# Protoboard_MX3-11-8-ESP12.net
KiCad netlist of a schematic drawn in EAGLE
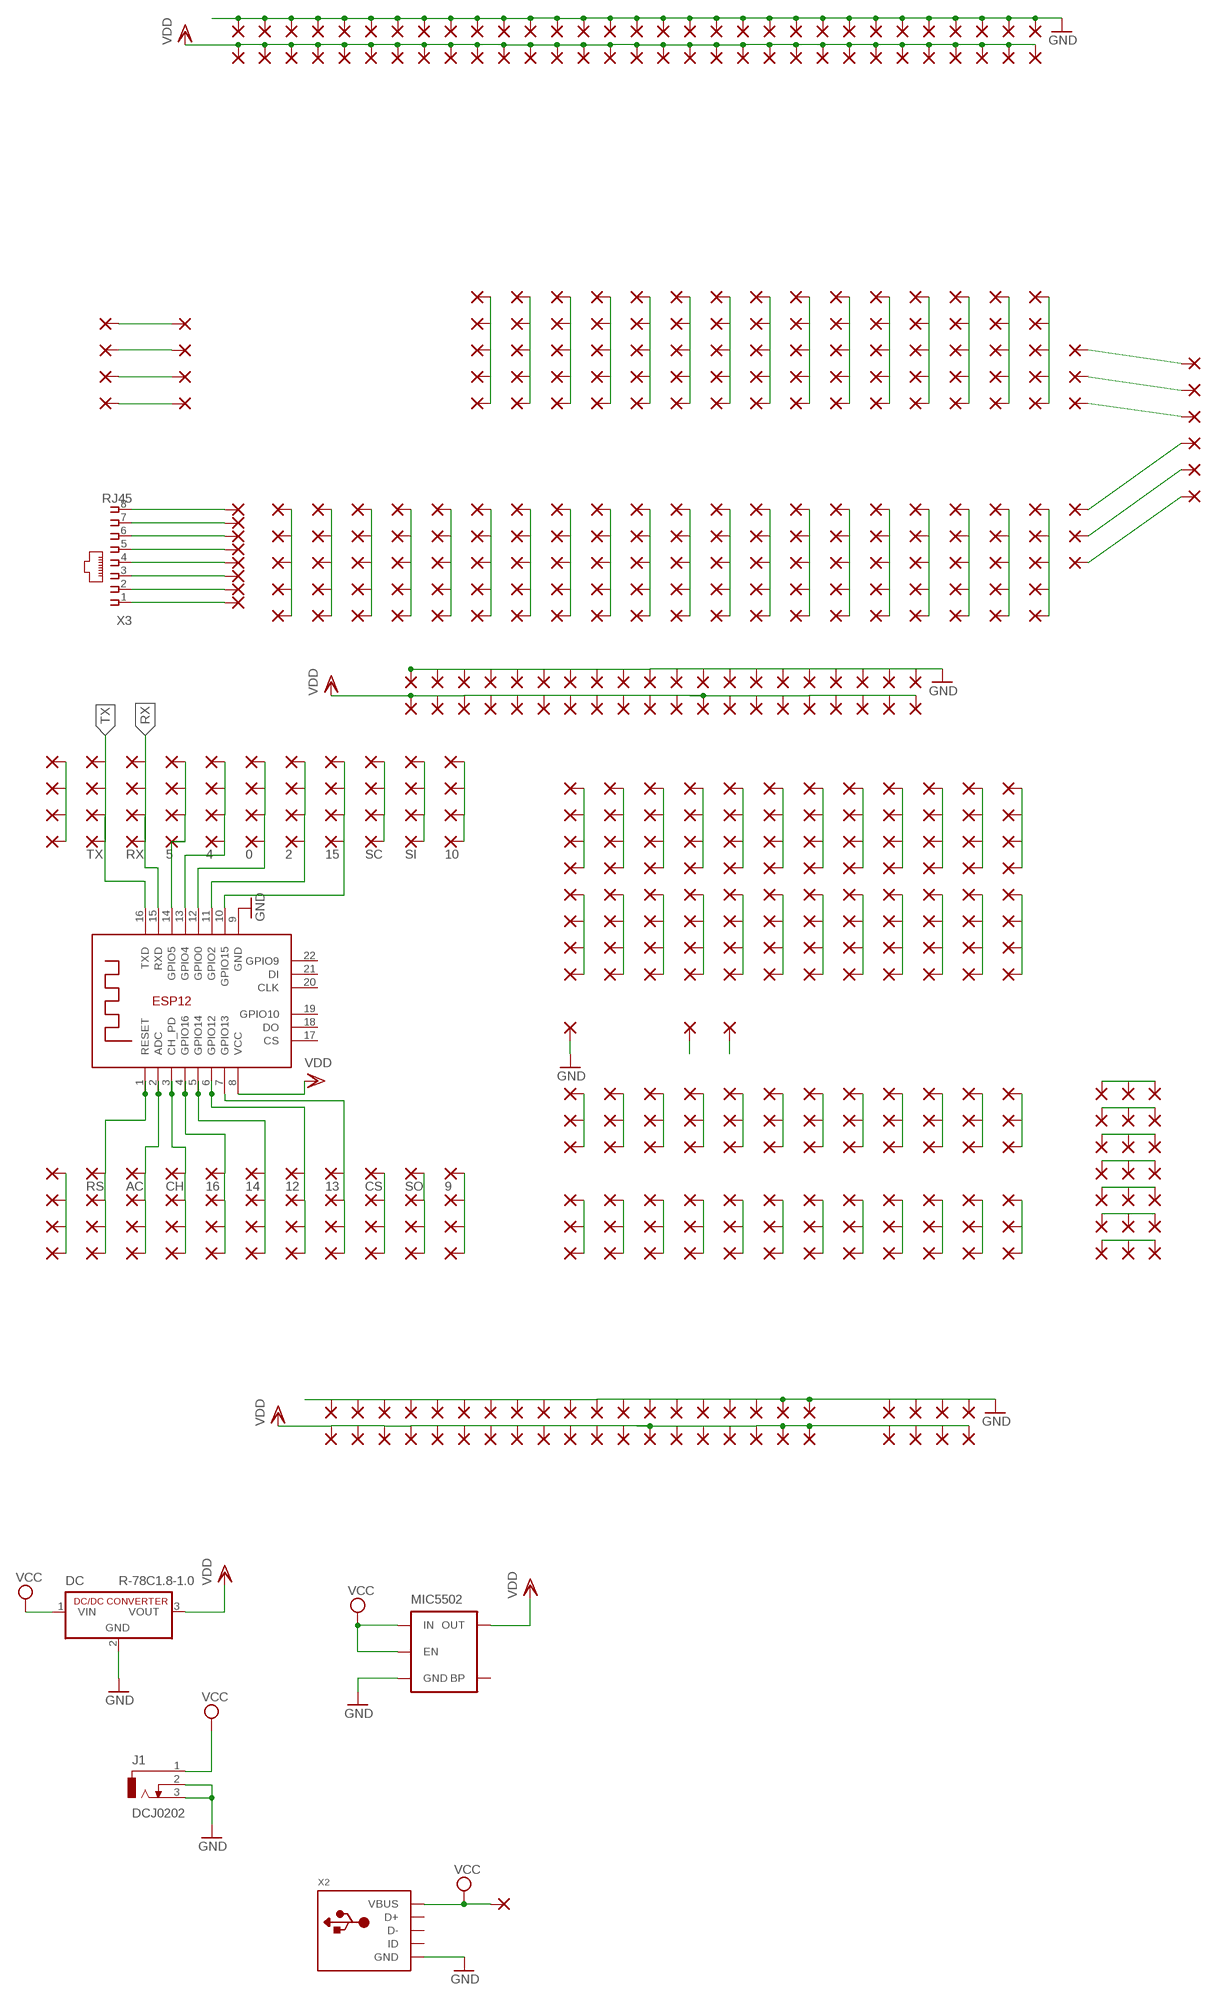
[diagram p0: schematic, sheet 1]

(export (version "E")
  (design (tool "Eeschema 10.0.6"))
  (components
    (comp (ref "1")
      (value "1,6/0,8")
      (footprint "eagle-import:1,6_0,8")
      (libsource (lib "eagle-import") (part "1,6/0,8"))
    )
    (comp (ref "2")
      (value "1,6/0,8")
      (footprint "eagle-import:1,6_0,8")
      (libsource (lib "eagle-import") (part "1,6/0,8"))
    )
    (comp (ref "4")
      (value "1,6/0,8")
      (footprint "eagle-import:1,6_0,8")
      (libsource (lib "eagle-import") (part "1,6/0,8"))
    )
    (comp (ref "5")
      (value "1,6/0,8")
      (footprint "eagle-import:1,6_0,8")
      (libsource (lib "eagle-import") (part "1,6/0,8"))
    )
    (comp (ref "5V")
      (value "1,6/0,8")
      (footprint "eagle-import:1,6_0,8")
      (libsource (lib "eagle-import") (part "1,6/0,8"))
    )
    (comp (ref "6")
      (value "1,6/0,8")
      (footprint "eagle-import:1,6_0,8")
      (libsource (lib "eagle-import") (part "1,6/0,8"))
    )
    (comp (ref "7")
      (value "1,6/0,8")
      (footprint "eagle-import:1,6_0,8")
      (libsource (lib "eagle-import") (part "1,6/0,8"))
    )
    (comp (ref "8")
      (value "1,6/0,8")
      (footprint "eagle-import:1,6_0,8")
      (libsource (lib "eagle-import") (part "1,6/0,8"))
    )
    (comp (ref "DC")
      (value "R-78C1.8-1.0")
      (footprint "eagle-import:SIP3")
      (libsource (lib "eagle-import") (part "R-78C-1.01.8"))
    )
    (comp (ref "J1")
      (value "DCJ0202")
      (footprint "eagle-import:DCJ0202")
      (libsource (lib "eagle-import") (part "DCJ0202"))
    )
    (comp (ref "MIC5502")
      (value "MIC52053.3V")
      (footprint "eagle-import:SOT23-5")
      (libsource (lib "eagle-import") (part "MIC52053.3V"))
    )
    (comp (ref "PAD1")
      (value "1,6/0,8")
      (footprint "eagle-import:1,6_0,8")
      (libsource (lib "eagle-import") (part "1,6/0,8"))
    )
    (comp (ref "PAD2")
      (value "1,6/0,8")
      (footprint "eagle-import:1,6_0,8")
      (libsource (lib "eagle-import") (part "1,6/0,8"))
    )
    (comp (ref "PAD3")
      (value "1,6/0,8")
      (footprint "eagle-import:1,6_0,8")
      (libsource (lib "eagle-import") (part "1,6/0,8"))
    )
    (comp (ref "PAD4")
      (value "1,6/0,8")
      (footprint "eagle-import:1,6_0,8")
      (libsource (lib "eagle-import") (part "1,6/0,8"))
    )
    (comp (ref "PAD5")
      (value "1,6/0,8")
      (footprint "eagle-import:1,6_0,8")
      (libsource (lib "eagle-import") (part "1,6/0,8"))
    )
    (comp (ref "PAD6")
      (value "1,6/0,8")
      (footprint "eagle-import:1,6_0,8")
      (libsource (lib "eagle-import") (part "1,6/0,8"))
    )
    (comp (ref "PAD7")
      (value "1,6/0,8")
      (footprint "eagle-import:1,6_0,8")
      (libsource (lib "eagle-import") (part "1,6/0,8"))
    )
    (comp (ref "PAD8")
      (value "1,6/0,8")
      (footprint "eagle-import:1,6_0,8")
      (libsource (lib "eagle-import") (part "1,6/0,8"))
    )
    (comp (ref "PAD9")
      (value "1,6/0,8")
      (footprint "eagle-import:1,6_0,8")
      (libsource (lib "eagle-import") (part "1,6/0,8"))
    )
    (comp (ref "PAD10")
      (value "1,6/0,8")
      (footprint "eagle-import:1,6_0,8")
      (libsource (lib "eagle-import") (part "1,6/0,8"))
    )
    (comp (ref "PAD11")
      (value "1,6/0,8")
      (footprint "eagle-import:1,6_0,8")
      (libsource (lib "eagle-import") (part "1,6/0,8"))
    )
    (comp (ref "PAD12")
      (value "1,6/0,8")
      (footprint "eagle-import:1,6_0,8")
      (libsource (lib "eagle-import") (part "1,6/0,8"))
    )
    (comp (ref "PAD13")
      (value "1,6/0,8")
      (footprint "eagle-import:1,6_0,8")
      (libsource (lib "eagle-import") (part "1,6/0,8"))
    )
    (comp (ref "PAD14")
      (value "1,6/0,8")
      (footprint "eagle-import:1,6_0,8")
      (libsource (lib "eagle-import") (part "1,6/0,8"))
    )
    (comp (ref "PAD15")
      (value "1,6/0,8")
      (footprint "eagle-import:1,6_0,8")
      (libsource (lib "eagle-import") (part "1,6/0,8"))
    )
    (comp (ref "PAD16")
      (value "1,6/0,8")
      (footprint "eagle-import:1,6_0,8")
      (libsource (lib "eagle-import") (part "1,6/0,8"))
    )
    (comp (ref "PAD17")
      (value "1,6/0,8")
      (footprint "eagle-import:1,6_0,8")
      (libsource (lib "eagle-import") (part "1,6/0,8"))
    )
    (comp (ref "PAD18")
      (value "1,6/0,8")
      (footprint "eagle-import:1,6_0,8")
      (libsource (lib "eagle-import") (part "1,6/0,8"))
    )
    (comp (ref "PAD19")
      (value "1,6/0,8")
      (footprint "eagle-import:1,6_0,8")
      (libsource (lib "eagle-import") (part "1,6/0,8"))
    )
    (comp (ref "PAD20")
      (value "1,6/0,8")
      (footprint "eagle-import:1,6_0,8")
      (libsource (lib "eagle-import") (part "1,6/0,8"))
    )
    (comp (ref "PAD21")
      (value "1,6/0,8")
      (footprint "eagle-import:1,6_0,8")
      (libsource (lib "eagle-import") (part "1,6/0,8"))
    )
    (comp (ref "PAD22")
      (value "1,6/0,8")
      (footprint "eagle-import:1,6_0,8")
      (libsource (lib "eagle-import") (part "1,6/0,8"))
    )
    (comp (ref "PAD23")
      (value "1,6/0,8")
      (footprint "eagle-import:1,6_0,8")
      (libsource (lib "eagle-import") (part "1,6/0,8"))
    )
    (comp (ref "PAD24")
      (value "1,6/0,8")
      (footprint "eagle-import:1,6_0,8")
      (libsource (lib "eagle-import") (part "1,6/0,8"))
    )
    (comp (ref "PAD25")
      (value "1,6/0,8")
      (footprint "eagle-import:1,6_0,8")
      (libsource (lib "eagle-import") (part "1,6/0,8"))
    )
    (comp (ref "PAD26")
      (value "1,6/0,8")
      (footprint "eagle-import:1,6_0,8")
      (libsource (lib "eagle-import") (part "1,6/0,8"))
    )
    (comp (ref "PAD27")
      (value "1,6/0,8")
      (footprint "eagle-import:1,6_0,8")
      (libsource (lib "eagle-import") (part "1,6/0,8"))
    )
    (comp (ref "PAD28")
      (value "1,6/0,8")
      (footprint "eagle-import:1,6_0,8")
      (libsource (lib "eagle-import") (part "1,6/0,8"))
    )
    (comp (ref "PAD29")
      (value "1,6/0,8")
      (footprint "eagle-import:1,6_0,8")
      (libsource (lib "eagle-import") (part "1,6/0,8"))
    )
    (comp (ref "PAD30")
      (value "1,6/0,8")
      (footprint "eagle-import:1,6_0,8")
      (libsource (lib "eagle-import") (part "1,6/0,8"))
    )
    (comp (ref "PAD31")
      (value "1,6/0,8")
      (footprint "eagle-import:1,6_0,8")
      (libsource (lib "eagle-import") (part "1,6/0,8"))
    )
    (comp (ref "PAD32")
      (value "1,6/0,8")
      (footprint "eagle-import:1,6_0,8")
      (libsource (lib "eagle-import") (part "1,6/0,8"))
    )
    (comp (ref "PAD33")
      (value "1,6/0,8")
      (footprint "eagle-import:1,6_0,8")
      (libsource (lib "eagle-import") (part "1,6/0,8"))
    )
    (comp (ref "PAD34")
      (value "1,6/0,8")
      (footprint "eagle-import:1,6_0,8")
      (libsource (lib "eagle-import") (part "1,6/0,8"))
    )
    (comp (ref "PAD35")
      (value "1,6/0,8")
      (footprint "eagle-import:1,6_0,8")
      (libsource (lib "eagle-import") (part "1,6/0,8"))
    )
    (comp (ref "PAD36")
      (value "1,6/0,8")
      (footprint "eagle-import:1,6_0,8")
      (libsource (lib "eagle-import") (part "1,6/0,8"))
    )
    (comp (ref "PAD37")
      (value "1,6/0,8")
      (footprint "eagle-import:1,6_0,8")
      (libsource (lib "eagle-import") (part "1,6/0,8"))
    )
    (comp (ref "PAD38")
      (value "1,6/0,8")
      (footprint "eagle-import:1,6_0,8")
      (libsource (lib "eagle-import") (part "1,6/0,8"))
    )
    (comp (ref "PAD39")
      (value "1,6/0,8")
      (footprint "eagle-import:1,6_0,8")
      (libsource (lib "eagle-import") (part "1,6/0,8"))
    )
    (comp (ref "PAD40")
      (value "1,6/0,8")
      (footprint "eagle-import:1,6_0,8")
      (libsource (lib "eagle-import") (part "1,6/0,8"))
    )
    (comp (ref "PAD41")
      (value "1,6/0,8")
      (footprint "eagle-import:1,6_0,8")
      (libsource (lib "eagle-import") (part "1,6/0,8"))
    )
    (comp (ref "PAD42")
      (value "1,6/0,8")
      (footprint "eagle-import:1,6_0,8")
      (libsource (lib "eagle-import") (part "1,6/0,8"))
    )
    (comp (ref "PAD45")
      (value "1,6/0,8")
      (footprint "eagle-import:1,6_0,8")
      (libsource (lib "eagle-import") (part "1,6/0,8"))
    )
    (comp (ref "PAD46")
      (value "1,6/0,8")
      (footprint "eagle-import:1,6_0,8")
      (libsource (lib "eagle-import") (part "1,6/0,8"))
    )
    (comp (ref "PAD47")
      (value "1,6/0,8")
      (footprint "eagle-import:1,6_0,8")
      (libsource (lib "eagle-import") (part "1,6/0,8"))
    )
    (comp (ref "PAD48")
      (value "1,6/0,8")
      (footprint "eagle-import:1,6_0,8")
      (libsource (lib "eagle-import") (part "1,6/0,8"))
    )
    (comp (ref "PAD52")
      (value "1,6/0,8")
      (footprint "eagle-import:1,6_0,8")
      (libsource (lib "eagle-import") (part "1,6/0,8"))
    )
    (comp (ref "PAD53")
      (value "1,6/0,8")
      (footprint "eagle-import:1,6_0,8")
      (libsource (lib "eagle-import") (part "1,6/0,8"))
    )
    (comp (ref "PAD54")
      (value "1,6/0,8")
      (footprint "eagle-import:1,6_0,8")
      (libsource (lib "eagle-import") (part "1,6/0,8"))
    )
    (comp (ref "PAD55")
      (value "1,6/0,8")
      (footprint "eagle-import:1,6_0,8")
      (libsource (lib "eagle-import") (part "1,6/0,8"))
    )
    (comp (ref "PAD59")
      (value "1,6/0,8")
      (footprint "eagle-import:1,6_0,8")
      (libsource (lib "eagle-import") (part "1,6/0,8"))
    )
    (comp (ref "PAD60")
      (value "1,6/0,8")
      (footprint "eagle-import:1,6_0,8")
      (libsource (lib "eagle-import") (part "1,6/0,8"))
    )
    (comp (ref "PAD61")
      (value "1,6/0,8")
      (footprint "eagle-import:1,6_0,8")
      (libsource (lib "eagle-import") (part "1,6/0,8"))
    )
    (comp (ref "PAD62")
      (value "1,6/0,8")
      (footprint "eagle-import:1,6_0,8")
      (libsource (lib "eagle-import") (part "1,6/0,8"))
    )
    (comp (ref "PAD63")
      (value "1,6/0,8")
      (footprint "eagle-import:1,6_0,8")
      (libsource (lib "eagle-import") (part "1,6/0,8"))
    )
    (comp (ref "PAD64")
      (value "1,6/0,8")
      (footprint "eagle-import:1,6_0,8")
      (libsource (lib "eagle-import") (part "1,6/0,8"))
    )
    (comp (ref "PAD65")
      (value "1,6/0,8")
      (footprint "eagle-import:1,6_0,8")
      (libsource (lib "eagle-import") (part "1,6/0,8"))
    )
    (comp (ref "PAD66")
      (value "1,6/0,8")
      (footprint "eagle-import:1,6_0,8")
      (libsource (lib "eagle-import") (part "1,6/0,8"))
    )
    (comp (ref "PAD67")
      (value "1,6/0,8")
      (footprint "eagle-import:1,6_0,8")
      (libsource (lib "eagle-import") (part "1,6/0,8"))
    )
    (comp (ref "PAD68")
      (value "1,6/0,8")
      (footprint "eagle-import:1,6_0,8")
      (libsource (lib "eagle-import") (part "1,6/0,8"))
    )
    (comp (ref "PAD69")
      (value "1,6/0,8")
      (footprint "eagle-import:1,6_0,8")
      (libsource (lib "eagle-import") (part "1,6/0,8"))
    )
    (comp (ref "PAD70")
      (value "1,6/0,8")
      (footprint "eagle-import:1,6_0,8")
      (libsource (lib "eagle-import") (part "1,6/0,8"))
    )
    (comp (ref "PAD71")
      (value "1,6/0,8")
      (footprint "eagle-import:1,6_0,8")
      (libsource (lib "eagle-import") (part "1,6/0,8"))
    )
    (comp (ref "PAD72")
      (value "1,6/0,8")
      (footprint "eagle-import:1,6_0,8")
      (libsource (lib "eagle-import") (part "1,6/0,8"))
    )
    (comp (ref "PAD73")
      (value "1,6/0,8")
      (footprint "eagle-import:1,6_0,8")
      (libsource (lib "eagle-import") (part "1,6/0,8"))
    )
    (comp (ref "PAD74")
      (value "1,6/0,8")
      (footprint "eagle-import:1,6_0,8")
      (libsource (lib "eagle-import") (part "1,6/0,8"))
    )
    (comp (ref "PAD75")
      (value "1,6/0,8")
      (footprint "eagle-import:1,6_0,8")
      (libsource (lib "eagle-import") (part "1,6/0,8"))
    )
    (comp (ref "PAD76")
      (value "1,6/0,8")
      (footprint "eagle-import:1,6_0,8")
      (libsource (lib "eagle-import") (part "1,6/0,8"))
    )
    (comp (ref "PAD77")
      (value "1,6/0,8")
      (footprint "eagle-import:1,6_0,8")
      (libsource (lib "eagle-import") (part "1,6/0,8"))
    )
    (comp (ref "PAD78")
      (value "1,6/0,8")
      (footprint "eagle-import:1,6_0,8")
      (libsource (lib "eagle-import") (part "1,6/0,8"))
    )
    (comp (ref "PAD79")
      (value "1,6/0,8")
      (footprint "eagle-import:1,6_0,8")
      (libsource (lib "eagle-import") (part "1,6/0,8"))
    )
    (comp (ref "PAD80")
      (value "1,6/0,8")
      (footprint "eagle-import:1,6_0,8")
      (libsource (lib "eagle-import") (part "1,6/0,8"))
    )
    (comp (ref "PAD81")
      (value "1,6/0,8")
      (footprint "eagle-import:1,6_0,8")
      (libsource (lib "eagle-import") (part "1,6/0,8"))
    )
    (comp (ref "PAD82")
      (value "1,6/0,8")
      (footprint "eagle-import:1,6_0,8")
      (libsource (lib "eagle-import") (part "1,6/0,8"))
    )
    (comp (ref "PAD83")
      (value "1,6/0,8")
      (footprint "eagle-import:1,6_0,8")
      (libsource (lib "eagle-import") (part "1,6/0,8"))
    )
    (comp (ref "PAD84")
      (value "1,6/0,8")
      (footprint "eagle-import:1,6_0,8")
      (libsource (lib "eagle-import") (part "1,6/0,8"))
    )
    (comp (ref "PAD85")
      (value "1,6/0,8")
      (footprint "eagle-import:1,6_0,8")
      (libsource (lib "eagle-import") (part "1,6/0,8"))
    )
    (comp (ref "PAD86")
      (value "1,6/0,8")
      (footprint "eagle-import:1,6_0,8")
      (libsource (lib "eagle-import") (part "1,6/0,8"))
    )
    (comp (ref "PAD88")
      (value "1,6/0,8")
      (footprint "eagle-import:1,6_0,8")
      (libsource (lib "eagle-import") (part "1,6/0,8"))
    )
    (comp (ref "PAD89")
      (value "1,6/0,8")
      (footprint "eagle-import:1,6_0,8")
      (libsource (lib "eagle-import") (part "1,6/0,8"))
    )
    (comp (ref "PAD90")
      (value "1,6/0,8")
      (footprint "eagle-import:1,6_0,8")
      (libsource (lib "eagle-import") (part "1,6/0,8"))
    )
    (comp (ref "PAD91")
      (value "1,6/0,8")
      (footprint "eagle-import:1,6_0,8")
      (libsource (lib "eagle-import") (part "1,6/0,8"))
    )
    (comp (ref "PAD92")
      (value "1,6/0,8")
      (footprint "eagle-import:1,6_0,8")
      (libsource (lib "eagle-import") (part "1,6/0,8"))
    )
    (comp (ref "PAD93")
      (value "1,6/0,8")
      (footprint "eagle-import:1,6_0,8")
      (libsource (lib "eagle-import") (part "1,6/0,8"))
    )
    (comp (ref "PAD94")
      (value "1,6/0,8")
      (footprint "eagle-import:1,6_0,8")
      (libsource (lib "eagle-import") (part "1,6/0,8"))
    )
    (comp (ref "PAD97")
      (value "1,6/0,8")
      (footprint "eagle-import:1,6_0,8")
      (libsource (lib "eagle-import") (part "1,6/0,8"))
    )
    (comp (ref "PAD98")
      (value "1,6/0,8")
      (footprint "eagle-import:1,6_0,8")
      (libsource (lib "eagle-import") (part "1,6/0,8"))
    )
    (comp (ref "PAD99")
      (value "1,6/0,8")
      (footprint "eagle-import:1,6_0,8")
      (libsource (lib "eagle-import") (part "1,6/0,8"))
    )
    (comp (ref "PAD100")
      (value "1,6/0,8")
      (footprint "eagle-import:1,6_0,8")
      (libsource (lib "eagle-import") (part "1,6/0,8"))
    )
    (comp (ref "PAD101")
      (value "1,6/0,8")
      (footprint "eagle-import:1,6_0,8")
      (libsource (lib "eagle-import") (part "1,6/0,8"))
    )
    (comp (ref "PAD102")
      (value "1,6/0,8")
      (footprint "eagle-import:1,6_0,8")
      (libsource (lib "eagle-import") (part "1,6/0,8"))
    )
    (comp (ref "PAD103")
      (value "1,6/0,8")
      (footprint "eagle-import:1,6_0,8")
      (libsource (lib "eagle-import") (part "1,6/0,8"))
    )
    (comp (ref "PAD106")
      (value "1,6/0,8")
      (footprint "eagle-import:1,6_0,8")
      (libsource (lib "eagle-import") (part "1,6/0,8"))
    )
    (comp (ref "PAD107")
      (value "1,6/0,8")
      (footprint "eagle-import:1,6_0,8")
      (libsource (lib "eagle-import") (part "1,6/0,8"))
    )
    (comp (ref "PAD108")
      (value "1,6/0,8")
      (footprint "eagle-import:1,6_0,8")
      (libsource (lib "eagle-import") (part "1,6/0,8"))
    )
    (comp (ref "PAD109")
      (value "1,6/0,8")
      (footprint "eagle-import:1,6_0,8")
      (libsource (lib "eagle-import") (part "1,6/0,8"))
    )
    (comp (ref "PAD110")
      (value "1,6/0,8")
      (footprint "eagle-import:1,6_0,8")
      (libsource (lib "eagle-import") (part "1,6/0,8"))
    )
    (comp (ref "PAD111")
      (value "1,6/0,8")
      (footprint "eagle-import:1,6_0,8")
      (libsource (lib "eagle-import") (part "1,6/0,8"))
    )
    (comp (ref "PAD112")
      (value "1,6/0,8")
      (footprint "eagle-import:1,6_0,8")
      (libsource (lib "eagle-import") (part "1,6/0,8"))
    )
    (comp (ref "PAD115")
      (value "1,6/0,8")
      (footprint "eagle-import:1,6_0,8")
      (libsource (lib "eagle-import") (part "1,6/0,8"))
    )
    (comp (ref "PAD116")
      (value "1,6/0,8")
      (footprint "eagle-import:1,6_0,8")
      (libsource (lib "eagle-import") (part "1,6/0,8"))
    )
    (comp (ref "PAD117")
      (value "1,6/0,8")
      (footprint "eagle-import:1,6_0,8")
      (libsource (lib "eagle-import") (part "1,6/0,8"))
    )
    (comp (ref "PAD118")
      (value "1,6/0,8")
      (footprint "eagle-import:1,6_0,8")
      (libsource (lib "eagle-import") (part "1,6/0,8"))
    )
    (comp (ref "PAD119")
      (value "1,6/0,8")
      (footprint "eagle-import:1,6_0,8")
      (libsource (lib "eagle-import") (part "1,6/0,8"))
    )
    (comp (ref "PAD120")
      (value "1,6/0,8")
      (footprint "eagle-import:1,6_0,8")
      (libsource (lib "eagle-import") (part "1,6/0,8"))
    )
    (comp (ref "PAD121")
      (value "1,6/0,8")
      (footprint "eagle-import:1,6_0,8")
      (libsource (lib "eagle-import") (part "1,6/0,8"))
    )
    (comp (ref "PAD122")
      (value "1,6/0,8")
      (footprint "eagle-import:1,6_0,8")
      (libsource (lib "eagle-import") (part "1,6/0,8"))
    )
    (comp (ref "PAD123")
      (value "1,6/0,8")
      (footprint "eagle-import:1,6_0,8")
      (libsource (lib "eagle-import") (part "1,6/0,8"))
    )
    (comp (ref "PAD124")
      (value "1,6/0,8")
      (footprint "eagle-import:1,6_0,8")
      (libsource (lib "eagle-import") (part "1,6/0,8"))
    )
    (comp (ref "PAD125")
      (value "1,6/0,8")
      (footprint "eagle-import:1,6_0,8")
      (libsource (lib "eagle-import") (part "1,6/0,8"))
    )
    (comp (ref "PAD126")
      (value "1,6/0,8")
      (footprint "eagle-import:1,6_0,8")
      (libsource (lib "eagle-import") (part "1,6/0,8"))
    )
    (comp (ref "PAD128")
      (value "1,6/0,8")
      (footprint "eagle-import:1,6_0,8")
      (libsource (lib "eagle-import") (part "1,6/0,8"))
    )
    (comp (ref "PAD129")
      (value "1,6/0,8")
      (footprint "eagle-import:1,6_0,8")
      (libsource (lib "eagle-import") (part "1,6/0,8"))
    )
    (comp (ref "PAD130")
      (value "1,6/0,8")
      (footprint "eagle-import:1,6_0,8")
      (libsource (lib "eagle-import") (part "1,6/0,8"))
    )
    (comp (ref "PAD131")
      (value "1,6/0,8")
      (footprint "eagle-import:1,6_0,8")
      (libsource (lib "eagle-import") (part "1,6/0,8"))
    )
    (comp (ref "PAD132")
      (value "1,6/0,8")
      (footprint "eagle-import:1,6_0,8")
      (libsource (lib "eagle-import") (part "1,6/0,8"))
    )
    (comp (ref "PAD133")
      (value "1,6/0,8")
      (footprint "eagle-import:1,6_0,8")
      (libsource (lib "eagle-import") (part "1,6/0,8"))
    )
    (comp (ref "PAD134")
      (value "1,6/0,8")
      (footprint "eagle-import:1,6_0,8")
      (libsource (lib "eagle-import") (part "1,6/0,8"))
    )
    (comp (ref "PAD135")
      (value "1,6/0,8")
      (footprint "eagle-import:1,6_0,8")
      (libsource (lib "eagle-import") (part "1,6/0,8"))
    )
    (comp (ref "PAD137")
      (value "1,6/0,8")
      (footprint "eagle-import:1,6_0,8")
      (libsource (lib "eagle-import") (part "1,6/0,8"))
    )
    (comp (ref "PAD138")
      (value "1,6/0,8")
      (footprint "eagle-import:1,6_0,8")
      (libsource (lib "eagle-import") (part "1,6/0,8"))
    )
    (comp (ref "PAD139")
      (value "1,6/0,8")
      (footprint "eagle-import:1,6_0,8")
      (libsource (lib "eagle-import") (part "1,6/0,8"))
    )
    (comp (ref "PAD140")
      (value "1,6/0,8")
      (footprint "eagle-import:1,6_0,8")
      (libsource (lib "eagle-import") (part "1,6/0,8"))
    )
    (comp (ref "PAD141")
      (value "1,6/0,8")
      (footprint "eagle-import:1,6_0,8")
      (libsource (lib "eagle-import") (part "1,6/0,8"))
    )
    (comp (ref "PAD142")
      (value "1,6/0,8")
      (footprint "eagle-import:1,6_0,8")
      (libsource (lib "eagle-import") (part "1,6/0,8"))
    )
    (comp (ref "PAD143")
      (value "1,6/0,8")
      (footprint "eagle-import:1,6_0,8")
      (libsource (lib "eagle-import") (part "1,6/0,8"))
    )
    (comp (ref "PAD144")
      (value "1,6/0,8")
      (footprint "eagle-import:1,6_0,8")
      (libsource (lib "eagle-import") (part "1,6/0,8"))
    )
    (comp (ref "PAD146")
      (value "1,6/0,8")
      (footprint "eagle-import:1,6_0,8")
      (libsource (lib "eagle-import") (part "1,6/0,8"))
    )
    (comp (ref "PAD147")
      (value "1,6/0,8")
      (footprint "eagle-import:1,6_0,8")
      (libsource (lib "eagle-import") (part "1,6/0,8"))
    )
    (comp (ref "PAD148")
      (value "1,6/0,8")
      (footprint "eagle-import:1,6_0,8")
      (libsource (lib "eagle-import") (part "1,6/0,8"))
    )
    (comp (ref "PAD149")
      (value "1,6/0,8")
      (footprint "eagle-import:1,6_0,8")
      (libsource (lib "eagle-import") (part "1,6/0,8"))
    )
    (comp (ref "PAD150")
      (value "1,6/0,8")
      (footprint "eagle-import:1,6_0,8")
      (libsource (lib "eagle-import") (part "1,6/0,8"))
    )
    (comp (ref "PAD151")
      (value "1,6/0,8")
      (footprint "eagle-import:1,6_0,8")
      (libsource (lib "eagle-import") (part "1,6/0,8"))
    )
    (comp (ref "PAD152")
      (value "1,6/0,8")
      (footprint "eagle-import:1,6_0,8")
      (libsource (lib "eagle-import") (part "1,6/0,8"))
    )
    (comp (ref "PAD153")
      (value "1,6/0,8")
      (footprint "eagle-import:1,6_0,8")
      (libsource (lib "eagle-import") (part "1,6/0,8"))
    )
    (comp (ref "PAD155")
      (value "1,6/0,8")
      (footprint "eagle-import:1,6_0,8")
      (libsource (lib "eagle-import") (part "1,6/0,8"))
    )
    (comp (ref "PAD156")
      (value "1,6/0,8")
      (footprint "eagle-import:1,6_0,8")
      (libsource (lib "eagle-import") (part "1,6/0,8"))
    )
    (comp (ref "PAD157")
      (value "1,6/0,8")
      (footprint "eagle-import:1,6_0,8")
      (libsource (lib "eagle-import") (part "1,6/0,8"))
    )
    (comp (ref "PAD158")
      (value "1,6/0,8")
      (footprint "eagle-import:1,6_0,8")
      (libsource (lib "eagle-import") (part "1,6/0,8"))
    )
    (comp (ref "PAD159")
      (value "1,6/0,8")
      (footprint "eagle-import:1,6_0,8")
      (libsource (lib "eagle-import") (part "1,6/0,8"))
    )
    (comp (ref "PAD160")
      (value "1,6/0,8")
      (footprint "eagle-import:1,6_0,8")
      (libsource (lib "eagle-import") (part "1,6/0,8"))
    )
    (comp (ref "PAD161")
      (value "1,6/0,8")
      (footprint "eagle-import:1,6_0,8")
      (libsource (lib "eagle-import") (part "1,6/0,8"))
    )
    (comp (ref "PAD162")
      (value "1,6/0,8")
      (footprint "eagle-import:1,6_0,8")
      (libsource (lib "eagle-import") (part "1,6/0,8"))
    )
    (comp (ref "PAD164")
      (value "1,6/0,8")
      (footprint "eagle-import:1,6_0,8")
      (libsource (lib "eagle-import") (part "1,6/0,8"))
    )
    (comp (ref "PAD165")
      (value "1,6/0,8")
      (footprint "eagle-import:1,6_0,8")
      (libsource (lib "eagle-import") (part "1,6/0,8"))
    )
    (comp (ref "PAD166")
      (value "1,6/0,8")
      (footprint "eagle-import:1,6_0,8")
      (libsource (lib "eagle-import") (part "1,6/0,8"))
    )
    (comp (ref "PAD167")
      (value "1,6/0,8")
      (footprint "eagle-import:1,6_0,8")
      (libsource (lib "eagle-import") (part "1,6/0,8"))
    )
    (comp (ref "PAD168")
      (value "1,6/0,8")
      (footprint "eagle-import:1,6_0,8")
      (libsource (lib "eagle-import") (part "1,6/0,8"))
    )
    (comp (ref "PAD169")
      (value "1,6/0,8")
      (footprint "eagle-import:1,6_0,8")
      (libsource (lib "eagle-import") (part "1,6/0,8"))
    )
    (comp (ref "PAD170")
      (value "1,6/0,8")
      (footprint "eagle-import:1,6_0,8")
      (libsource (lib "eagle-import") (part "1,6/0,8"))
    )
    (comp (ref "PAD171")
      (value "1,6/0,8")
      (footprint "eagle-import:1,6_0,8")
      (libsource (lib "eagle-import") (part "1,6/0,8"))
    )
    (comp (ref "PAD173")
      (value "1,6/0,8")
      (footprint "eagle-import:1,6_0,8")
      (libsource (lib "eagle-import") (part "1,6/0,8"))
    )
    (comp (ref "PAD174")
      (value "1,6/0,8")
      (footprint "eagle-import:1,6_0,8")
      (libsource (lib "eagle-import") (part "1,6/0,8"))
    )
    (comp (ref "PAD175")
      (value "1,6/0,8")
      (footprint "eagle-import:1,6_0,8")
      (libsource (lib "eagle-import") (part "1,6/0,8"))
    )
    (comp (ref "PAD176")
      (value "1,6/0,8")
      (footprint "eagle-import:1,6_0,8")
      (libsource (lib "eagle-import") (part "1,6/0,8"))
    )
    (comp (ref "PAD177")
      (value "1,6/0,8")
      (footprint "eagle-import:1,6_0,8")
      (libsource (lib "eagle-import") (part "1,6/0,8"))
    )
    (comp (ref "PAD178")
      (value "1,6/0,8")
      (footprint "eagle-import:1,6_0,8")
      (libsource (lib "eagle-import") (part "1,6/0,8"))
    )
    (comp (ref "PAD179")
      (value "1,6/0,8")
      (footprint "eagle-import:1,6_0,8")
      (libsource (lib "eagle-import") (part "1,6/0,8"))
    )
    (comp (ref "PAD180")
      (value "1,6/0,8")
      (footprint "eagle-import:1,6_0,8")
      (libsource (lib "eagle-import") (part "1,6/0,8"))
    )
    (comp (ref "PAD182")
      (value "1,6/0,8")
      (footprint "eagle-import:1,6_0,8")
      (libsource (lib "eagle-import") (part "1,6/0,8"))
    )
    (comp (ref "PAD183")
      (value "1,6/0,8")
      (footprint "eagle-import:1,6_0,8")
      (libsource (lib "eagle-import") (part "1,6/0,8"))
    )
    (comp (ref "PAD184")
      (value "1,6/0,8")
      (footprint "eagle-import:1,6_0,8")
      (libsource (lib "eagle-import") (part "1,6/0,8"))
    )
    (comp (ref "PAD185")
      (value "1,6/0,8")
      (footprint "eagle-import:1,6_0,8")
      (libsource (lib "eagle-import") (part "1,6/0,8"))
    )
    (comp (ref "PAD186")
      (value "1,6/0,8")
      (footprint "eagle-import:1,6_0,8")
      (libsource (lib "eagle-import") (part "1,6/0,8"))
    )
    (comp (ref "PAD194")
      (value "1,6/0,8")
      (footprint "eagle-import:1,6_0,8")
      (libsource (lib "eagle-import") (part "1,6/0,8"))
    )
    (comp (ref "PAD195")
      (value "1,6/0,8")
      (footprint "eagle-import:1,6_0,8")
      (libsource (lib "eagle-import") (part "1,6/0,8"))
    )
    (comp (ref "PAD196")
      (value "1,6/0,8")
      (footprint "eagle-import:1,6_0,8")
      (libsource (lib "eagle-import") (part "1,6/0,8"))
    )
    (comp (ref "PAD197")
      (value "1,6/0,8")
      (footprint "eagle-import:1,6_0,8")
      (libsource (lib "eagle-import") (part "1,6/0,8"))
    )
    (comp (ref "PAD198")
      (value "1,6/0,8")
      (footprint "eagle-import:1,6_0,8")
      (libsource (lib "eagle-import") (part "1,6/0,8"))
    )
    (comp (ref "PAD199")
      (value "1,6/0,8")
      (footprint "eagle-import:1,6_0,8")
      (libsource (lib "eagle-import") (part "1,6/0,8"))
    )
    (comp (ref "PAD200")
      (value "1,6/0,8")
      (footprint "eagle-import:1,6_0,8")
      (libsource (lib "eagle-import") (part "1,6/0,8"))
    )
    (comp (ref "PAD201")
      (value "1,6/0,8")
      (footprint "eagle-import:1,6_0,8")
      (libsource (lib "eagle-import") (part "1,6/0,8"))
    )
    (comp (ref "PAD202")
      (value "1,6/0,8")
      (footprint "eagle-import:1,6_0,8")
      (libsource (lib "eagle-import") (part "1,6/0,8"))
    )
    (comp (ref "PAD203")
      (value "1,6/0,8")
      (footprint "eagle-import:1,6_0,8")
      (libsource (lib "eagle-import") (part "1,6/0,8"))
    )
    (comp (ref "PAD204")
      (value "1,6/0,8")
      (footprint "eagle-import:1,6_0,8")
      (libsource (lib "eagle-import") (part "1,6/0,8"))
    )
    (comp (ref "PAD205")
      (value "1,6/0,8")
      (footprint "eagle-import:1,6_0,8")
      (libsource (lib "eagle-import") (part "1,6/0,8"))
    )
    (comp (ref "PAD206")
      (value "1,6/0,8")
      (footprint "eagle-import:1,6_0,8")
      (libsource (lib "eagle-import") (part "1,6/0,8"))
    )
    (comp (ref "PAD207")
      (value "1,6/0,8")
      (footprint "eagle-import:1,6_0,8")
      (libsource (lib "eagle-import") (part "1,6/0,8"))
    )
    (comp (ref "PAD208")
      (value "1,6/0,8")
      (footprint "eagle-import:1,6_0,8")
      (libsource (lib "eagle-import") (part "1,6/0,8"))
    )
    (comp (ref "PAD209")
      (value "1,6/0,8")
      (footprint "eagle-import:1,6_0,8")
      (libsource (lib "eagle-import") (part "1,6/0,8"))
    )
    (comp (ref "PAD210")
      (value "1,6/0,8")
      (footprint "eagle-import:1,6_0,8")
      (libsource (lib "eagle-import") (part "1,6/0,8"))
    )
    (comp (ref "PAD211")
      (value "1,6/0,8")
      (footprint "eagle-import:1,6_0,8")
      (libsource (lib "eagle-import") (part "1,6/0,8"))
    )
    (comp (ref "PAD212")
      (value "1,6/0,8")
      (footprint "eagle-import:1,6_0,8")
      (libsource (lib "eagle-import") (part "1,6/0,8"))
    )
    (comp (ref "PAD213")
      (value "1,6/0,8")
      (footprint "eagle-import:1,6_0,8")
      (libsource (lib "eagle-import") (part "1,6/0,8"))
    )
    (comp (ref "PAD214")
      (value "1,6/0,8")
      (footprint "eagle-import:1,6_0,8")
      (libsource (lib "eagle-import") (part "1,6/0,8"))
    )
    (comp (ref "PAD215")
      (value "1,6/0,8")
      (footprint "eagle-import:1,6_0,8")
      (libsource (lib "eagle-import") (part "1,6/0,8"))
    )
    (comp (ref "PAD216")
      (value "1,6/0,8")
      (footprint "eagle-import:1,6_0,8")
      (libsource (lib "eagle-import") (part "1,6/0,8"))
    )
    (comp (ref "PAD217")
      (value "1,6/0,8")
      (footprint "eagle-import:1,6_0,8")
      (libsource (lib "eagle-import") (part "1,6/0,8"))
    )
    (comp (ref "PAD218")
      (value "1,6/0,8")
      (footprint "eagle-import:1,6_0,8")
      (libsource (lib "eagle-import") (part "1,6/0,8"))
    )
    (comp (ref "PAD219")
      (value "1,6/0,8")
      (footprint "eagle-import:1,6_0,8")
      (libsource (lib "eagle-import") (part "1,6/0,8"))
    )
    (comp (ref "PAD220")
      (value "1,6/0,8")
      (footprint "eagle-import:1,6_0,8")
      (libsource (lib "eagle-import") (part "1,6/0,8"))
    )
    (comp (ref "PAD221")
      (value "1,6/0,8")
      (footprint "eagle-import:1,6_0,8")
      (libsource (lib "eagle-import") (part "1,6/0,8"))
    )
    (comp (ref "PAD222")
      (value "1,6/0,8")
      (footprint "eagle-import:1,6_0,8")
      (libsource (lib "eagle-import") (part "1,6/0,8"))
    )
    (comp (ref "PAD223")
      (value "1,6/0,8")
      (footprint "eagle-import:1,6_0,8")
      (libsource (lib "eagle-import") (part "1,6/0,8"))
    )
    (comp (ref "PAD224")
      (value "1,6/0,8")
      (footprint "eagle-import:1,6_0,8")
      (libsource (lib "eagle-import") (part "1,6/0,8"))
    )
    (comp (ref "PAD225")
      (value "1,6/0,8")
      (footprint "eagle-import:1,6_0,8")
      (libsource (lib "eagle-import") (part "1,6/0,8"))
    )
    (comp (ref "PAD226")
      (value "1,6/0,8")
      (footprint "eagle-import:1,6_0,8")
      (libsource (lib "eagle-import") (part "1,6/0,8"))
    )
    (comp (ref "PAD227")
      (value "1,6/0,8")
      (footprint "eagle-import:1,6_0,8")
      (libsource (lib "eagle-import") (part "1,6/0,8"))
    )
    (comp (ref "PAD228")
      (value "1,6/0,8")
      (footprint "eagle-import:1,6_0,8")
      (libsource (lib "eagle-import") (part "1,6/0,8"))
    )
    (comp (ref "PAD229")
      (value "1,6/0,8")
      (footprint "eagle-import:1,6_0,8")
      (libsource (lib "eagle-import") (part "1,6/0,8"))
    )
    (comp (ref "PAD230")
      (value "1,6/0,8")
      (footprint "eagle-import:1,6_0,8")
      (libsource (lib "eagle-import") (part "1,6/0,8"))
    )
    (comp (ref "PAD231")
      (value "1,6/0,8")
      (footprint "eagle-import:1,6_0,8")
      (libsource (lib "eagle-import") (part "1,6/0,8"))
    )
    (comp (ref "PAD232")
      (value "1,6/0,8")
      (footprint "eagle-import:1,6_0,8")
      (libsource (lib "eagle-import") (part "1,6/0,8"))
    )
    (comp (ref "PAD233")
      (value "1,6/0,8")
      (footprint "eagle-import:1,6_0,8")
      (libsource (lib "eagle-import") (part "1,6/0,8"))
    )
    (comp (ref "PAD234")
      (value "1,6/0,8")
      (footprint "eagle-import:1,6_0,8")
      (libsource (lib "eagle-import") (part "1,6/0,8"))
    )
    (comp (ref "PAD235")
      (value "1,6/0,8")
      (footprint "eagle-import:1,6_0,8")
      (libsource (lib "eagle-import") (part "1,6/0,8"))
    )
    (comp (ref "PAD236")
      (value "1,6/0,8")
      (footprint "eagle-import:1,6_0,8")
      (libsource (lib "eagle-import") (part "1,6/0,8"))
    )
    (comp (ref "PAD237")
      (value "1,6/0,8")
      (footprint "eagle-import:1,6_0,8")
      (libsource (lib "eagle-import") (part "1,6/0,8"))
    )
    (comp (ref "PAD238")
      (value "1,6/0,8")
      (footprint "eagle-import:1,6_0,8")
      (libsource (lib "eagle-import") (part "1,6/0,8"))
    )
    (comp (ref "PAD239")
      (value "1,6/0,8")
      (footprint "eagle-import:1,6_0,8")
      (libsource (lib "eagle-import") (part "1,6/0,8"))
    )
    (comp (ref "PAD240")
      (value "1,6/0,8")
      (footprint "eagle-import:1,6_0,8")
      (libsource (lib "eagle-import") (part "1,6/0,8"))
    )
    (comp (ref "PAD241")
      (value "3,17/1,3")
      (footprint "eagle-import:3,17_1,3")
      (libsource (lib "eagle-import") (part "3,17/1,3"))
    )
    (comp (ref "PAD242")
      (value "3,17/1,3")
      (footprint "eagle-import:3,17_1,3")
      (libsource (lib "eagle-import") (part "3,17/1,3"))
    )
    (comp (ref "PAD243")
      (value "3,17/1,3")
      (footprint "eagle-import:3,17_1,3")
      (libsource (lib "eagle-import") (part "3,17/1,3"))
    )
    (comp (ref "PAD244")
      (value "3,17/1,3")
      (footprint "eagle-import:3,17_1,3")
      (libsource (lib "eagle-import") (part "3,17/1,3"))
    )
    (comp (ref "PAD249")
      (value "1,6/0,8")
      (footprint "eagle-import:1,6_0,8")
      (libsource (lib "eagle-import") (part "1,6/0,8"))
    )
    (comp (ref "PAD250")
      (value "1,6/0,8")
      (footprint "eagle-import:1,6_0,8")
      (libsource (lib "eagle-import") (part "1,6/0,8"))
    )
    (comp (ref "PAD251")
      (value "1,6/0,8")
      (footprint "eagle-import:1,6_0,8")
      (libsource (lib "eagle-import") (part "1,6/0,8"))
    )
    (comp (ref "PAD252")
      (value "1,6/0,8")
      (footprint "eagle-import:1,6_0,8")
      (libsource (lib "eagle-import") (part "1,6/0,8"))
    )
    (comp (ref "PAD253")
      (value "1,6/0,8")
      (footprint "eagle-import:1,6_0,8")
      (libsource (lib "eagle-import") (part "1,6/0,8"))
    )
    (comp (ref "PAD254")
      (value "1,6/0,8")
      (footprint "eagle-import:1,6_0,8")
      (libsource (lib "eagle-import") (part "1,6/0,8"))
    )
    (comp (ref "PAD255")
      (value "1,6/0,8")
      (footprint "eagle-import:1,6_0,8")
      (libsource (lib "eagle-import") (part "1,6/0,8"))
    )
    (comp (ref "PAD256")
      (value "1,6/0,8")
      (footprint "eagle-import:1,6_0,8")
      (libsource (lib "eagle-import") (part "1,6/0,8"))
    )
    (comp (ref "PAD257")
      (value "1,6/0,8")
      (footprint "eagle-import:1,6_0,8")
      (libsource (lib "eagle-import") (part "1,6/0,8"))
    )
    (comp (ref "PAD258")
      (value "1,6/0,8")
      (footprint "eagle-import:1,6_0,8")
      (libsource (lib "eagle-import") (part "1,6/0,8"))
    )
    (comp (ref "PAD259")
      (value "TX")
      (footprint "eagle-import:1,6_0,8")
      (libsource (lib "eagle-import") (part "1,6/0,8"))
    )
    (comp (ref "PAD267")
      (value "1,6/0,8")
      (footprint "eagle-import:1,6_0,8")
      (libsource (lib "eagle-import") (part "1,6/0,8"))
    )
    (comp (ref "PAD268")
      (value "1,6/0,8")
      (footprint "eagle-import:1,6_0,8")
      (libsource (lib "eagle-import") (part "1,6/0,8"))
    )
    (comp (ref "PAD276")
      (value "1,6/0,8")
      (footprint "eagle-import:1,6_0,8")
      (libsource (lib "eagle-import") (part "1,6/0,8"))
    )
    (comp (ref "PAD277")
      (value "1,6/0,8")
      (footprint "eagle-import:1,6_0,8")
      (libsource (lib "eagle-import") (part "1,6/0,8"))
    )
    (comp (ref "PAD285")
      (value "1,6/0,8")
      (footprint "eagle-import:1,6_0,8")
      (libsource (lib "eagle-import") (part "1,6/0,8"))
    )
    (comp (ref "PAD286")
      (value "1,6/0,8")
      (footprint "eagle-import:1,6_0,8")
      (libsource (lib "eagle-import") (part "1,6/0,8"))
    )
    (comp (ref "PAD294")
      (value "1,6/0,8")
      (footprint "eagle-import:1,6_0,8")
      (libsource (lib "eagle-import") (part "1,6/0,8"))
    )
    (comp (ref "PAD295")
      (value "1,6/0,8")
      (footprint "eagle-import:1,6_0,8")
      (libsource (lib "eagle-import") (part "1,6/0,8"))
    )
    (comp (ref "PAD303")
      (value "1,6/0,8")
      (footprint "eagle-import:1,6_0,8")
      (libsource (lib "eagle-import") (part "1,6/0,8"))
    )
    (comp (ref "PAD304")
      (value "1,6/0,8")
      (footprint "eagle-import:1,6_0,8")
      (libsource (lib "eagle-import") (part "1,6/0,8"))
    )
    (comp (ref "PAD312")
      (value "1,6/0,8")
      (footprint "eagle-import:1,6_0,8")
      (libsource (lib "eagle-import") (part "1,6/0,8"))
    )
    (comp (ref "PAD313")
      (value "1,6/0,8")
      (footprint "eagle-import:1,6_0,8")
      (libsource (lib "eagle-import") (part "1,6/0,8"))
    )
    (comp (ref "PAD321")
      (value "1,6/0,8")
      (footprint "eagle-import:1,6_0,8")
      (libsource (lib "eagle-import") (part "1,6/0,8"))
    )
    (comp (ref "PAD322")
      (value "1,6/0,8")
      (footprint "eagle-import:1,6_0,8")
      (libsource (lib "eagle-import") (part "1,6/0,8"))
    )
    (comp (ref "PAD323")
      (value "1,6/0,8")
      (footprint "eagle-import:1,6_0,8")
      (libsource (lib "eagle-import") (part "1,6/0,8"))
    )
    (comp (ref "PAD324")
      (value "1,6/0,8")
      (footprint "eagle-import:1,6_0,8")
      (libsource (lib "eagle-import") (part "1,6/0,8"))
    )
    (comp (ref "PAD325")
      (value "1,6/0,8")
      (footprint "eagle-import:1,6_0,8")
      (libsource (lib "eagle-import") (part "1,6/0,8"))
    )
    (comp (ref "PAD326")
      (value "1,6/0,8")
      (footprint "eagle-import:1,6_0,8")
      (libsource (lib "eagle-import") (part "1,6/0,8"))
    )
    (comp (ref "PAD327")
      (value "1,6/0,8")
      (footprint "eagle-import:1,6_0,8")
      (libsource (lib "eagle-import") (part "1,6/0,8"))
    )
    (comp (ref "PAD328")
      (value "1,6/0,8")
      (footprint "eagle-import:1,6_0,8")
      (libsource (lib "eagle-import") (part "1,6/0,8"))
    )
    (comp (ref "PAD329")
      (value "1,6/0,8")
      (footprint "eagle-import:1,6_0,8")
      (libsource (lib "eagle-import") (part "1,6/0,8"))
    )
    (comp (ref "PAD330")
      (value "1,6/0,8")
      (footprint "eagle-import:1,6_0,8")
      (libsource (lib "eagle-import") (part "1,6/0,8"))
    )
    (comp (ref "PAD331")
      (value "1,6/0,8")
      (footprint "eagle-import:1,6_0,8")
      (libsource (lib "eagle-import") (part "1,6/0,8"))
    )
    (comp (ref "PAD339")
      (value "1,6/0,8")
      (footprint "eagle-import:1,6_0,8")
      (libsource (lib "eagle-import") (part "1,6/0,8"))
    )
    (comp (ref "PAD340")
      (value "1,6/0,8")
      (footprint "eagle-import:1,6_0,8")
      (libsource (lib "eagle-import") (part "1,6/0,8"))
    )
    (comp (ref "PAD348")
      (value "1,6/0,8")
      (footprint "eagle-import:1,6_0,8")
      (libsource (lib "eagle-import") (part "1,6/0,8"))
    )
    (comp (ref "PAD349")
      (value "1,6/0,8")
      (footprint "eagle-import:1,6_0,8")
      (libsource (lib "eagle-import") (part "1,6/0,8"))
    )
    (comp (ref "PAD357")
      (value "1,6/0,8")
      (footprint "eagle-import:1,6_0,8")
      (libsource (lib "eagle-import") (part "1,6/0,8"))
    )
    (comp (ref "PAD358")
      (value "1,6/0,8")
      (footprint "eagle-import:1,6_0,8")
      (libsource (lib "eagle-import") (part "1,6/0,8"))
    )
    (comp (ref "PAD366")
      (value "1,6/0,8")
      (footprint "eagle-import:1,6_0,8")
      (libsource (lib "eagle-import") (part "1,6/0,8"))
    )
    (comp (ref "PAD367")
      (value "1,6/0,8")
      (footprint "eagle-import:1,6_0,8")
      (libsource (lib "eagle-import") (part "1,6/0,8"))
    )
    (comp (ref "PAD375")
      (value "1,6/0,8")
      (footprint "eagle-import:1,6_0,8")
      (libsource (lib "eagle-import") (part "1,6/0,8"))
    )
    (comp (ref "PAD376")
      (value "1,6/0,8")
      (footprint "eagle-import:1,6_0,8")
      (libsource (lib "eagle-import") (part "1,6/0,8"))
    )
    (comp (ref "PAD384")
      (value "1,6/0,8")
      (footprint "eagle-import:1,6_0,8")
      (libsource (lib "eagle-import") (part "1,6/0,8"))
    )
    (comp (ref "PAD390")
      (value "1,6/0,8")
      (footprint "eagle-import:1,6_0,8")
      (libsource (lib "eagle-import") (part "1,6/0,8"))
    )
    (comp (ref "PAD395")
      (value "1,6/0,8")
      (footprint "eagle-import:1,6_0,8")
      (libsource (lib "eagle-import") (part "1,6/0,8"))
    )
    (comp (ref "PAD396")
      (value "1,6/0,8")
      (footprint "eagle-import:1,6_0,8")
      (libsource (lib "eagle-import") (part "1,6/0,8"))
    )
    (comp (ref "PAD397")
      (value "RX")
      (footprint "eagle-import:1,6_0,8")
      (libsource (lib "eagle-import") (part "1,6/0,8"))
    )
    (comp (ref "PAD398")
      (value "1,6/0,8")
      (footprint "eagle-import:1,6_0,8")
      (libsource (lib "eagle-import") (part "1,6/0,8"))
    )
    (comp (ref "PAD399")
      (value "1,6/0,8")
      (footprint "eagle-import:1,6_0,8")
      (libsource (lib "eagle-import") (part "1,6/0,8"))
    )
    (comp (ref "PAD400")
      (value "1,6/0,8")
      (footprint "eagle-import:1,6_0,8")
      (libsource (lib "eagle-import") (part "1,6/0,8"))
    )
    (comp (ref "PAD401")
      (value "5")
      (footprint "eagle-import:1,6_0,8")
      (libsource (lib "eagle-import") (part "1,6/0,8"))
    )
    (comp (ref "PAD402")
      (value "1,6/0,8")
      (footprint "eagle-import:1,6_0,8")
      (libsource (lib "eagle-import") (part "1,6/0,8"))
    )
    (comp (ref "PAD403")
      (value "1,6/0,8")
      (footprint "eagle-import:1,6_0,8")
      (libsource (lib "eagle-import") (part "1,6/0,8"))
    )
    (comp (ref "PAD404")
      (value "1,6/0,8")
      (footprint "eagle-import:1,6_0,8")
      (libsource (lib "eagle-import") (part "1,6/0,8"))
    )
    (comp (ref "PAD405")
      (value "4")
      (footprint "eagle-import:1,6_0,8")
      (libsource (lib "eagle-import") (part "1,6/0,8"))
    )
    (comp (ref "PAD406")
      (value "1,6/0,8")
      (footprint "eagle-import:1,6_0,8")
      (libsource (lib "eagle-import") (part "1,6/0,8"))
    )
    (comp (ref "PAD407")
      (value "1,6/0,8")
      (footprint "eagle-import:1,6_0,8")
      (libsource (lib "eagle-import") (part "1,6/0,8"))
    )
    (comp (ref "PAD408")
      (value "1,6/0,8")
      (footprint "eagle-import:1,6_0,8")
      (libsource (lib "eagle-import") (part "1,6/0,8"))
    )
    (comp (ref "PAD409")
      (value "0")
      (footprint "eagle-import:1,6_0,8")
      (libsource (lib "eagle-import") (part "1,6/0,8"))
    )
    (comp (ref "PAD410")
      (value "1,6/0,8")
      (footprint "eagle-import:1,6_0,8")
      (libsource (lib "eagle-import") (part "1,6/0,8"))
    )
    (comp (ref "PAD411")
      (value "1,6/0,8")
      (footprint "eagle-import:1,6_0,8")
      (libsource (lib "eagle-import") (part "1,6/0,8"))
    )
    (comp (ref "PAD412")
      (value "1,6/0,8")
      (footprint "eagle-import:1,6_0,8")
      (libsource (lib "eagle-import") (part "1,6/0,8"))
    )
    (comp (ref "PAD413")
      (value "2")
      (footprint "eagle-import:1,6_0,8")
      (libsource (lib "eagle-import") (part "1,6/0,8"))
    )
    (comp (ref "PAD414")
      (value "1,6/0,8")
      (footprint "eagle-import:1,6_0,8")
      (libsource (lib "eagle-import") (part "1,6/0,8"))
    )
    (comp (ref "PAD415")
      (value "1,6/0,8")
      (footprint "eagle-import:1,6_0,8")
      (libsource (lib "eagle-import") (part "1,6/0,8"))
    )
    (comp (ref "PAD416")
      (value "1,6/0,8")
      (footprint "eagle-import:1,6_0,8")
      (libsource (lib "eagle-import") (part "1,6/0,8"))
    )
    (comp (ref "PAD417")
      (value "1,6/0,8")
      (footprint "eagle-import:1,6_0,8")
      (libsource (lib "eagle-import") (part "1,6/0,8"))
    )
    (comp (ref "PAD418")
      (value "1,6/0,8")
      (footprint "eagle-import:1,6_0,8")
      (libsource (lib "eagle-import") (part "1,6/0,8"))
    )
    (comp (ref "PAD419")
      (value "1,6/0,8")
      (footprint "eagle-import:1,6_0,8")
      (libsource (lib "eagle-import") (part "1,6/0,8"))
    )
    (comp (ref "PAD420")
      (value "1,6/0,8")
      (footprint "eagle-import:1,6_0,8")
      (libsource (lib "eagle-import") (part "1,6/0,8"))
    )
    (comp (ref "PAD421")
      (value "1,6/0,8")
      (footprint "eagle-import:1,6_0,8")
      (libsource (lib "eagle-import") (part "1,6/0,8"))
    )
    (comp (ref "PAD422")
      (value "1,6/0,8")
      (footprint "eagle-import:1,6_0,8")
      (libsource (lib "eagle-import") (part "1,6/0,8"))
    )
    (comp (ref "PAD423")
      (value "1,6/0,8")
      (footprint "eagle-import:1,6_0,8")
      (libsource (lib "eagle-import") (part "1,6/0,8"))
    )
    (comp (ref "PAD424")
      (value "1,6/0,8")
      (footprint "eagle-import:1,6_0,8")
      (libsource (lib "eagle-import") (part "1,6/0,8"))
    )
    (comp (ref "PAD425")
      (value "1,6/0,8")
      (footprint "eagle-import:1,6_0,8")
      (libsource (lib "eagle-import") (part "1,6/0,8"))
    )
    (comp (ref "PAD426")
      (value "1,6/0,8")
      (footprint "eagle-import:1,6_0,8")
      (libsource (lib "eagle-import") (part "1,6/0,8"))
    )
    (comp (ref "PAD427")
      (value "1,6/0,8")
      (footprint "eagle-import:1,6_0,8")
      (libsource (lib "eagle-import") (part "1,6/0,8"))
    )
    (comp (ref "PAD428")
      (value "1,6/0,8")
      (footprint "eagle-import:1,6_0,8")
      (libsource (lib "eagle-import") (part "1,6/0,8"))
    )
    (comp (ref "PAD429")
      (value "1,6/0,8")
      (footprint "eagle-import:1,6_0,8")
      (libsource (lib "eagle-import") (part "1,6/0,8"))
    )
    (comp (ref "PAD430")
      (value "1,6/0,8")
      (footprint "eagle-import:1,6_0,8")
      (libsource (lib "eagle-import") (part "1,6/0,8"))
    )
    (comp (ref "PAD431")
      (value "1,6/0,8")
      (footprint "eagle-import:1,6_0,8")
      (libsource (lib "eagle-import") (part "1,6/0,8"))
    )
    (comp (ref "PAD432")
      (value "1,6/0,8")
      (footprint "eagle-import:1,6_0,8")
      (libsource (lib "eagle-import") (part "1,6/0,8"))
    )
    (comp (ref "PAD433")
      (value "1,6/0,8")
      (footprint "eagle-import:1,6_0,8")
      (libsource (lib "eagle-import") (part "1,6/0,8"))
    )
    (comp (ref "PAD434")
      (value "1,6/0,8")
      (footprint "eagle-import:1,6_0,8")
      (libsource (lib "eagle-import") (part "1,6/0,8"))
    )
    (comp (ref "PAD435")
      (value "1,6/0,8")
      (footprint "eagle-import:1,6_0,8")
      (libsource (lib "eagle-import") (part "1,6/0,8"))
    )
    (comp (ref "PAD436")
      (value "1,6/0,8")
      (footprint "eagle-import:1,6_0,8")
      (libsource (lib "eagle-import") (part "1,6/0,8"))
    )
    (comp (ref "PAD437")
      (value "1,6/0,8")
      (footprint "eagle-import:1,6_0,8")
      (libsource (lib "eagle-import") (part "1,6/0,8"))
    )
    (comp (ref "PAD438")
      (value "1,6/0,8")
      (footprint "eagle-import:1,6_0,8")
      (libsource (lib "eagle-import") (part "1,6/0,8"))
    )
    (comp (ref "PAD439")
      (value "1,6/0,8")
      (footprint "eagle-import:1,6_0,8")
      (libsource (lib "eagle-import") (part "1,6/0,8"))
    )
    (comp (ref "PAD440")
      (value "1,6/0,8")
      (footprint "eagle-import:1,6_0,8")
      (libsource (lib "eagle-import") (part "1,6/0,8"))
    )
    (comp (ref "PAD441")
      (value "1,6/0,8")
      (footprint "eagle-import:1,6_0,8")
      (libsource (lib "eagle-import") (part "1,6/0,8"))
    )
    (comp (ref "PAD442")
      (value "1,6/0,8")
      (footprint "eagle-import:1,6_0,8")
      (libsource (lib "eagle-import") (part "1,6/0,8"))
    )
    (comp (ref "PAD443")
      (value "1,6/0,8")
      (footprint "eagle-import:1,6_0,8")
      (libsource (lib "eagle-import") (part "1,6/0,8"))
    )
    (comp (ref "PAD444")
      (value "1,6/0,8")
      (footprint "eagle-import:1,6_0,8")
      (libsource (lib "eagle-import") (part "1,6/0,8"))
    )
    (comp (ref "PAD445")
      (value "1,6/0,8")
      (footprint "eagle-import:1,6_0,8")
      (libsource (lib "eagle-import") (part "1,6/0,8"))
    )
    (comp (ref "PAD446")
      (value "1,6/0,8")
      (footprint "eagle-import:1,6_0,8")
      (libsource (lib "eagle-import") (part "1,6/0,8"))
    )
    (comp (ref "PAD447")
      (value "1,6/0,8")
      (footprint "eagle-import:1,6_0,8")
      (libsource (lib "eagle-import") (part "1,6/0,8"))
    )
    (comp (ref "PAD448")
      (value "1,6/0,8")
      (footprint "eagle-import:1,6_0,8")
      (libsource (lib "eagle-import") (part "1,6/0,8"))
    )
    (comp (ref "PAD449")
      (value "1,6/0,8")
      (footprint "eagle-import:1,6_0,8")
      (libsource (lib "eagle-import") (part "1,6/0,8"))
    )
    (comp (ref "PAD450")
      (value "1,6/0,8")
      (footprint "eagle-import:1,6_0,8")
      (libsource (lib "eagle-import") (part "1,6/0,8"))
    )
    (comp (ref "PAD451")
      (value "1,6/0,8")
      (footprint "eagle-import:1,6_0,8")
      (libsource (lib "eagle-import") (part "1,6/0,8"))
    )
    (comp (ref "PAD452")
      (value "1,6/0,8")
      (footprint "eagle-import:1,6_0,8")
      (libsource (lib "eagle-import") (part "1,6/0,8"))
    )
    (comp (ref "PAD453")
      (value "1,6/0,8")
      (footprint "eagle-import:1,6_0,8")
      (libsource (lib "eagle-import") (part "1,6/0,8"))
    )
    (comp (ref "PAD454")
      (value "1,6/0,8")
      (footprint "eagle-import:1,6_0,8")
      (libsource (lib "eagle-import") (part "1,6/0,8"))
    )
    (comp (ref "PAD455")
      (value "1,6/0,8")
      (footprint "eagle-import:1,6_0,8")
      (libsource (lib "eagle-import") (part "1,6/0,8"))
    )
    (comp (ref "PAD456")
      (value "1,6/0,8")
      (footprint "eagle-import:1,6_0,8")
      (libsource (lib "eagle-import") (part "1,6/0,8"))
    )
    (comp (ref "PAD457")
      (value "1,6/0,8")
      (footprint "eagle-import:1,6_0,8")
      (libsource (lib "eagle-import") (part "1,6/0,8"))
    )
    (comp (ref "PAD458")
      (value "1,6/0,8")
      (footprint "eagle-import:1,6_0,8")
      (libsource (lib "eagle-import") (part "1,6/0,8"))
    )
    (comp (ref "PAD459")
      (value "1,6/0,8")
      (footprint "eagle-import:1,6_0,8")
      (libsource (lib "eagle-import") (part "1,6/0,8"))
    )
    (comp (ref "PAD460")
      (value "1,6/0,8")
      (footprint "eagle-import:1,6_0,8")
      (libsource (lib "eagle-import") (part "1,6/0,8"))
    )
    (comp (ref "PAD461")
      (value "1,6/0,8")
      (footprint "eagle-import:1,6_0,8")
      (libsource (lib "eagle-import") (part "1,6/0,8"))
    )
    (comp (ref "PAD462")
      (value "1,6/0,8")
      (footprint "eagle-import:1,6_0,8")
      (libsource (lib "eagle-import") (part "1,6/0,8"))
    )
    (comp (ref "PAD463")
      (value "1,6/0,8")
      (footprint "eagle-import:1,6_0,8")
      (libsource (lib "eagle-import") (part "1,6/0,8"))
    )
    (comp (ref "PAD471")
      (value "1,6/0,8")
      (footprint "eagle-import:1,6_0,8")
      (libsource (lib "eagle-import") (part "1,6/0,8"))
    )
    (comp (ref "PAD472")
      (value "1,6/0,8")
      (footprint "eagle-import:1,6_0,8")
      (libsource (lib "eagle-import") (part "1,6/0,8"))
    )
    (comp (ref "PAD473")
      (value "1,6/0,8")
      (footprint "eagle-import:1,6_0,8")
      (libsource (lib "eagle-import") (part "1,6/0,8"))
    )
    (comp (ref "PAD474")
      (value "1,6/0,8")
      (footprint "eagle-import:1,6_0,8")
      (libsource (lib "eagle-import") (part "1,6/0,8"))
    )
    (comp (ref "PAD475")
      (value "1,6/0,8")
      (footprint "eagle-import:1,6_0,8")
      (libsource (lib "eagle-import") (part "1,6/0,8"))
    )
    (comp (ref "PAD476")
      (value "1,6/0,8")
      (footprint "eagle-import:1,6_0,8")
      (libsource (lib "eagle-import") (part "1,6/0,8"))
    )
    (comp (ref "PAD477")
      (value "1,6/0,8")
      (footprint "eagle-import:1,6_0,8")
      (libsource (lib "eagle-import") (part "1,6/0,8"))
    )
    (comp (ref "PAD478")
      (value "1,6/0,8")
      (footprint "eagle-import:1,6_0,8")
      (libsource (lib "eagle-import") (part "1,6/0,8"))
    )
    (comp (ref "PAD479")
      (value "1,6/0,8")
      (footprint "eagle-import:1,6_0,8")
      (libsource (lib "eagle-import") (part "1,6/0,8"))
    )
    (comp (ref "PAD480")
      (value "1,6/0,8")
      (footprint "eagle-import:1,6_0,8")
      (libsource (lib "eagle-import") (part "1,6/0,8"))
    )
    (comp (ref "PAD481")
      (value "1,6/0,8")
      (footprint "eagle-import:1,6_0,8")
      (libsource (lib "eagle-import") (part "1,6/0,8"))
    )
    (comp (ref "PAD482")
      (value "1,6/0,8")
      (footprint "eagle-import:1,6_0,8")
      (libsource (lib "eagle-import") (part "1,6/0,8"))
    )
    (comp (ref "PAD483")
      (value "1,6/0,8")
      (footprint "eagle-import:1,6_0,8")
      (libsource (lib "eagle-import") (part "1,6/0,8"))
    )
    (comp (ref "PAD484")
      (value "1,6/0,8")
      (footprint "eagle-import:1,6_0,8")
      (libsource (lib "eagle-import") (part "1,6/0,8"))
    )
    (comp (ref "PAD485")
      (value "1,6/0,8")
      (footprint "eagle-import:1,6_0,8")
      (libsource (lib "eagle-import") (part "1,6/0,8"))
    )
    (comp (ref "PAD486")
      (value "1,6/0,8")
      (footprint "eagle-import:1,6_0,8")
      (libsource (lib "eagle-import") (part "1,6/0,8"))
    )
    (comp (ref "PAD487")
      (value "1,6/0,8")
      (footprint "eagle-import:1,6_0,8")
      (libsource (lib "eagle-import") (part "1,6/0,8"))
    )
    (comp (ref "PAD488")
      (value "1,6/0,8")
      (footprint "eagle-import:1,6_0,8")
      (libsource (lib "eagle-import") (part "1,6/0,8"))
    )
    (comp (ref "PAD489")
      (value "1,6/0,8")
      (footprint "eagle-import:1,6_0,8")
      (libsource (lib "eagle-import") (part "1,6/0,8"))
    )
    (comp (ref "PAD490")
      (value "1,6/0,8")
      (footprint "eagle-import:1,6_0,8")
      (libsource (lib "eagle-import") (part "1,6/0,8"))
    )
    (comp (ref "PAD491")
      (value "1,6/0,8")
      (footprint "eagle-import:1,6_0,8")
      (libsource (lib "eagle-import") (part "1,6/0,8"))
    )
    (comp (ref "PAD492")
      (value "1,6/0,8")
      (footprint "eagle-import:1,6_0,8")
      (libsource (lib "eagle-import") (part "1,6/0,8"))
    )
    (comp (ref "PAD493")
      (value "1,6/0,8")
      (footprint "eagle-import:1,6_0,8")
      (libsource (lib "eagle-import") (part "1,6/0,8"))
    )
    (comp (ref "PAD494")
      (value "1,6/0,8")
      (footprint "eagle-import:1,6_0,8")
      (libsource (lib "eagle-import") (part "1,6/0,8"))
    )
    (comp (ref "PAD495")
      (value "1,6/0,8")
      (footprint "eagle-import:1,6_0,8")
      (libsource (lib "eagle-import") (part "1,6/0,8"))
    )
    (comp (ref "PAD496")
      (value "1,6/0,8")
      (footprint "eagle-import:1,6_0,8")
      (libsource (lib "eagle-import") (part "1,6/0,8"))
    )
    (comp (ref "PAD497")
      (value "1,6/0,8")
      (footprint "eagle-import:1,6_0,8")
      (libsource (lib "eagle-import") (part "1,6/0,8"))
    )
    (comp (ref "PAD498")
      (value "1,6/0,8")
      (footprint "eagle-import:1,6_0,8")
      (libsource (lib "eagle-import") (part "1,6/0,8"))
    )
    (comp (ref "PAD499")
      (value "1,6/0,8")
      (footprint "eagle-import:1,6_0,8")
      (libsource (lib "eagle-import") (part "1,6/0,8"))
    )
    (comp (ref "PAD500")
      (value "1,6/0,8")
      (footprint "eagle-import:1,6_0,8")
      (libsource (lib "eagle-import") (part "1,6/0,8"))
    )
    (comp (ref "PAD501")
      (value "1,6/0,8")
      (footprint "eagle-import:1,6_0,8")
      (libsource (lib "eagle-import") (part "1,6/0,8"))
    )
    (comp (ref "PAD502")
      (value "1,6/0,8")
      (footprint "eagle-import:1,6_0,8")
      (libsource (lib "eagle-import") (part "1,6/0,8"))
    )
    (comp (ref "PAD503")
      (value "1,6/0,8")
      (footprint "eagle-import:1,6_0,8")
      (libsource (lib "eagle-import") (part "1,6/0,8"))
    )
    (comp (ref "PAD504")
      (value "1,6/0,8")
      (footprint "eagle-import:1,6_0,8")
      (libsource (lib "eagle-import") (part "1,6/0,8"))
    )
    (comp (ref "PAD505")
      (value "1,6/0,8")
      (footprint "eagle-import:1,6_0,8")
      (libsource (lib "eagle-import") (part "1,6/0,8"))
    )
    (comp (ref "PAD506")
      (value "1,6/0,8")
      (footprint "eagle-import:1,6_0,8")
      (libsource (lib "eagle-import") (part "1,6/0,8"))
    )
    (comp (ref "PAD507")
      (value "1,6/0,8")
      (footprint "eagle-import:1,6_0,8")
      (libsource (lib "eagle-import") (part "1,6/0,8"))
    )
    (comp (ref "PAD508")
      (value "1,6/0,8")
      (footprint "eagle-import:1,6_0,8")
      (libsource (lib "eagle-import") (part "1,6/0,8"))
    )
    (comp (ref "PAD509")
      (value "1,6/0,8")
      (footprint "eagle-import:1,6_0,8")
      (libsource (lib "eagle-import") (part "1,6/0,8"))
    )
    (comp (ref "PAD510")
      (value "1,6/0,8")
      (footprint "eagle-import:1,6_0,8")
      (libsource (lib "eagle-import") (part "1,6/0,8"))
    )
    (comp (ref "PAD511")
      (value "1,6/0,8")
      (footprint "eagle-import:1,6_0,8")
      (libsource (lib "eagle-import") (part "1,6/0,8"))
    )
    (comp (ref "PAD512")
      (value "1,6/0,8")
      (footprint "eagle-import:1,6_0,8")
      (libsource (lib "eagle-import") (part "1,6/0,8"))
    )
    (comp (ref "PAD513")
      (value "1,6/0,8")
      (footprint "eagle-import:1,6_0,8")
      (libsource (lib "eagle-import") (part "1,6/0,8"))
    )
    (comp (ref "PAD514")
      (value "1,6/0,8")
      (footprint "eagle-import:1,6_0,8")
      (libsource (lib "eagle-import") (part "1,6/0,8"))
    )
    (comp (ref "PAD515")
      (value "1,6/0,8")
      (footprint "eagle-import:1,6_0,8")
      (libsource (lib "eagle-import") (part "1,6/0,8"))
    )
    (comp (ref "PAD516")
      (value "1,6/0,8")
      (footprint "eagle-import:1,6_0,8")
      (libsource (lib "eagle-import") (part "1,6/0,8"))
    )
    (comp (ref "PAD517")
      (value "1,6/0,8")
      (footprint "eagle-import:1,6_0,8")
      (libsource (lib "eagle-import") (part "1,6/0,8"))
    )
    (comp (ref "PAD518")
      (value "1,6/0,8")
      (footprint "eagle-import:1,6_0,8")
      (libsource (lib "eagle-import") (part "1,6/0,8"))
    )
    (comp (ref "PAD519")
      (value "1,6/0,8")
      (footprint "eagle-import:1,6_0,8")
      (libsource (lib "eagle-import") (part "1,6/0,8"))
    )
    (comp (ref "PAD520")
      (value "1,6/0,8")
      (footprint "eagle-import:1,6_0,8")
      (libsource (lib "eagle-import") (part "1,6/0,8"))
    )
    (comp (ref "PAD521")
      (value "1,6/0,8")
      (footprint "eagle-import:1,6_0,8")
      (libsource (lib "eagle-import") (part "1,6/0,8"))
    )
    (comp (ref "PAD522")
      (value "1,6/0,8")
      (footprint "eagle-import:1,6_0,8")
      (libsource (lib "eagle-import") (part "1,6/0,8"))
    )
    (comp (ref "PAD523")
      (value "1,6/0,8")
      (footprint "eagle-import:1,6_0,8")
      (libsource (lib "eagle-import") (part "1,6/0,8"))
    )
    (comp (ref "PAD524")
      (value "1,6/0,8")
      (footprint "eagle-import:1,6_0,8")
      (libsource (lib "eagle-import") (part "1,6/0,8"))
    )
    (comp (ref "PAD525")
      (value "1,6/0,8")
      (footprint "eagle-import:1,6_0,8")
      (libsource (lib "eagle-import") (part "1,6/0,8"))
    )
    (comp (ref "PAD526")
      (value "1,6/0,8")
      (footprint "eagle-import:1,6_0,8")
      (libsource (lib "eagle-import") (part "1,6/0,8"))
    )
    (comp (ref "PAD527")
      (value "1,6/0,8")
      (footprint "eagle-import:1,6_0,8")
      (libsource (lib "eagle-import") (part "1,6/0,8"))
    )
    (comp (ref "PAD528")
      (value "1,6/0,8")
      (footprint "eagle-import:1,6_0,8")
      (libsource (lib "eagle-import") (part "1,6/0,8"))
    )
    (comp (ref "PAD529")
      (value "1,6/0,8")
      (footprint "eagle-import:1,6_0,8")
      (libsource (lib "eagle-import") (part "1,6/0,8"))
    )
    (comp (ref "PAD530")
      (value "1,6/0,8")
      (footprint "eagle-import:1,6_0,8")
      (libsource (lib "eagle-import") (part "1,6/0,8"))
    )
    (comp (ref "PAD531")
      (value "1,6/0,8")
      (footprint "eagle-import:1,6_0,8")
      (libsource (lib "eagle-import") (part "1,6/0,8"))
    )
    (comp (ref "PAD532")
      (value "1,6/0,8")
      (footprint "eagle-import:1,6_0,8")
      (libsource (lib "eagle-import") (part "1,6/0,8"))
    )
    (comp (ref "PAD533")
      (value "1,6/0,8")
      (footprint "eagle-import:1,6_0,8")
      (libsource (lib "eagle-import") (part "1,6/0,8"))
    )
    (comp (ref "PAD534")
      (value "1,6/0,8")
      (footprint "eagle-import:1,6_0,8")
      (libsource (lib "eagle-import") (part "1,6/0,8"))
    )
    (comp (ref "PAD535")
      (value "1,6/0,8")
      (footprint "eagle-import:1,6_0,8")
      (libsource (lib "eagle-import") (part "1,6/0,8"))
    )
    (comp (ref "PAD536")
      (value "1,6/0,8")
      (footprint "eagle-import:1,6_0,8")
      (libsource (lib "eagle-import") (part "1,6/0,8"))
    )
    (comp (ref "PAD537")
      (value "1,6/0,8")
      (footprint "eagle-import:1,6_0,8")
      (libsource (lib "eagle-import") (part "1,6/0,8"))
    )
    (comp (ref "PAD538")
      (value "1,6/0,8")
      (footprint "eagle-import:1,6_0,8")
      (libsource (lib "eagle-import") (part "1,6/0,8"))
    )
    (comp (ref "PAD539")
      (value "1,6/0,8")
      (footprint "eagle-import:1,6_0,8")
      (libsource (lib "eagle-import") (part "1,6/0,8"))
    )
    (comp (ref "PAD540")
      (value "1,6/0,8")
      (footprint "eagle-import:1,6_0,8")
      (libsource (lib "eagle-import") (part "1,6/0,8"))
    )
    (comp (ref "PAD541")
      (value "1,6/0,8")
      (footprint "eagle-import:1,6_0,8")
      (libsource (lib "eagle-import") (part "1,6/0,8"))
    )
    (comp (ref "PAD542")
      (value "1,6/0,8")
      (footprint "eagle-import:1,6_0,8")
      (libsource (lib "eagle-import") (part "1,6/0,8"))
    )
    (comp (ref "PAD543")
      (value "1,6/0,8")
      (footprint "eagle-import:1,6_0,8")
      (libsource (lib "eagle-import") (part "1,6/0,8"))
    )
    (comp (ref "PAD544")
      (value "1,6/0,8")
      (footprint "eagle-import:1,6_0,8")
      (libsource (lib "eagle-import") (part "1,6/0,8"))
    )
    (comp (ref "PAD547")
      (value "1,6/0,8")
      (footprint "eagle-import:1,6_0,8")
      (libsource (lib "eagle-import") (part "1,6/0,8"))
    )
    (comp (ref "PAD548")
      (value "1,6/0,8")
      (footprint "eagle-import:1,6_0,8")
      (libsource (lib "eagle-import") (part "1,6/0,8"))
    )
    (comp (ref "PAD549")
      (value "1,6/0,8")
      (footprint "eagle-import:1,6_0,8")
      (libsource (lib "eagle-import") (part "1,6/0,8"))
    )
    (comp (ref "PAD550")
      (value "1,6/0,8")
      (footprint "eagle-import:1,6_0,8")
      (libsource (lib "eagle-import") (part "1,6/0,8"))
    )
    (comp (ref "PAD551")
      (value "1,6/0,8")
      (footprint "eagle-import:1,6_0,8")
      (libsource (lib "eagle-import") (part "1,6/0,8"))
    )
    (comp (ref "PAD554")
      (value "1,6/0,8")
      (footprint "eagle-import:1,6_0,8")
      (libsource (lib "eagle-import") (part "1,6/0,8"))
    )
    (comp (ref "PAD555")
      (value "1,6/0,8")
      (footprint "eagle-import:1,6_0,8")
      (libsource (lib "eagle-import") (part "1,6/0,8"))
    )
    (comp (ref "PAD556")
      (value "1,6/0,8")
      (footprint "eagle-import:1,6_0,8")
      (libsource (lib "eagle-import") (part "1,6/0,8"))
    )
    (comp (ref "PAD557")
      (value "1,6/0,8")
      (footprint "eagle-import:1,6_0,8")
      (libsource (lib "eagle-import") (part "1,6/0,8"))
    )
    (comp (ref "PAD558")
      (value "1,6/0,8")
      (footprint "eagle-import:1,6_0,8")
      (libsource (lib "eagle-import") (part "1,6/0,8"))
    )
    (comp (ref "PAD560")
      (value "1,6/0,8")
      (footprint "eagle-import:1,6_0,8")
      (libsource (lib "eagle-import") (part "1,6/0,8"))
    )
    (comp (ref "PAD561")
      (value "1,6/0,8")
      (footprint "eagle-import:1,6_0,8")
      (libsource (lib "eagle-import") (part "1,6/0,8"))
    )
    (comp (ref "PAD562")
      (value "1,6/0,8")
      (footprint "eagle-import:1,6_0,8")
      (libsource (lib "eagle-import") (part "1,6/0,8"))
    )
    (comp (ref "PAD563")
      (value "1,6/0,8")
      (footprint "eagle-import:1,6_0,8")
      (libsource (lib "eagle-import") (part "1,6/0,8"))
    )
    (comp (ref "PAD564")
      (value "1,6/0,8")
      (footprint "eagle-import:1,6_0,8")
      (libsource (lib "eagle-import") (part "1,6/0,8"))
    )
    (comp (ref "PAD565")
      (value "1,6/0,8")
      (footprint "eagle-import:1,6_0,8")
      (libsource (lib "eagle-import") (part "1,6/0,8"))
    )
    (comp (ref "PAD566")
      (value "1,6/0,8")
      (footprint "eagle-import:1,6_0,8")
      (libsource (lib "eagle-import") (part "1,6/0,8"))
    )
    (comp (ref "PAD567")
      (value "1,6/0,8")
      (footprint "eagle-import:1,6_0,8")
      (libsource (lib "eagle-import") (part "1,6/0,8"))
    )
    (comp (ref "PAD568")
      (value "1,6/0,8")
      (footprint "eagle-import:1,6_0,8")
      (libsource (lib "eagle-import") (part "1,6/0,8"))
    )
    (comp (ref "PAD569")
      (value "1,6/0,8")
      (footprint "eagle-import:1,6_0,8")
      (libsource (lib "eagle-import") (part "1,6/0,8"))
    )
    (comp (ref "PAD570")
      (value "1,6/0,8")
      (footprint "eagle-import:1,6_0,8")
      (libsource (lib "eagle-import") (part "1,6/0,8"))
    )
    (comp (ref "PAD571")
      (value "1,6/0,8")
      (footprint "eagle-import:1,6_0,8")
      (libsource (lib "eagle-import") (part "1,6/0,8"))
    )
    (comp (ref "PAD572")
      (value "1,6/0,8")
      (footprint "eagle-import:1,6_0,8")
      (libsource (lib "eagle-import") (part "1,6/0,8"))
    )
    (comp (ref "PAD573")
      (value "1,6/0,8")
      (footprint "eagle-import:1,6_0,8")
      (libsource (lib "eagle-import") (part "1,6/0,8"))
    )
    (comp (ref "PAD574")
      (value "1,6/0,8")
      (footprint "eagle-import:1,6_0,8")
      (libsource (lib "eagle-import") (part "1,6/0,8"))
    )
    (comp (ref "PAD575")
      (value "1,6/0,8")
      (footprint "eagle-import:1,6_0,8")
      (libsource (lib "eagle-import") (part "1,6/0,8"))
    )
    (comp (ref "PAD576")
      (value "1,6/0,8")
      (footprint "eagle-import:1,6_0,8")
      (libsource (lib "eagle-import") (part "1,6/0,8"))
    )
    (comp (ref "PAD577")
      (value "1,6/0,8")
      (footprint "eagle-import:1,6_0,8")
      (libsource (lib "eagle-import") (part "1,6/0,8"))
    )
    (comp (ref "PAD578")
      (value "1,6/0,8")
      (footprint "eagle-import:1,6_0,8")
      (libsource (lib "eagle-import") (part "1,6/0,8"))
    )
    (comp (ref "PAD579")
      (value "1,6/0,8")
      (footprint "eagle-import:1,6_0,8")
      (libsource (lib "eagle-import") (part "1,6/0,8"))
    )
    (comp (ref "PAD580")
      (value "1,6/0,8")
      (footprint "eagle-import:1,6_0,8")
      (libsource (lib "eagle-import") (part "1,6/0,8"))
    )
    (comp (ref "PAD581")
      (value "1,6/0,8")
      (footprint "eagle-import:1,6_0,8")
      (libsource (lib "eagle-import") (part "1,6/0,8"))
    )
    (comp (ref "PAD582")
      (value "1,6/0,8")
      (footprint "eagle-import:1,6_0,8")
      (libsource (lib "eagle-import") (part "1,6/0,8"))
    )
    (comp (ref "PAD583")
      (value "1,6/0,8")
      (footprint "eagle-import:1,6_0,8")
      (libsource (lib "eagle-import") (part "1,6/0,8"))
    )
    (comp (ref "PAD584")
      (value "1,6/0,8")
      (footprint "eagle-import:1,6_0,8")
      (libsource (lib "eagle-import") (part "1,6/0,8"))
    )
    (comp (ref "PAD585")
      (value "1,6/0,8")
      (footprint "eagle-import:1,6_0,8")
      (libsource (lib "eagle-import") (part "1,6/0,8"))
    )
    (comp (ref "PAD586")
      (value "1,6/0,8")
      (footprint "eagle-import:1,6_0,8")
      (libsource (lib "eagle-import") (part "1,6/0,8"))
    )
    (comp (ref "PAD587")
      (value "1,6/0,8")
      (footprint "eagle-import:1,6_0,8")
      (libsource (lib "eagle-import") (part "1,6/0,8"))
    )
    (comp (ref "PAD588")
      (value "1,6/0,8")
      (footprint "eagle-import:1,6_0,8")
      (libsource (lib "eagle-import") (part "1,6/0,8"))
    )
    (comp (ref "PAD589")
      (value "1,6/0,8")
      (footprint "eagle-import:1,6_0,8")
      (libsource (lib "eagle-import") (part "1,6/0,8"))
    )
    (comp (ref "PAD590")
      (value "1,6/0,8")
      (footprint "eagle-import:1,6_0,8")
      (libsource (lib "eagle-import") (part "1,6/0,8"))
    )
    (comp (ref "PAD591")
      (value "1,6/0,8")
      (footprint "eagle-import:1,6_0,8")
      (libsource (lib "eagle-import") (part "1,6/0,8"))
    )
    (comp (ref "PAD592")
      (value "1,6/0,8")
      (footprint "eagle-import:1,6_0,8")
      (libsource (lib "eagle-import") (part "1,6/0,8"))
    )
    (comp (ref "PAD593")
      (value "1,6/0,8")
      (footprint "eagle-import:1,6_0,8")
      (libsource (lib "eagle-import") (part "1,6/0,8"))
    )
    (comp (ref "PAD594")
      (value "1,6/0,8")
      (footprint "eagle-import:1,6_0,8")
      (libsource (lib "eagle-import") (part "1,6/0,8"))
    )
    (comp (ref "PAD595")
      (value "1,6/0,8")
      (footprint "eagle-import:1,6_0,8")
      (libsource (lib "eagle-import") (part "1,6/0,8"))
    )
    (comp (ref "PAD596")
      (value "1,6/0,8")
      (footprint "eagle-import:1,6_0,8")
      (libsource (lib "eagle-import") (part "1,6/0,8"))
    )
    (comp (ref "PAD597")
      (value "1,6/0,8")
      (footprint "eagle-import:1,6_0,8")
      (libsource (lib "eagle-import") (part "1,6/0,8"))
    )
    (comp (ref "PAD598")
      (value "1,6/0,8")
      (footprint "eagle-import:1,6_0,8")
      (libsource (lib "eagle-import") (part "1,6/0,8"))
    )
    (comp (ref "PAD599")
      (value "1,6/0,8")
      (footprint "eagle-import:1,6_0,8")
      (libsource (lib "eagle-import") (part "1,6/0,8"))
    )
    (comp (ref "PAD600")
      (value "1,6/0,8")
      (footprint "eagle-import:1,6_0,8")
      (libsource (lib "eagle-import") (part "1,6/0,8"))
    )
    (comp (ref "PAD601")
      (value "1,6/0,8")
      (footprint "eagle-import:1,6_0,8")
      (libsource (lib "eagle-import") (part "1,6/0,8"))
    )
    (comp (ref "PAD602")
      (value "1,6/0,8")
      (footprint "eagle-import:1,6_0,8")
      (libsource (lib "eagle-import") (part "1,6/0,8"))
    )
    (comp (ref "PAD603")
      (value "1,6/0,8")
      (footprint "eagle-import:1,6_0,8")
      (libsource (lib "eagle-import") (part "1,6/0,8"))
    )
    (comp (ref "PAD604")
      (value "1,6/0,8")
      (footprint "eagle-import:1,6_0,8")
      (libsource (lib "eagle-import") (part "1,6/0,8"))
    )
    (comp (ref "PAD605")
      (value "1,6/0,8")
      (footprint "eagle-import:1,6_0,8")
      (libsource (lib "eagle-import") (part "1,6/0,8"))
    )
    (comp (ref "PAD606")
      (value "1,6/0,8")
      (footprint "eagle-import:1,6_0,8")
      (libsource (lib "eagle-import") (part "1,6/0,8"))
    )
    (comp (ref "PAD607")
      (value "1,6/0,8")
      (footprint "eagle-import:1,6_0,8")
      (libsource (lib "eagle-import") (part "1,6/0,8"))
    )
    (comp (ref "PAD608")
      (value "1,6/0,8")
      (footprint "eagle-import:1,6_0,8")
      (libsource (lib "eagle-import") (part "1,6/0,8"))
    )
    (comp (ref "PAD609")
      (value "1,6/0,8")
      (footprint "eagle-import:1,6_0,8")
      (libsource (lib "eagle-import") (part "1,6/0,8"))
    )
    (comp (ref "PAD610")
      (value "1,6/0,8")
      (footprint "eagle-import:1,6_0,8")
      (libsource (lib "eagle-import") (part "1,6/0,8"))
    )
    (comp (ref "PAD611")
      (value "1,6/0,8")
      (footprint "eagle-import:1,6_0,8")
      (libsource (lib "eagle-import") (part "1,6/0,8"))
    )
    (comp (ref "PAD612")
      (value "1,6/0,8")
      (footprint "eagle-import:1,6_0,8")
      (libsource (lib "eagle-import") (part "1,6/0,8"))
    )
    (comp (ref "PAD613")
      (value "1,6/0,8")
      (footprint "eagle-import:1,6_0,8")
      (libsource (lib "eagle-import") (part "1,6/0,8"))
    )
    (comp (ref "PAD614")
      (value "1,6/0,8")
      (footprint "eagle-import:1,6_0,8")
      (libsource (lib "eagle-import") (part "1,6/0,8"))
    )
    (comp (ref "PAD615")
      (value "1,6/0,8")
      (footprint "eagle-import:1,6_0,8")
      (libsource (lib "eagle-import") (part "1,6/0,8"))
    )
    (comp (ref "PAD617")
      (value "1,6/0,8")
      (footprint "eagle-import:1,6_0,8")
      (libsource (lib "eagle-import") (part "1,6/0,8"))
    )
    (comp (ref "PAD618")
      (value "1,6/0,8")
      (footprint "eagle-import:1,6_0,8")
      (libsource (lib "eagle-import") (part "1,6/0,8"))
    )
    (comp (ref "PAD619")
      (value "1,6/0,8")
      (footprint "eagle-import:1,6_0,8")
      (libsource (lib "eagle-import") (part "1,6/0,8"))
    )
    (comp (ref "PAD620")
      (value "1,6/0,8")
      (footprint "eagle-import:1,6_0,8")
      (libsource (lib "eagle-import") (part "1,6/0,8"))
    )
    (comp (ref "PAD621")
      (value "1,6/0,8")
      (footprint "eagle-import:1,6_0,8")
      (libsource (lib "eagle-import") (part "1,6/0,8"))
    )
    (comp (ref "PAD622")
      (value "15")
      (footprint "eagle-import:1,6_0,8")
      (libsource (lib "eagle-import") (part "1,6/0,8"))
    )
    (comp (ref "PAD623")
      (value "1,6/0,8")
      (footprint "eagle-import:1,6_0,8")
      (libsource (lib "eagle-import") (part "1,6/0,8"))
    )
    (comp (ref "PAD624")
      (value "1,6/0,8")
      (footprint "eagle-import:1,6_0,8")
      (libsource (lib "eagle-import") (part "1,6/0,8"))
    )
    (comp (ref "PAD625")
      (value "1,6/0,8")
      (footprint "eagle-import:1,6_0,8")
      (libsource (lib "eagle-import") (part "1,6/0,8"))
    )
    (comp (ref "PAD626")
      (value "SC")
      (footprint "eagle-import:1,6_0,8")
      (libsource (lib "eagle-import") (part "1,6/0,8"))
    )
    (comp (ref "PAD627")
      (value "AC")
      (footprint "eagle-import:1,6_0,8")
      (libsource (lib "eagle-import") (part "1,6/0,8"))
    )
    (comp (ref "PAD628")
      (value "1,6/0,8")
      (footprint "eagle-import:1,6_0,8")
      (libsource (lib "eagle-import") (part "1,6/0,8"))
    )
    (comp (ref "PAD629")
      (value "1,6/0,8")
      (footprint "eagle-import:1,6_0,8")
      (libsource (lib "eagle-import") (part "1,6/0,8"))
    )
    (comp (ref "PAD630")
      (value "1,6/0,8")
      (footprint "eagle-import:1,6_0,8")
      (libsource (lib "eagle-import") (part "1,6/0,8"))
    )
    (comp (ref "PAD631")
      (value "CH")
      (footprint "eagle-import:1,6_0,8")
      (libsource (lib "eagle-import") (part "1,6/0,8"))
    )
    (comp (ref "PAD632")
      (value "1,6/0,8")
      (footprint "eagle-import:1,6_0,8")
      (libsource (lib "eagle-import") (part "1,6/0,8"))
    )
    (comp (ref "PAD633")
      (value "1,6/0,8")
      (footprint "eagle-import:1,6_0,8")
      (libsource (lib "eagle-import") (part "1,6/0,8"))
    )
    (comp (ref "PAD634")
      (value "1,6/0,8")
      (footprint "eagle-import:1,6_0,8")
      (libsource (lib "eagle-import") (part "1,6/0,8"))
    )
    (comp (ref "PAD635")
      (value "16")
      (footprint "eagle-import:1,6_0,8")
      (libsource (lib "eagle-import") (part "1,6/0,8"))
    )
    (comp (ref "PAD636")
      (value "1,6/0,8")
      (footprint "eagle-import:1,6_0,8")
      (libsource (lib "eagle-import") (part "1,6/0,8"))
    )
    (comp (ref "PAD637")
      (value "1,6/0,8")
      (footprint "eagle-import:1,6_0,8")
      (libsource (lib "eagle-import") (part "1,6/0,8"))
    )
    (comp (ref "PAD638")
      (value "1,6/0,8")
      (footprint "eagle-import:1,6_0,8")
      (libsource (lib "eagle-import") (part "1,6/0,8"))
    )
    (comp (ref "PAD639")
      (value "14")
      (footprint "eagle-import:1,6_0,8")
      (libsource (lib "eagle-import") (part "1,6/0,8"))
    )
    (comp (ref "PAD640")
      (value "1,6/0,8")
      (footprint "eagle-import:1,6_0,8")
      (libsource (lib "eagle-import") (part "1,6/0,8"))
    )
    (comp (ref "PAD641")
      (value "1,6/0,8")
      (footprint "eagle-import:1,6_0,8")
      (libsource (lib "eagle-import") (part "1,6/0,8"))
    )
    (comp (ref "PAD642")
      (value "1,6/0,8")
      (footprint "eagle-import:1,6_0,8")
      (libsource (lib "eagle-import") (part "1,6/0,8"))
    )
    (comp (ref "PAD643")
      (value "1,6/0,8")
      (footprint "eagle-import:1,6_0,8")
      (libsource (lib "eagle-import") (part "1,6/0,8"))
    )
    (comp (ref "PAD644")
      (value "1,6/0,8")
      (footprint "eagle-import:1,6_0,8")
      (libsource (lib "eagle-import") (part "1,6/0,8"))
    )
    (comp (ref "PAD645")
      (value "1,6/0,8")
      (footprint "eagle-import:1,6_0,8")
      (libsource (lib "eagle-import") (part "1,6/0,8"))
    )
    (comp (ref "PAD646")
      (value "1,6/0,8")
      (footprint "eagle-import:1,6_0,8")
      (libsource (lib "eagle-import") (part "1,6/0,8"))
    )
    (comp (ref "PAD647")
      (value "1,6/0,8")
      (footprint "eagle-import:1,6_0,8")
      (libsource (lib "eagle-import") (part "1,6/0,8"))
    )
    (comp (ref "PAD648")
      (value "1,6/0,8")
      (footprint "eagle-import:1,6_0,8")
      (libsource (lib "eagle-import") (part "1,6/0,8"))
    )
    (comp (ref "PAD649")
      (value "1,6/0,8")
      (footprint "eagle-import:1,6_0,8")
      (libsource (lib "eagle-import") (part "1,6/0,8"))
    )
    (comp (ref "PAD650")
      (value "1,6/0,8")
      (footprint "eagle-import:1,6_0,8")
      (libsource (lib "eagle-import") (part "1,6/0,8"))
    )
    (comp (ref "PAD651")
      (value "1,6/0,8")
      (footprint "eagle-import:1,6_0,8")
      (libsource (lib "eagle-import") (part "1,6/0,8"))
    )
    (comp (ref "PAD652")
      (value "1,6/0,8")
      (footprint "eagle-import:1,6_0,8")
      (libsource (lib "eagle-import") (part "1,6/0,8"))
    )
    (comp (ref "PAD653")
      (value "1,6/0,8")
      (footprint "eagle-import:1,6_0,8")
      (libsource (lib "eagle-import") (part "1,6/0,8"))
    )
    (comp (ref "PAD654")
      (value "1,6/0,8")
      (footprint "eagle-import:1,6_0,8")
      (libsource (lib "eagle-import") (part "1,6/0,8"))
    )
    (comp (ref "PAD655")
      (value "1,6/0,8")
      (footprint "eagle-import:1,6_0,8")
      (libsource (lib "eagle-import") (part "1,6/0,8"))
    )
    (comp (ref "PAD656")
      (value "1,6/0,8")
      (footprint "eagle-import:1,6_0,8")
      (libsource (lib "eagle-import") (part "1,6/0,8"))
    )
    (comp (ref "PAD657")
      (value "1,6/0,8")
      (footprint "eagle-import:1,6_0,8")
      (libsource (lib "eagle-import") (part "1,6/0,8"))
    )
    (comp (ref "PAD658")
      (value "1,6/0,8")
      (footprint "eagle-import:1,6_0,8")
      (libsource (lib "eagle-import") (part "1,6/0,8"))
    )
    (comp (ref "PAD659")
      (value "1,6/0,8")
      (footprint "eagle-import:1,6_0,8")
      (libsource (lib "eagle-import") (part "1,6/0,8"))
    )
    (comp (ref "PAD660")
      (value "1,6/0,8")
      (footprint "eagle-import:1,6_0,8")
      (libsource (lib "eagle-import") (part "1,6/0,8"))
    )
    (comp (ref "PAD661")
      (value "1,6/0,8")
      (footprint "eagle-import:1,6_0,8")
      (libsource (lib "eagle-import") (part "1,6/0,8"))
    )
    (comp (ref "PAD662")
      (value "1,6/0,8")
      (footprint "eagle-import:1,6_0,8")
      (libsource (lib "eagle-import") (part "1,6/0,8"))
    )
    (comp (ref "PAD663")
      (value "1,6/0,8")
      (footprint "eagle-import:1,6_0,8")
      (libsource (lib "eagle-import") (part "1,6/0,8"))
    )
    (comp (ref "PAD664")
      (value "1,6/0,8")
      (footprint "eagle-import:1,6_0,8")
      (libsource (lib "eagle-import") (part "1,6/0,8"))
    )
    (comp (ref "PAD665")
      (value "1,6/0,8")
      (footprint "eagle-import:1,6_0,8")
      (libsource (lib "eagle-import") (part "1,6/0,8"))
    )
    (comp (ref "PAD666")
      (value "1,6/0,8")
      (footprint "eagle-import:1,6_0,8")
      (libsource (lib "eagle-import") (part "1,6/0,8"))
    )
    (comp (ref "PAD667")
      (value "1,6/0,8")
      (footprint "eagle-import:1,6_0,8")
      (libsource (lib "eagle-import") (part "1,6/0,8"))
    )
    (comp (ref "PAD668")
      (value "1,6/0,8")
      (footprint "eagle-import:1,6_0,8")
      (libsource (lib "eagle-import") (part "1,6/0,8"))
    )
    (comp (ref "PAD669")
      (value "1,6/0,8")
      (footprint "eagle-import:1,6_0,8")
      (libsource (lib "eagle-import") (part "1,6/0,8"))
    )
    (comp (ref "PAD670")
      (value "1,6/0,8")
      (footprint "eagle-import:1,6_0,8")
      (libsource (lib "eagle-import") (part "1,6/0,8"))
    )
    (comp (ref "PAD671")
      (value "1,6/0,8")
      (footprint "eagle-import:1,6_0,8")
      (libsource (lib "eagle-import") (part "1,6/0,8"))
    )
    (comp (ref "PAD672")
      (value "1,6/0,8")
      (footprint "eagle-import:1,6_0,8")
      (libsource (lib "eagle-import") (part "1,6/0,8"))
    )
    (comp (ref "PAD673")
      (value "1,6/0,8")
      (footprint "eagle-import:1,6_0,8")
      (libsource (lib "eagle-import") (part "1,6/0,8"))
    )
    (comp (ref "PAD674")
      (value "1,6/0,8")
      (footprint "eagle-import:1,6_0,8")
      (libsource (lib "eagle-import") (part "1,6/0,8"))
    )
    (comp (ref "PAD675")
      (value "1,6/0,8")
      (footprint "eagle-import:1,6_0,8")
      (libsource (lib "eagle-import") (part "1,6/0,8"))
    )
    (comp (ref "PAD676")
      (value "1,6/0,8")
      (footprint "eagle-import:1,6_0,8")
      (libsource (lib "eagle-import") (part "1,6/0,8"))
    )
    (comp (ref "PAD679")
      (value "1,6/0,8")
      (footprint "eagle-import:1,6_0,8")
      (libsource (lib "eagle-import") (part "1,6/0,8"))
    )
    (comp (ref "PAD680")
      (value "1,6/0,8")
      (footprint "eagle-import:1,6_0,8")
      (libsource (lib "eagle-import") (part "1,6/0,8"))
    )
    (comp (ref "PAD681")
      (value "1,6/0,8")
      (footprint "eagle-import:1,6_0,8")
      (libsource (lib "eagle-import") (part "1,6/0,8"))
    )
    (comp (ref "PAD682")
      (value "1,6/0,8")
      (footprint "eagle-import:1,6_0,8")
      (libsource (lib "eagle-import") (part "1,6/0,8"))
    )
    (comp (ref "PAD683")
      (value "1,6/0,8")
      (footprint "eagle-import:1,6_0,8")
      (libsource (lib "eagle-import") (part "1,6/0,8"))
    )
    (comp (ref "PAD686")
      (value "1,6/0,8")
      (footprint "eagle-import:1,6_0,8")
      (libsource (lib "eagle-import") (part "1,6/0,8"))
    )
    (comp (ref "PAD687")
      (value "1,6/0,8")
      (footprint "eagle-import:1,6_0,8")
      (libsource (lib "eagle-import") (part "1,6/0,8"))
    )
    (comp (ref "PAD688")
      (value "1,6/0,8")
      (footprint "eagle-import:1,6_0,8")
      (libsource (lib "eagle-import") (part "1,6/0,8"))
    )
    (comp (ref "PAD689")
      (value "1,6/0,8")
      (footprint "eagle-import:1,6_0,8")
      (libsource (lib "eagle-import") (part "1,6/0,8"))
    )
    (comp (ref "PAD690")
      (value "1,6/0,8")
      (footprint "eagle-import:1,6_0,8")
      (libsource (lib "eagle-import") (part "1,6/0,8"))
    )
    (comp (ref "PAD693")
      (value "1,6/0,8")
      (footprint "eagle-import:1,6_0,8")
      (libsource (lib "eagle-import") (part "1,6/0,8"))
    )
    (comp (ref "PAD694")
      (value "1,6/0,8")
      (footprint "eagle-import:1,6_0,8")
      (libsource (lib "eagle-import") (part "1,6/0,8"))
    )
    (comp (ref "PAD695")
      (value "1,6/0,8")
      (footprint "eagle-import:1,6_0,8")
      (libsource (lib "eagle-import") (part "1,6/0,8"))
    )
    (comp (ref "PAD696")
      (value "1,6/0,8")
      (footprint "eagle-import:1,6_0,8")
      (libsource (lib "eagle-import") (part "1,6/0,8"))
    )
    (comp (ref "PAD697")
      (value "1,6/0,8")
      (footprint "eagle-import:1,6_0,8")
      (libsource (lib "eagle-import") (part "1,6/0,8"))
    )
    (comp (ref "PAD700")
      (value "1,6/0,8")
      (footprint "eagle-import:1,6_0,8")
      (libsource (lib "eagle-import") (part "1,6/0,8"))
    )
    (comp (ref "PAD701")
      (value "1,6/0,8")
      (footprint "eagle-import:1,6_0,8")
      (libsource (lib "eagle-import") (part "1,6/0,8"))
    )
    (comp (ref "PAD702")
      (value "1,6/0,8")
      (footprint "eagle-import:1,6_0,8")
      (libsource (lib "eagle-import") (part "1,6/0,8"))
    )
    (comp (ref "PAD703")
      (value "1,6/0,8")
      (footprint "eagle-import:1,6_0,8")
      (libsource (lib "eagle-import") (part "1,6/0,8"))
    )
    (comp (ref "PAD704")
      (value "1,6/0,8")
      (footprint "eagle-import:1,6_0,8")
      (libsource (lib "eagle-import") (part "1,6/0,8"))
    )
    (comp (ref "PAD707")
      (value "1,6/0,8")
      (footprint "eagle-import:1,6_0,8")
      (libsource (lib "eagle-import") (part "1,6/0,8"))
    )
    (comp (ref "PAD708")
      (value "1,6/0,8")
      (footprint "eagle-import:1,6_0,8")
      (libsource (lib "eagle-import") (part "1,6/0,8"))
    )
    (comp (ref "PAD709")
      (value "1,6/0,8")
      (footprint "eagle-import:1,6_0,8")
      (libsource (lib "eagle-import") (part "1,6/0,8"))
    )
    (comp (ref "PAD710")
      (value "1,6/0,8")
      (footprint "eagle-import:1,6_0,8")
      (libsource (lib "eagle-import") (part "1,6/0,8"))
    )
    (comp (ref "PAD711")
      (value "1,6/0,8")
      (footprint "eagle-import:1,6_0,8")
      (libsource (lib "eagle-import") (part "1,6/0,8"))
    )
    (comp (ref "PAD714")
      (value "1,6/0,8")
      (footprint "eagle-import:1,6_0,8")
      (libsource (lib "eagle-import") (part "1,6/0,8"))
    )
    (comp (ref "PAD715")
      (value "1,6/0,8")
      (footprint "eagle-import:1,6_0,8")
      (libsource (lib "eagle-import") (part "1,6/0,8"))
    )
    (comp (ref "PAD716")
      (value "1,6/0,8")
      (footprint "eagle-import:1,6_0,8")
      (libsource (lib "eagle-import") (part "1,6/0,8"))
    )
    (comp (ref "PAD717")
      (value "1,6/0,8")
      (footprint "eagle-import:1,6_0,8")
      (libsource (lib "eagle-import") (part "1,6/0,8"))
    )
    (comp (ref "PAD718")
      (value "1,6/0,8")
      (footprint "eagle-import:1,6_0,8")
      (libsource (lib "eagle-import") (part "1,6/0,8"))
    )
    (comp (ref "PAD721")
      (value "1,6/0,8")
      (footprint "eagle-import:1,6_0,8")
      (libsource (lib "eagle-import") (part "1,6/0,8"))
    )
    (comp (ref "PAD722")
      (value "1,6/0,8")
      (footprint "eagle-import:1,6_0,8")
      (libsource (lib "eagle-import") (part "1,6/0,8"))
    )
    (comp (ref "PAD723")
      (value "1,6/0,8")
      (footprint "eagle-import:1,6_0,8")
      (libsource (lib "eagle-import") (part "1,6/0,8"))
    )
    (comp (ref "PAD724")
      (value "1,6/0,8")
      (footprint "eagle-import:1,6_0,8")
      (libsource (lib "eagle-import") (part "1,6/0,8"))
    )
    (comp (ref "PAD725")
      (value "1,6/0,8")
      (footprint "eagle-import:1,6_0,8")
      (libsource (lib "eagle-import") (part "1,6/0,8"))
    )
    (comp (ref "PAD728")
      (value "1,6/0,8")
      (footprint "eagle-import:1,6_0,8")
      (libsource (lib "eagle-import") (part "1,6/0,8"))
    )
    (comp (ref "PAD729")
      (value "1,6/0,8")
      (footprint "eagle-import:1,6_0,8")
      (libsource (lib "eagle-import") (part "1,6/0,8"))
    )
    (comp (ref "PAD730")
      (value "1,6/0,8")
      (footprint "eagle-import:1,6_0,8")
      (libsource (lib "eagle-import") (part "1,6/0,8"))
    )
    (comp (ref "PAD731")
      (value "1,6/0,8")
      (footprint "eagle-import:1,6_0,8")
      (libsource (lib "eagle-import") (part "1,6/0,8"))
    )
    (comp (ref "PAD732")
      (value "1,6/0,8")
      (footprint "eagle-import:1,6_0,8")
      (libsource (lib "eagle-import") (part "1,6/0,8"))
    )
    (comp (ref "PAD734")
      (value "1,6/0,8")
      (footprint "eagle-import:1,6_0,8")
      (libsource (lib "eagle-import") (part "1,6/0,8"))
    )
    (comp (ref "PAD742")
      (value "12")
      (footprint "eagle-import:1,6_0,8")
      (libsource (lib "eagle-import") (part "1,6/0,8"))
    )
    (comp (ref "PAD743")
      (value "1,6/0,8")
      (footprint "eagle-import:1,6_0,8")
      (libsource (lib "eagle-import") (part "1,6/0,8"))
    )
    (comp (ref "PAD744")
      (value "1,6/0,8")
      (footprint "eagle-import:1,6_0,8")
      (libsource (lib "eagle-import") (part "1,6/0,8"))
    )
    (comp (ref "PAD745")
      (value "1,6/0,8")
      (footprint "eagle-import:1,6_0,8")
      (libsource (lib "eagle-import") (part "1,6/0,8"))
    )
    (comp (ref "PAD746")
      (value "13")
      (footprint "eagle-import:1,6_0,8")
      (libsource (lib "eagle-import") (part "1,6/0,8"))
    )
    (comp (ref "PAD747")
      (value "1,6/0,8")
      (footprint "eagle-import:1,6_0,8")
      (libsource (lib "eagle-import") (part "1,6/0,8"))
    )
    (comp (ref "PAD748")
      (value "1,6/0,8")
      (footprint "eagle-import:1,6_0,8")
      (libsource (lib "eagle-import") (part "1,6/0,8"))
    )
    (comp (ref "PAD749")
      (value "1,6/0,8")
      (footprint "eagle-import:1,6_0,8")
      (libsource (lib "eagle-import") (part "1,6/0,8"))
    )
    (comp (ref "PAD751")
      (value "3,17/1,3")
      (footprint "eagle-import:3,17_1,3")
      (libsource (lib "eagle-import") (part "3,17/1,3"))
    )
    (comp (ref "PAD752")
      (value "3,17/1,3")
      (footprint "eagle-import:3,17_1,3")
      (libsource (lib "eagle-import") (part "3,17/1,3"))
    )
    (comp (ref "PAD753")
      (value "3,17/1,3")
      (footprint "eagle-import:3,17_1,3")
      (libsource (lib "eagle-import") (part "3,17/1,3"))
    )
    (comp (ref "PAD754")
      (value "3,17/1,3")
      (footprint "eagle-import:3,17_1,3")
      (libsource (lib "eagle-import") (part "3,17/1,3"))
    )
    (comp (ref "PAD755")
      (value "3,17/1,3")
      (footprint "eagle-import:3,17_1,3")
      (libsource (lib "eagle-import") (part "3,17/1,3"))
    )
    (comp (ref "PAD756")
      (value "3,17/1,3")
      (footprint "eagle-import:3,17_1,3")
      (libsource (lib "eagle-import") (part "3,17/1,3"))
    )
    (comp (ref "PAD757")
      (value "1,6/0,8")
      (footprint "eagle-import:1,6_0,8")
      (libsource (lib "eagle-import") (part "1,6/0,8"))
    )
    (comp (ref "PAD758")
      (value "CS")
      (footprint "eagle-import:1,6_0,8")
      (libsource (lib "eagle-import") (part "1,6/0,8"))
    )
    (comp (ref "PAD759")
      (value "1,6/0,8")
      (footprint "eagle-import:1,6_0,8")
      (libsource (lib "eagle-import") (part "1,6/0,8"))
    )
    (comp (ref "PAD760")
      (value "1,6/0,8")
      (footprint "eagle-import:1,6_0,8")
      (libsource (lib "eagle-import") (part "1,6/0,8"))
    )
    (comp (ref "PAD761")
      (value "1,6/0,8")
      (footprint "eagle-import:1,6_0,8")
      (libsource (lib "eagle-import") (part "1,6/0,8"))
    )
    (comp (ref "PAD762")
      (value "1,6/0,8")
      (footprint "eagle-import:1,6_0,8")
      (libsource (lib "eagle-import") (part "1,6/0,8"))
    )
    (comp (ref "PAD763")
      (value "1,6/0,8")
      (footprint "eagle-import:1,6_0,8")
      (libsource (lib "eagle-import") (part "1,6/0,8"))
    )
    (comp (ref "PAD764")
      (value "1,6/0,8")
      (footprint "eagle-import:1,6_0,8")
      (libsource (lib "eagle-import") (part "1,6/0,8"))
    )
    (comp (ref "PAD765")
      (value "SI")
      (footprint "eagle-import:1,6_0,8")
      (libsource (lib "eagle-import") (part "1,6/0,8"))
    )
    (comp (ref "PAD766")
      (value "1,6/0,8")
      (footprint "eagle-import:1,6_0,8")
      (libsource (lib "eagle-import") (part "1,6/0,8"))
    )
    (comp (ref "PAD767")
      (value "1,6/0,8")
      (footprint "eagle-import:1,6_0,8")
      (libsource (lib "eagle-import") (part "1,6/0,8"))
    )
    (comp (ref "PAD768")
      (value "1,6/0,8")
      (footprint "eagle-import:1,6_0,8")
      (libsource (lib "eagle-import") (part "1,6/0,8"))
    )
    (comp (ref "PAD769")
      (value "10")
      (footprint "eagle-import:1,6_0,8")
      (libsource (lib "eagle-import") (part "1,6/0,8"))
    )
    (comp (ref "PAD770")
      (value "RS")
      (footprint "eagle-import:1,6_0,8")
      (libsource (lib "eagle-import") (part "1,6/0,8"))
    )
    (comp (ref "PAD771")
      (value "1,6/0,8")
      (footprint "eagle-import:1,6_0,8")
      (libsource (lib "eagle-import") (part "1,6/0,8"))
    )
    (comp (ref "PAD772")
      (value "1,6/0,8")
      (footprint "eagle-import:1,6_0,8")
      (libsource (lib "eagle-import") (part "1,6/0,8"))
    )
    (comp (ref "PAD773")
      (value "1,6/0,8")
      (footprint "eagle-import:1,6_0,8")
      (libsource (lib "eagle-import") (part "1,6/0,8"))
    )
    (comp (ref "PAD774")
      (value "SO")
      (footprint "eagle-import:1,6_0,8")
      (libsource (lib "eagle-import") (part "1,6/0,8"))
    )
    (comp (ref "PAD775")
      (value "1,6/0,8")
      (footprint "eagle-import:1,6_0,8")
      (libsource (lib "eagle-import") (part "1,6/0,8"))
    )
    (comp (ref "PAD776")
      (value "1,6/0,8")
      (footprint "eagle-import:1,6_0,8")
      (libsource (lib "eagle-import") (part "1,6/0,8"))
    )
    (comp (ref "PAD777")
      (value "1,6/0,8")
      (footprint "eagle-import:1,6_0,8")
      (libsource (lib "eagle-import") (part "1,6/0,8"))
    )
    (comp (ref "PAD778")
      (value "9")
      (footprint "eagle-import:1,6_0,8")
      (libsource (lib "eagle-import") (part "1,6/0,8"))
    )
    (comp (ref "PAD779")
      (value "1,6/0,8")
      (footprint "eagle-import:1,6_0,8")
      (libsource (lib "eagle-import") (part "1,6/0,8"))
    )
    (comp (ref "PAD780")
      (value "1,6/0,8")
      (footprint "eagle-import:1,6_0,8")
      (libsource (lib "eagle-import") (part "1,6/0,8"))
    )
    (comp (ref "PAD781")
      (value "1,6/0,8")
      (footprint "eagle-import:1,6_0,8")
      (libsource (lib "eagle-import") (part "1,6/0,8"))
    )
    (comp (ref "PAD783")
      (value "1,6/0,8")
      (footprint "eagle-import:1,6_0,8")
      (libsource (lib "eagle-import") (part "1,6/0,8"))
    )
    (comp (ref "PAD784")
      (value "1,6/0,8")
      (footprint "eagle-import:1,6_0,8")
      (libsource (lib "eagle-import") (part "1,6/0,8"))
    )
    (comp (ref "PAD785")
      (value "1,6/0,8")
      (footprint "eagle-import:1,6_0,8")
      (libsource (lib "eagle-import") (part "1,6/0,8"))
    )
    (comp (ref "PAD786")
      (value "1,6/0,8")
      (footprint "eagle-import:1,6_0,8")
      (libsource (lib "eagle-import") (part "1,6/0,8"))
    )
    (comp (ref "PAD787")
      (value "1,6/0,8")
      (footprint "eagle-import:1,6_0,8")
      (libsource (lib "eagle-import") (part "1,6/0,8"))
    )
    (comp (ref "PAD788")
      (value "1,6/0,8")
      (footprint "eagle-import:1,6_0,8")
      (libsource (lib "eagle-import") (part "1,6/0,8"))
    )
    (comp (ref "PAD789")
      (value "1,6/0,8")
      (footprint "eagle-import:1,6_0,8")
      (libsource (lib "eagle-import") (part "1,6/0,8"))
    )
    (comp (ref "PAD790")
      (value "1,6/0,8")
      (footprint "eagle-import:1,6_0,8")
      (libsource (lib "eagle-import") (part "1,6/0,8"))
    )
    (comp (ref "PAD792")
      (value "1,6/0,8")
      (footprint "eagle-import:1,6_0,8")
      (libsource (lib "eagle-import") (part "1,6/0,8"))
    )
    (comp (ref "PAD793")
      (value "1,6/0,8")
      (footprint "eagle-import:1,6_0,8")
      (libsource (lib "eagle-import") (part "1,6/0,8"))
    )
    (comp (ref "PAD794")
      (value "1,6/0,8")
      (footprint "eagle-import:1,6_0,8")
      (libsource (lib "eagle-import") (part "1,6/0,8"))
    )
    (comp (ref "RJ-3")
      (value "1,6/0,8")
      (footprint "eagle-import:1,6_0,8")
      (libsource (lib "eagle-import") (part "1,6/0,8"))
    )
    (comp (ref "RX")
      (value "1,6/0,8")
      (footprint "eagle-import:1,6_0,8")
      (libsource (lib "eagle-import") (part "1,6/0,8"))
    )
    (comp (ref "TX")
      (value "1,6/0,8")
      (footprint "eagle-import:1,6_0,8")
      (libsource (lib "eagle-import") (part "1,6/0,8"))
    )
    (comp (ref "X1")
      (value "ESP-12E")
      (footprint "eagle-import:ESP-12E")
      (libsource (lib "eagle-import") (part "ESP-12E"))
    )
    (comp (ref "X2")
      (value "USBMICRO_20329")
      (footprint "eagle-import:4UCONN_20329")
      (libsource (lib "eagle-import") (part "USBMICRO_20329"))
    )
    (comp (ref "X3")
      (value "RJ45")
      (footprint "eagle-import:RJ45-NO-SHIELD")
      (fields (field (name "MF") "TYCO ELECTRONICS") (field (name "MPN") "RJ45-8L-B"))
      (libsource (lib "eagle-import") (part "RJ45-8L-B"))
    )
  )
  (nets
    (net (code "1") (name "GND") (class "Default")
      (node (ref "DC") (pin "2") (pinfunction "GND_2") (pintype "passive"))
      (node (ref "J1") (pin "2") (pinfunction "2_2") (pintype "passive"))
      (node (ref "J1") (pin "3") (pinfunction "3_3") (pintype "passive"))
      (node (ref "MIC5502") (pin "2") (pinfunction "GND_2") (pintype "input"))
      (node (ref "PAD118") (pin "1") (pinfunction "P_1") (pintype "passive"))
      (node (ref "PAD12") (pin "1") (pinfunction "P_1") (pintype "passive"))
      (node (ref "PAD140") (pin "1") (pinfunction "P_1") (pintype "passive"))
      (node (ref "PAD141") (pin "1") (pinfunction "P_1") (pintype "passive"))
      (node (ref "PAD149") (pin "1") (pinfunction "P_1") (pintype "passive"))
      (node (ref "PAD17") (pin "1") (pinfunction "P_1") (pintype "passive"))
      (node (ref "PAD22") (pin "1") (pinfunction "P_1") (pintype "passive"))
      (node (ref "PAD23") (pin "1") (pinfunction "P_1") (pintype "passive"))
      (node (ref "PAD24") (pin "1") (pinfunction "P_1") (pintype "passive"))
      (node (ref "PAD249") (pin "1") (pinfunction "P_1") (pintype "passive"))
      (node (ref "PAD25") (pin "1") (pinfunction "P_1") (pintype "passive"))
      (node (ref "PAD255") (pin "1") (pinfunction "P_1") (pintype "passive"))
      (node (ref "PAD26") (pin "1") (pinfunction "P_1") (pintype "passive"))
      (node (ref "PAD27") (pin "1") (pinfunction "P_1") (pintype "passive"))
      (node (ref "PAD276") (pin "1") (pinfunction "P_1") (pintype "passive"))
      (node (ref "PAD277") (pin "1") (pinfunction "P_1") (pintype "passive"))
      (node (ref "PAD28") (pin "1") (pinfunction "P_1") (pintype "passive"))
      (node (ref "PAD285") (pin "1") (pinfunction "P_1") (pintype "passive"))
      (node (ref "PAD286") (pin "1") (pinfunction "P_1") (pintype "passive"))
      (node (ref "PAD29") (pin "1") (pinfunction "P_1") (pintype "passive"))
      (node (ref "PAD30") (pin "1") (pinfunction "P_1") (pintype "passive"))
      (node (ref "PAD31") (pin "1") (pinfunction "P_1") (pintype "passive"))
      (node (ref "PAD32") (pin "1") (pinfunction "P_1") (pintype "passive"))
      (node (ref "PAD326") (pin "1") (pinfunction "P_1") (pintype "passive"))
      (node (ref "PAD327") (pin "1") (pinfunction "P_1") (pintype "passive"))
      (node (ref "PAD328") (pin "1") (pinfunction "P_1") (pintype "passive"))
      (node (ref "PAD329") (pin "1") (pinfunction "P_1") (pintype "passive"))
      (node (ref "PAD33") (pin "1") (pinfunction "P_1") (pintype "passive"))
      (node (ref "PAD330") (pin "1") (pinfunction "P_1") (pintype "passive"))
      (node (ref "PAD331") (pin "1") (pinfunction "P_1") (pintype "passive"))
      (node (ref "PAD339") (pin "1") (pinfunction "P_1") (pintype "passive"))
      (node (ref "PAD36") (pin "1") (pinfunction "P_1") (pintype "passive"))
      (node (ref "PAD38") (pin "1") (pinfunction "P_1") (pintype "passive"))
      (node (ref "PAD4") (pin "1") (pinfunction "P_1") (pintype "passive"))
      (node (ref "PAD421") (pin "1") (pinfunction "P_1") (pintype "passive"))
      (node (ref "PAD422") (pin "1") (pinfunction "P_1") (pintype "passive"))
      (node (ref "PAD423") (pin "1") (pinfunction "P_1") (pintype "passive"))
      (node (ref "PAD424") (pin "1") (pinfunction "P_1") (pintype "passive"))
      (node (ref "PAD425") (pin "1") (pinfunction "P_1") (pintype "passive"))
      (node (ref "PAD426") (pin "1") (pinfunction "P_1") (pintype "passive"))
      (node (ref "PAD427") (pin "1") (pinfunction "P_1") (pintype "passive"))
      (node (ref "PAD428") (pin "1") (pinfunction "P_1") (pintype "passive"))
      (node (ref "PAD429") (pin "1") (pinfunction "P_1") (pintype "passive"))
      (node (ref "PAD430") (pin "1") (pinfunction "P_1") (pintype "passive"))
      (node (ref "PAD431") (pin "1") (pinfunction "P_1") (pintype "passive"))
      (node (ref "PAD432") (pin "1") (pinfunction "P_1") (pintype "passive"))
      (node (ref "PAD433") (pin "1") (pinfunction "P_1") (pintype "passive"))
      (node (ref "PAD434") (pin "1") (pinfunction "P_1") (pintype "passive"))
      (node (ref "PAD435") (pin "1") (pinfunction "P_1") (pintype "passive"))
      (node (ref "PAD436") (pin "1") (pinfunction "P_1") (pintype "passive"))
      (node (ref "PAD439") (pin "1") (pinfunction "P_1") (pintype "passive"))
      (node (ref "PAD440") (pin "1") (pinfunction "P_1") (pintype "passive"))
      (node (ref "PAD441") (pin "1") (pinfunction "P_1") (pintype "passive"))
      (node (ref "PAD447") (pin "1") (pinfunction "P_1") (pintype "passive"))
      (node (ref "PAD471") (pin "1") (pinfunction "P_1") (pintype "passive"))
      (node (ref "PAD472") (pin "1") (pinfunction "P_1") (pintype "passive"))
      (node (ref "PAD473") (pin "1") (pinfunction "P_1") (pintype "passive"))
      (node (ref "PAD474") (pin "1") (pinfunction "P_1") (pintype "passive"))
      (node (ref "PAD475") (pin "1") (pinfunction "P_1") (pintype "passive"))
      (node (ref "PAD476") (pin "1") (pinfunction "P_1") (pintype "passive"))
      (node (ref "PAD477") (pin "1") (pinfunction "P_1") (pintype "passive"))
      (node (ref "PAD478") (pin "1") (pinfunction "P_1") (pintype "passive"))
      (node (ref "PAD479") (pin "1") (pinfunction "P_1") (pintype "passive"))
      (node (ref "PAD525") (pin "1") (pinfunction "P_1") (pintype "passive"))
      (node (ref "PAD54") (pin "1") (pinfunction "P_1") (pintype "passive"))
      (node (ref "PAD619") (pin "1") (pinfunction "P_1") (pintype "passive"))
      (node (ref "PAD620") (pin "1") (pinfunction "P_1") (pintype "passive"))
      (node (ref "PAD621") (pin "1") (pinfunction "P_1") (pintype "passive"))
      (node (ref "PAD643") (pin "1") (pinfunction "P_1") (pintype "passive"))
      (node (ref "PAD734") (pin "1") (pinfunction "P_1") (pintype "passive"))
      (node (ref "PAD757") (pin "1") (pinfunction "P_1") (pintype "passive"))
      (node (ref "PAD783") (pin "1") (pinfunction "P_1") (pintype "passive"))
      (node (ref "PAD788") (pin "1") (pinfunction "P_1") (pintype "passive"))
      (node (ref "PAD789") (pin "1") (pinfunction "P_1") (pintype "passive"))
      (node (ref "PAD790") (pin "1") (pinfunction "P_1") (pintype "passive"))
      (node (ref "X1") (pin "9") (pinfunction "GND_9") (pintype "power_in"))
      (node (ref "X2") (pin "BASE@1") (pinfunction "GND_BASE@1") (pintype "power_in"))
      (node (ref "X2") (pin "BASE@2") (pinfunction "GND_BASE@2") (pintype "power_in"))
      (node (ref "X2") (pin "GND") (pinfunction "GND_GND") (pintype "power_in"))
      (node (ref "X2") (pin "SPRT@1") (pinfunction "GND_SPRT@1") (pintype "power_in"))
      (node (ref "X2") (pin "SPRT@2") (pinfunction "GND_SPRT@2") (pintype "power_in"))
      (node (ref "X2") (pin "SPRT@3") (pinfunction "GND_SPRT@3") (pintype "power_in"))
      (node (ref "X2") (pin "SPRT@4") (pinfunction "GND_SPRT@4") (pintype "power_in"))
    )
    (net (code "2") (name "Net-(1-P)") (class "Default")
      (node (ref "1") (pin "1") (pinfunction "P_1") (pintype "passive"))
      (node (ref "X3") (pin "8") (pinfunction "8_8") (pintype "passive"))
    )
    (net (code "3") (name "Net-(2-P)") (class "Default")
      (node (ref "2") (pin "1") (pinfunction "P_1") (pintype "passive"))
      (node (ref "X3") (pin "1") (pinfunction "1_1") (pintype "passive"))
    )
    (net (code "4") (name "Net-(4-P)") (class "Default")
      (node (ref "4") (pin "1") (pinfunction "P_1") (pintype "passive"))
      (node (ref "X3") (pin "3") (pinfunction "3_3") (pintype "passive"))
    )
    (net (code "5") (name "Net-(5-P)") (class "Default")
      (node (ref "5") (pin "1") (pinfunction "P_1") (pintype "passive"))
      (node (ref "X3") (pin "4") (pinfunction "4_4") (pintype "passive"))
    )
    (net (code "6") (name "Net-(6-P)") (class "Default")
      (node (ref "6") (pin "1") (pinfunction "P_1") (pintype "passive"))
      (node (ref "X3") (pin "5") (pinfunction "5_5") (pintype "passive"))
    )
    (net (code "7") (name "Net-(7-P)") (class "Default")
      (node (ref "7") (pin "1") (pinfunction "P_1") (pintype "passive"))
      (node (ref "X3") (pin "6") (pinfunction "6_6") (pintype "passive"))
    )
    (net (code "8") (name "Net-(8-P)") (class "Default")
      (node (ref "8") (pin "1") (pinfunction "P_1") (pintype "passive"))
      (node (ref "X3") (pin "7") (pinfunction "7_7") (pintype "passive"))
    )
    (net (code "9") (name "Net-(PAD1-P)") (class "Default")
      (node (ref "PAD1") (pin "1") (pinfunction "P_1") (pintype "passive"))
      (node (ref "PAD2") (pin "1") (pinfunction "P_1") (pintype "passive"))
      (node (ref "PAD3") (pin "1") (pinfunction "P_1") (pintype "passive"))
      (node (ref "PAD587") (pin "1") (pinfunction "P_1") (pintype "passive"))
    )
    (net (code "10") (name "Net-(PAD15-P)") (class "Default")
      (node (ref "PAD15") (pin "1") (pinfunction "P_1") (pintype "passive"))
      (node (ref "PAD244") (pin "1") (pinfunction "P_1") (pintype "passive"))
    )
    (net (code "11") (name "Net-(PAD34-P)") (class "Default")
      (node (ref "PAD34") (pin "1") (pinfunction "P_1") (pintype "passive"))
      (node (ref "PAD35") (pin "1") (pinfunction "P_1") (pintype "passive"))
      (node (ref "PAD37") (pin "1") (pinfunction "P_1") (pintype "passive"))
      (node (ref "PAD40") (pin "1") (pinfunction "P_1") (pintype "passive"))
    )
    (net (code "12") (name "Net-(PAD45-P)") (class "Default")
      (node (ref "PAD45") (pin "1") (pinfunction "P_1") (pintype "passive"))
      (node (ref "PAD46") (pin "1") (pinfunction "P_1") (pintype "passive"))
      (node (ref "PAD47") (pin "1") (pinfunction "P_1") (pintype "passive"))
    )
    (net (code "13") (name "Net-(PAD48-P)") (class "Default")
      (node (ref "PAD48") (pin "1") (pinfunction "P_1") (pintype "passive"))
      (node (ref "PAD52") (pin "1") (pinfunction "P_1") (pintype "passive"))
      (node (ref "PAD53") (pin "1") (pinfunction "P_1") (pintype "passive"))
      (node (ref "PAD55") (pin "1") (pinfunction "P_1") (pintype "passive"))
      (node (ref "PAD62") (pin "1") (pinfunction "P_1") (pintype "passive"))
    )
    (net (code "14") (name "Net-(PAD59-P)") (class "Default")
      (node (ref "PAD59") (pin "1") (pinfunction "P_1") (pintype "passive"))
      (node (ref "PAD60") (pin "1") (pinfunction "P_1") (pintype "passive"))
      (node (ref "PAD61") (pin "1") (pinfunction "P_1") (pintype "passive"))
    )
    (net (code "15") (name "Net-(PAD63-P)") (class "Default")
      (node (ref "PAD63") (pin "1") (pinfunction "P_1") (pintype "passive"))
      (node (ref "PAD64") (pin "1") (pinfunction "P_1") (pintype "passive"))
      (node (ref "PAD65") (pin "1") (pinfunction "P_1") (pintype "passive"))
    )
    (net (code "16") (name "Net-(PAD66-P)") (class "Default")
      (node (ref "PAD66") (pin "1") (pinfunction "P_1") (pintype "passive"))
      (node (ref "PAD67") (pin "1") (pinfunction "P_1") (pintype "passive"))
      (node (ref "PAD68") (pin "1") (pinfunction "P_1") (pintype "passive"))
    )
    (net (code "17") (name "Net-(PAD70-P)") (class "Default")
      (node (ref "PAD70") (pin "1") (pinfunction "P_1") (pintype "passive"))
      (node (ref "PAD71") (pin "1") (pinfunction "P_1") (pintype "passive"))
      (node (ref "PAD72") (pin "1") (pinfunction "P_1") (pintype "passive"))
    )
    (net (code "18") (name "Net-(PAD73-P)") (class "Default")
      (node (ref "PAD73") (pin "1") (pinfunction "P_1") (pintype "passive"))
      (node (ref "PAD74") (pin "1") (pinfunction "P_1") (pintype "passive"))
      (node (ref "PAD75") (pin "1") (pinfunction "P_1") (pintype "passive"))
    )
    (net (code "19") (name "Net-(PAD77-P)") (class "Default")
      (node (ref "PAD77") (pin "1") (pinfunction "P_1") (pintype "passive"))
      (node (ref "PAD78") (pin "1") (pinfunction "P_1") (pintype "passive"))
      (node (ref "PAD86") (pin "1") (pinfunction "P_1") (pintype "passive"))
    )
    (net (code "20") (name "Net-(PAD79-P)") (class "Default")
      (node (ref "PAD79") (pin "1") (pinfunction "P_1") (pintype "passive"))
      (node (ref "PAD80") (pin "1") (pinfunction "P_1") (pintype "passive"))
      (node (ref "PAD81") (pin "1") (pinfunction "P_1") (pintype "passive"))
    )
    (net (code "21") (name "Net-(PAD83-P)") (class "Default")
      (node (ref "PAD83") (pin "1") (pinfunction "P_1") (pintype "passive"))
      (node (ref "PAD84") (pin "1") (pinfunction "P_1") (pintype "passive"))
      (node (ref "PAD85") (pin "1") (pinfunction "P_1") (pintype "passive"))
    )
    (net (code "22") (name "Net-(PAD88-P)") (class "Default")
      (node (ref "PAD88") (pin "1") (pinfunction "P_1") (pintype "passive"))
      (node (ref "PAD89") (pin "1") (pinfunction "P_1") (pintype "passive"))
      (node (ref "PAD90") (pin "1") (pinfunction "P_1") (pintype "passive"))
    )
    (net (code "23") (name "Net-(PAD92-P)") (class "Default")
      (node (ref "PAD92") (pin "1") (pinfunction "P_1") (pintype "passive"))
      (node (ref "PAD93") (pin "1") (pinfunction "P_1") (pintype "passive"))
      (node (ref "PAD94") (pin "1") (pinfunction "P_1") (pintype "passive"))
    )
    (net (code "24") (name "Net-(PAD97-P)") (class "Default")
      (node (ref "PAD97") (pin "1") (pinfunction "P_1") (pintype "passive"))
      (node (ref "PAD98") (pin "1") (pinfunction "P_1") (pintype "passive"))
      (node (ref "PAD99") (pin "1") (pinfunction "P_1") (pintype "passive"))
    )
    (net (code "25") (name "Net-(PAD100-P)") (class "Default")
      (node (ref "PAD100") (pin "1") (pinfunction "P_1") (pintype "passive"))
      (node (ref "PAD69") (pin "1") (pinfunction "P_1") (pintype "passive"))
      (node (ref "PAD76") (pin "1") (pinfunction "P_1") (pintype "passive"))
      (node (ref "PAD82") (pin "1") (pinfunction "P_1") (pintype "passive"))
      (node (ref "PAD91") (pin "1") (pinfunction "P_1") (pintype "passive"))
    )
    (net (code "26") (name "Net-(PAD101-P)") (class "Default")
      (node (ref "PAD101") (pin "1") (pinfunction "P_1") (pintype "passive"))
      (node (ref "PAD102") (pin "1") (pinfunction "P_1") (pintype "passive"))
      (node (ref "PAD103") (pin "1") (pinfunction "P_1") (pintype "passive"))
    )
    (net (code "27") (name "Net-(PAD106-P)") (class "Default")
      (node (ref "PAD106") (pin "1") (pinfunction "P_1") (pintype "passive"))
      (node (ref "PAD107") (pin "1") (pinfunction "P_1") (pintype "passive"))
      (node (ref "PAD108") (pin "1") (pinfunction "P_1") (pintype "passive"))
    )
    (net (code "28") (name "Net-(PAD110-P)") (class "Default")
      (node (ref "PAD110") (pin "1") (pinfunction "P_1") (pintype "passive"))
      (node (ref "PAD111") (pin "1") (pinfunction "P_1") (pintype "passive"))
      (node (ref "PAD112") (pin "1") (pinfunction "P_1") (pintype "passive"))
    )
    (net (code "29") (name "Net-(PAD115-P)") (class "Default")
      (node (ref "PAD115") (pin "1") (pinfunction "P_1") (pintype "passive"))
      (node (ref "PAD116") (pin "1") (pinfunction "P_1") (pintype "passive"))
      (node (ref "PAD117") (pin "1") (pinfunction "P_1") (pintype "passive"))
    )
    (net (code "30") (name "Net-(PAD119-P)") (class "Default")
      (node (ref "PAD119") (pin "1") (pinfunction "P_1") (pintype "passive"))
      (node (ref "PAD120") (pin "1") (pinfunction "P_1") (pintype "passive"))
      (node (ref "PAD121") (pin "1") (pinfunction "P_1") (pintype "passive"))
    )
    (net (code "31") (name "Net-(PAD122-P)") (class "Default")
      (node (ref "PAD122") (pin "1") (pinfunction "P_1") (pintype "passive"))
      (node (ref "PAD123") (pin "1") (pinfunction "P_1") (pintype "passive"))
      (node (ref "PAD131") (pin "1") (pinfunction "P_1") (pintype "passive"))
      (node (ref "PAD132") (pin "1") (pinfunction "P_1") (pintype "passive"))
    )
    (net (code "32") (name "Net-(PAD124-P)") (class "Default")
      (node (ref "PAD124") (pin "1") (pinfunction "P_1") (pintype "passive"))
      (node (ref "PAD125") (pin "1") (pinfunction "P_1") (pintype "passive"))
      (node (ref "PAD126") (pin "1") (pinfunction "P_1") (pintype "passive"))
    )
    (net (code "33") (name "Net-(PAD128-P)") (class "Default")
      (node (ref "PAD128") (pin "1") (pinfunction "P_1") (pintype "passive"))
      (node (ref "PAD129") (pin "1") (pinfunction "P_1") (pintype "passive"))
      (node (ref "PAD130") (pin "1") (pinfunction "P_1") (pintype "passive"))
    )
    (net (code "34") (name "Net-(PAD133-P)") (class "Default")
      (node (ref "PAD133") (pin "1") (pinfunction "P_1") (pintype "passive"))
      (node (ref "PAD134") (pin "1") (pinfunction "P_1") (pintype "passive"))
      (node (ref "PAD135") (pin "1") (pinfunction "P_1") (pintype "passive"))
    )
    (net (code "35") (name "Net-(PAD137-P)") (class "Default")
      (node (ref "PAD137") (pin "1") (pinfunction "P_1") (pintype "passive"))
      (node (ref "PAD138") (pin "1") (pinfunction "P_1") (pintype "passive"))
      (node (ref "PAD139") (pin "1") (pinfunction "P_1") (pintype "passive"))
    )
    (net (code "36") (name "Net-(PAD142-P)") (class "Default")
      (node (ref "PAD142") (pin "1") (pinfunction "P_1") (pintype "passive"))
      (node (ref "PAD143") (pin "1") (pinfunction "P_1") (pintype "passive"))
      (node (ref "PAD144") (pin "1") (pinfunction "P_1") (pintype "passive"))
    )
    (net (code "37") (name "Net-(PAD146-P)") (class "Default")
      (node (ref "PAD146") (pin "1") (pinfunction "P_1") (pintype "passive"))
      (node (ref "PAD147") (pin "1") (pinfunction "P_1") (pintype "passive"))
      (node (ref "PAD148") (pin "1") (pinfunction "P_1") (pintype "passive"))
    )
    (net (code "38") (name "Net-(PAD150-P)") (class "Default")
      (node (ref "PAD150") (pin "1") (pinfunction "P_1") (pintype "passive"))
      (node (ref "PAD158") (pin "1") (pinfunction "P_1") (pintype "passive"))
      (node (ref "PAD159") (pin "1") (pinfunction "P_1") (pintype "passive"))
      (node (ref "PAD588") (pin "1") (pinfunction "P_1") (pintype "passive"))
    )
    (net (code "39") (name "Net-(PAD151-P)") (class "Default")
      (node (ref "PAD151") (pin "1") (pinfunction "P_1") (pintype "passive"))
      (node (ref "PAD152") (pin "1") (pinfunction "P_1") (pintype "passive"))
      (node (ref "PAD153") (pin "1") (pinfunction "P_1") (pintype "passive"))
    )
    (net (code "40") (name "Net-(PAD155-P)") (class "Default")
      (node (ref "PAD155") (pin "1") (pinfunction "P_1") (pintype "passive"))
      (node (ref "PAD156") (pin "1") (pinfunction "P_1") (pintype "passive"))
      (node (ref "PAD157") (pin "1") (pinfunction "P_1") (pintype "passive"))
    )
    (net (code "41") (name "Net-(PAD160-P)") (class "Default")
      (node (ref "PAD160") (pin "1") (pinfunction "P_1") (pintype "passive"))
      (node (ref "PAD161") (pin "1") (pinfunction "P_1") (pintype "passive"))
      (node (ref "PAD162") (pin "1") (pinfunction "P_1") (pintype "passive"))
    )
    (net (code "42") (name "Net-(PAD164-P)") (class "Default")
      (node (ref "PAD164") (pin "1") (pinfunction "P_1") (pintype "passive"))
      (node (ref "PAD165") (pin "1") (pinfunction "P_1") (pintype "passive"))
      (node (ref "PAD166") (pin "1") (pinfunction "P_1") (pintype "passive"))
    )
    (net (code "43") (name "Net-(PAD167-P)") (class "Default")
      (node (ref "PAD167") (pin "1") (pinfunction "P_1") (pintype "passive"))
      (node (ref "PAD168") (pin "1") (pinfunction "P_1") (pintype "passive"))
      (node (ref "PAD176") (pin "1") (pinfunction "P_1") (pintype "passive"))
      (node (ref "PAD177") (pin "1") (pinfunction "P_1") (pintype "passive"))
    )
    (net (code "44") (name "Net-(PAD169-P)") (class "Default")
      (node (ref "PAD169") (pin "1") (pinfunction "P_1") (pintype "passive"))
      (node (ref "PAD170") (pin "1") (pinfunction "P_1") (pintype "passive"))
      (node (ref "PAD171") (pin "1") (pinfunction "P_1") (pintype "passive"))
    )
    (net (code "45") (name "Net-(PAD173-P)") (class "Default")
      (node (ref "PAD173") (pin "1") (pinfunction "P_1") (pintype "passive"))
      (node (ref "PAD174") (pin "1") (pinfunction "P_1") (pintype "passive"))
      (node (ref "PAD175") (pin "1") (pinfunction "P_1") (pintype "passive"))
    )
    (net (code "46") (name "Net-(PAD178-P)") (class "Default")
      (node (ref "PAD178") (pin "1") (pinfunction "P_1") (pintype "passive"))
      (node (ref "PAD179") (pin "1") (pinfunction "P_1") (pintype "passive"))
      (node (ref "PAD180") (pin "1") (pinfunction "P_1") (pintype "passive"))
    )
    (net (code "47") (name "Net-(PAD182-P)") (class "Default")
      (node (ref "PAD182") (pin "1") (pinfunction "P_1") (pintype "passive"))
      (node (ref "PAD183") (pin "1") (pinfunction "P_1") (pintype "passive"))
      (node (ref "PAD184") (pin "1") (pinfunction "P_1") (pintype "passive"))
    )
    (net (code "48") (name "Net-(PAD185-P)") (class "Default")
      (node (ref "PAD185") (pin "1") (pinfunction "P_1") (pintype "passive"))
      (node (ref "PAD186") (pin "1") (pinfunction "P_1") (pintype "passive"))
      (node (ref "PAD194") (pin "1") (pinfunction "P_1") (pintype "passive"))
      (node (ref "PAD594") (pin "1") (pinfunction "P_1") (pintype "passive"))
    )
    (net (code "49") (name "Net-(PAD195-P)") (class "Default")
      (node (ref "PAD195") (pin "1") (pinfunction "P_1") (pintype "passive"))
      (node (ref "PAD203") (pin "1") (pinfunction "P_1") (pintype "passive"))
      (node (ref "PAD204") (pin "1") (pinfunction "P_1") (pintype "passive"))
      (node (ref "PAD212") (pin "1") (pinfunction "P_1") (pintype "passive"))
    )
    (net (code "50") (name "Net-(PAD196-P)") (class "Default")
      (node (ref "PAD196") (pin "1") (pinfunction "P_1") (pintype "passive"))
      (node (ref "PAD197") (pin "1") (pinfunction "P_1") (pintype "passive"))
      (node (ref "PAD198") (pin "1") (pinfunction "P_1") (pintype "passive"))
      (node (ref "PAD574") (pin "1") (pinfunction "P_1") (pintype "passive"))
    )
    (net (code "51") (name "Net-(PAD199-P)") (class "Default")
      (node (ref "PAD199") (pin "1") (pinfunction "P_1") (pintype "passive"))
      (node (ref "PAD200") (pin "1") (pinfunction "P_1") (pintype "passive"))
      (node (ref "PAD201") (pin "1") (pinfunction "P_1") (pintype "passive"))
      (node (ref "PAD202") (pin "1") (pinfunction "P_1") (pintype "passive"))
    )
    (net (code "52") (name "Net-(PAD205-P)") (class "Default")
      (node (ref "PAD205") (pin "1") (pinfunction "P_1") (pintype "passive"))
      (node (ref "PAD206") (pin "1") (pinfunction "P_1") (pintype "passive"))
      (node (ref "PAD207") (pin "1") (pinfunction "P_1") (pintype "passive"))
      (node (ref "PAD580") (pin "1") (pinfunction "P_1") (pintype "passive"))
    )
    (net (code "53") (name "Net-(PAD208-P)") (class "Default")
      (node (ref "PAD208") (pin "1") (pinfunction "P_1") (pintype "passive"))
      (node (ref "PAD209") (pin "1") (pinfunction "P_1") (pintype "passive"))
      (node (ref "PAD210") (pin "1") (pinfunction "P_1") (pintype "passive"))
      (node (ref "PAD211") (pin "1") (pinfunction "P_1") (pintype "passive"))
    )
    (net (code "54") (name "Net-(PAD213-P)") (class "Default")
      (node (ref "PAD213") (pin "1") (pinfunction "P_1") (pintype "passive"))
      (node (ref "PAD221") (pin "1") (pinfunction "P_1") (pintype "passive"))
      (node (ref "PAD222") (pin "1") (pinfunction "P_1") (pintype "passive"))
      (node (ref "PAD595") (pin "1") (pinfunction "P_1") (pintype "passive"))
    )
    (net (code "55") (name "Net-(PAD214-P)") (class "Default")
      (node (ref "PAD214") (pin "1") (pinfunction "P_1") (pintype "passive"))
      (node (ref "PAD215") (pin "1") (pinfunction "P_1") (pintype "passive"))
      (node (ref "PAD216") (pin "1") (pinfunction "P_1") (pintype "passive"))
      (node (ref "PAD581") (pin "1") (pinfunction "P_1") (pintype "passive"))
    )
    (net (code "56") (name "Net-(PAD217-P)") (class "Default")
      (node (ref "PAD217") (pin "1") (pinfunction "P_1") (pintype "passive"))
      (node (ref "PAD218") (pin "1") (pinfunction "P_1") (pintype "passive"))
      (node (ref "PAD219") (pin "1") (pinfunction "P_1") (pintype "passive"))
      (node (ref "PAD220") (pin "1") (pinfunction "P_1") (pintype "passive"))
    )
    (net (code "57") (name "Net-(PAD223-P)") (class "Default")
      (node (ref "PAD223") (pin "1") (pinfunction "P_1") (pintype "passive"))
      (node (ref "PAD224") (pin "1") (pinfunction "P_1") (pintype "passive"))
      (node (ref "PAD225") (pin "1") (pinfunction "P_1") (pintype "passive"))
      (node (ref "PAD226") (pin "1") (pinfunction "P_1") (pintype "passive"))
    )
    (net (code "58") (name "Net-(PAD227-P)") (class "Default")
      (node (ref "PAD227") (pin "1") (pinfunction "P_1") (pintype "passive"))
      (node (ref "PAD228") (pin "1") (pinfunction "P_1") (pintype "passive"))
      (node (ref "PAD229") (pin "1") (pinfunction "P_1") (pintype "passive"))
      (node (ref "PAD601") (pin "1") (pinfunction "P_1") (pintype "passive"))
    )
    (net (code "59") (name "Net-(PAD230-P)") (class "Default")
      (node (ref "PAD230") (pin "1") (pinfunction "P_1") (pintype "passive"))
      (node (ref "PAD231") (pin "1") (pinfunction "P_1") (pintype "passive"))
      (node (ref "PAD232") (pin "1") (pinfunction "P_1") (pintype "passive"))
      (node (ref "PAD233") (pin "1") (pinfunction "P_1") (pintype "passive"))
    )
    (net (code "60") (name "Net-(PAD234-P)") (class "Default")
      (node (ref "PAD234") (pin "1") (pinfunction "P_1") (pintype "passive"))
      (node (ref "PAD235") (pin "1") (pinfunction "P_1") (pintype "passive"))
      (node (ref "PAD236") (pin "1") (pinfunction "P_1") (pintype "passive"))
      (node (ref "PAD602") (pin "1") (pinfunction "P_1") (pintype "passive"))
    )
    (net (code "61") (name "Net-(PAD237-P)") (class "Default")
      (node (ref "PAD237") (pin "1") (pinfunction "P_1") (pintype "passive"))
      (node (ref "PAD238") (pin "1") (pinfunction "P_1") (pintype "passive"))
      (node (ref "PAD239") (pin "1") (pinfunction "P_1") (pintype "passive"))
      (node (ref "PAD240") (pin "1") (pinfunction "P_1") (pintype "passive"))
    )
    (net (code "62") (name "Net-(PAD241-P)") (class "Default")
      (node (ref "PAD241") (pin "1") (pinfunction "P_1") (pintype "passive"))
      (node (ref "PAD42") (pin "1") (pinfunction "P_1") (pintype "passive"))
    )
    (net (code "63") (name "Net-(PAD242-P)") (class "Default")
      (node (ref "PAD242") (pin "1") (pinfunction "P_1") (pintype "passive"))
      (node (ref "PAD41") (pin "1") (pinfunction "P_1") (pintype "passive"))
    )
    (net (code "64") (name "Net-(PAD243-P)") (class "Default")
      (node (ref "PAD243") (pin "1") (pinfunction "P_1") (pintype "passive"))
      (node (ref "PAD39") (pin "1") (pinfunction "P_1") (pintype "passive"))
    )
    (net (code "65") (name "Net-(PAD250-P)") (class "Default")
      (node (ref "PAD250") (pin "1") (pinfunction "P_1") (pintype "passive"))
      (node (ref "PAD251") (pin "1") (pinfunction "P_1") (pintype "passive"))
      (node (ref "PAD252") (pin "1") (pinfunction "P_1") (pintype "passive"))
      (node (ref "PAD253") (pin "1") (pinfunction "P_1") (pintype "passive"))
      (node (ref "PAD254") (pin "1") (pinfunction "P_1") (pintype "passive"))
    )
    (net (code "66") (name "Net-(PAD340-P)") (class "Default")
      (node (ref "PAD340") (pin "1") (pinfunction "P_1") (pintype "passive"))
      (node (ref "PAD348") (pin "1") (pinfunction "P_1") (pintype "passive"))
      (node (ref "PAD349") (pin "1") (pinfunction "P_1") (pintype "passive"))
      (node (ref "PAD608") (pin "1") (pinfunction "P_1") (pintype "passive"))
    )
    (net (code "67") (name "Net-(PAD357-P)") (class "Default")
      (node (ref "PAD357") (pin "1") (pinfunction "P_1") (pintype "passive"))
      (node (ref "PAD358") (pin "1") (pinfunction "P_1") (pintype "passive"))
      (node (ref "PAD366") (pin "1") (pinfunction "P_1") (pintype "passive"))
      (node (ref "PAD367") (pin "1") (pinfunction "P_1") (pintype "passive"))
    )
    (net (code "68") (name "Net-(PAD375-P)") (class "Default")
      (node (ref "PAD375") (pin "1") (pinfunction "P_1") (pintype "passive"))
      (node (ref "PAD376") (pin "1") (pinfunction "P_1") (pintype "passive"))
      (node (ref "PAD384") (pin "1") (pinfunction "P_1") (pintype "passive"))
      (node (ref "PAD609") (pin "1") (pinfunction "P_1") (pintype "passive"))
    )
    (net (code "69") (name "Net-(PAD390-P)") (class "Default")
      (node (ref "PAD390") (pin "1") (pinfunction "P_1") (pintype "passive"))
      (node (ref "PAD395") (pin "1") (pinfunction "P_1") (pintype "passive"))
      (node (ref "PAD414") (pin "1") (pinfunction "P_1") (pintype "passive"))
      (node (ref "PAD415") (pin "1") (pinfunction "P_1") (pintype "passive"))
    )
    (net (code "70") (name "Net-(PAD398-P)") (class "Default")
      (node (ref "PAD398") (pin "1") (pinfunction "P_1") (pintype "passive"))
      (node (ref "PAD399") (pin "1") (pinfunction "P_1") (pintype "passive"))
      (node (ref "PAD400") (pin "1") (pinfunction "P_1") (pintype "passive"))
      (node (ref "PAD401") (pin "1") (pinfunction "P_1") (pintype "passive"))
      (node (ref "X1") (pin "14") (pinfunction "GPIO5_14") (pintype "bidirectional"))
    )
    (net (code "71") (name "Net-(PAD402-P)") (class "Default")
      (node (ref "PAD402") (pin "1") (pinfunction "P_1") (pintype "passive"))
      (node (ref "PAD403") (pin "1") (pinfunction "P_1") (pintype "passive"))
      (node (ref "PAD404") (pin "1") (pinfunction "P_1") (pintype "passive"))
      (node (ref "PAD405") (pin "1") (pinfunction "P_1") (pintype "passive"))
      (node (ref "X1") (pin "13") (pinfunction "GPIO4_13") (pintype "bidirectional"))
    )
    (net (code "72") (name "Net-(PAD406-P)") (class "Default")
      (node (ref "PAD406") (pin "1") (pinfunction "P_1") (pintype "passive"))
      (node (ref "PAD407") (pin "1") (pinfunction "P_1") (pintype "passive"))
      (node (ref "PAD408") (pin "1") (pinfunction "P_1") (pintype "passive"))
      (node (ref "PAD409") (pin "1") (pinfunction "P_1") (pintype "passive"))
      (node (ref "X1") (pin "12") (pinfunction "GPIO0_12") (pintype "bidirectional"))
    )
    (net (code "73") (name "Net-(PAD410-P)") (class "Default")
      (node (ref "PAD410") (pin "1") (pinfunction "P_1") (pintype "passive"))
      (node (ref "PAD411") (pin "1") (pinfunction "P_1") (pintype "passive"))
      (node (ref "PAD412") (pin "1") (pinfunction "P_1") (pintype "passive"))
      (node (ref "PAD413") (pin "1") (pinfunction "P_1") (pintype "passive"))
      (node (ref "X1") (pin "11") (pinfunction "GPIO2_11") (pintype "bidirectional"))
    )
    (net (code "74") (name "Net-(PAD416-P)") (class "Default")
      (node (ref "PAD416") (pin "1") (pinfunction "P_1") (pintype "passive"))
      (node (ref "PAD420") (pin "1") (pinfunction "P_1") (pintype "passive"))
      (node (ref "PAD437") (pin "1") (pinfunction "P_1") (pintype "passive"))
      (node (ref "PAD615") (pin "1") (pinfunction "P_1") (pintype "passive"))
    )
    (net (code "75") (name "Net-(PAD417-P)") (class "Default")
      (node (ref "PAD417") (pin "1") (pinfunction "P_1") (pintype "passive"))
      (node (ref "PAD418") (pin "1") (pinfunction "P_1") (pintype "passive"))
      (node (ref "PAD419") (pin "1") (pinfunction "P_1") (pintype "passive"))
      (node (ref "PAD622") (pin "1") (pinfunction "P_1") (pintype "passive"))
      (node (ref "X1") (pin "10") (pinfunction "GPIO15_10") (pintype "bidirectional"))
    )
    (net (code "76") (name "Net-(PAD438-P)") (class "Default")
      (node (ref "PAD438") (pin "1") (pinfunction "P_1") (pintype "passive"))
      (node (ref "PAD457") (pin "1") (pinfunction "P_1") (pintype "passive"))
      (node (ref "PAD458") (pin "1") (pinfunction "P_1") (pintype "passive"))
      (node (ref "PAD463") (pin "1") (pinfunction "P_1") (pintype "passive"))
    )
    (net (code "77") (name "Net-(PAD491-P)") (class "Default")
      (node (ref "PAD491") (pin "1") (pinfunction "P_1") (pintype "passive"))
      (node (ref "PAD492") (pin "1") (pinfunction "P_1") (pintype "passive"))
      (node (ref "PAD493") (pin "1") (pinfunction "P_1") (pintype "passive"))
      (node (ref "PAD494") (pin "1") (pinfunction "P_1") (pintype "passive"))
      (node (ref "PAD495") (pin "1") (pinfunction "P_1") (pintype "passive"))
    )
    (net (code "78") (name "Net-(PAD498-P)") (class "Default")
      (node (ref "PAD498") (pin "1") (pinfunction "P_1") (pintype "passive"))
      (node (ref "PAD499") (pin "1") (pinfunction "P_1") (pintype "passive"))
      (node (ref "PAD500") (pin "1") (pinfunction "P_1") (pintype "passive"))
      (node (ref "PAD501") (pin "1") (pinfunction "P_1") (pintype "passive"))
      (node (ref "PAD502") (pin "1") (pinfunction "P_1") (pintype "passive"))
    )
    (net (code "79") (name "Net-(PAD505-P)") (class "Default")
      (node (ref "PAD505") (pin "1") (pinfunction "P_1") (pintype "passive"))
      (node (ref "PAD506") (pin "1") (pinfunction "P_1") (pintype "passive"))
      (node (ref "PAD507") (pin "1") (pinfunction "P_1") (pintype "passive"))
      (node (ref "PAD508") (pin "1") (pinfunction "P_1") (pintype "passive"))
      (node (ref "PAD509") (pin "1") (pinfunction "P_1") (pintype "passive"))
    )
    (net (code "80") (name "Net-(PAD512-P)") (class "Default")
      (node (ref "PAD512") (pin "1") (pinfunction "P_1") (pintype "passive"))
      (node (ref "PAD513") (pin "1") (pinfunction "P_1") (pintype "passive"))
      (node (ref "PAD514") (pin "1") (pinfunction "P_1") (pintype "passive"))
      (node (ref "PAD515") (pin "1") (pinfunction "P_1") (pintype "passive"))
      (node (ref "PAD516") (pin "1") (pinfunction "P_1") (pintype "passive"))
    )
    (net (code "81") (name "Net-(PAD518-P)") (class "Default")
      (node (ref "PAD518") (pin "1") (pinfunction "P_1") (pintype "passive"))
      (node (ref "PAD524") (pin "1") (pinfunction "P_1") (pintype "passive"))
      (node (ref "PAD531") (pin "1") (pinfunction "P_1") (pintype "passive"))
      (node (ref "PAD532") (pin "1") (pinfunction "P_1") (pintype "passive"))
      (node (ref "PAD538") (pin "1") (pinfunction "P_1") (pintype "passive"))
    )
    (net (code "82") (name "Net-(PAD519-P)") (class "Default")
      (node (ref "PAD519") (pin "1") (pinfunction "P_1") (pintype "passive"))
      (node (ref "PAD520") (pin "1") (pinfunction "P_1") (pintype "passive"))
      (node (ref "PAD521") (pin "1") (pinfunction "P_1") (pintype "passive"))
      (node (ref "PAD522") (pin "1") (pinfunction "P_1") (pintype "passive"))
      (node (ref "PAD523") (pin "1") (pinfunction "P_1") (pintype "passive"))
    )
    (net (code "83") (name "Net-(PAD526-P)") (class "Default")
      (node (ref "PAD526") (pin "1") (pinfunction "P_1") (pintype "passive"))
      (node (ref "PAD527") (pin "1") (pinfunction "P_1") (pintype "passive"))
      (node (ref "PAD528") (pin "1") (pinfunction "P_1") (pintype "passive"))
      (node (ref "PAD529") (pin "1") (pinfunction "P_1") (pintype "passive"))
      (node (ref "PAD530") (pin "1") (pinfunction "P_1") (pintype "passive"))
    )
    (net (code "84") (name "Net-(PAD533-P)") (class "Default")
      (node (ref "PAD533") (pin "1") (pinfunction "P_1") (pintype "passive"))
      (node (ref "PAD534") (pin "1") (pinfunction "P_1") (pintype "passive"))
      (node (ref "PAD535") (pin "1") (pinfunction "P_1") (pintype "passive"))
      (node (ref "PAD536") (pin "1") (pinfunction "P_1") (pintype "passive"))
      (node (ref "PAD537") (pin "1") (pinfunction "P_1") (pintype "passive"))
    )
    (net (code "85") (name "Net-(PAD540-P)") (class "Default")
      (node (ref "PAD540") (pin "1") (pinfunction "P_1") (pintype "passive"))
      (node (ref "PAD541") (pin "1") (pinfunction "P_1") (pintype "passive"))
      (node (ref "PAD542") (pin "1") (pinfunction "P_1") (pintype "passive"))
      (node (ref "PAD543") (pin "1") (pinfunction "P_1") (pintype "passive"))
      (node (ref "PAD544") (pin "1") (pinfunction "P_1") (pintype "passive"))
    )
    (net (code "86") (name "Net-(PAD547-P)") (class "Default")
      (node (ref "PAD547") (pin "1") (pinfunction "P_1") (pintype "passive"))
      (node (ref "PAD548") (pin "1") (pinfunction "P_1") (pintype "passive"))
      (node (ref "PAD549") (pin "1") (pinfunction "P_1") (pintype "passive"))
      (node (ref "PAD550") (pin "1") (pinfunction "P_1") (pintype "passive"))
      (node (ref "PAD551") (pin "1") (pinfunction "P_1") (pintype "passive"))
    )
    (net (code "87") (name "Net-(PAD554-P)") (class "Default")
      (node (ref "PAD554") (pin "1") (pinfunction "P_1") (pintype "passive"))
      (node (ref "PAD555") (pin "1") (pinfunction "P_1") (pintype "passive"))
      (node (ref "PAD556") (pin "1") (pinfunction "P_1") (pintype "passive"))
      (node (ref "PAD557") (pin "1") (pinfunction "P_1") (pintype "passive"))
      (node (ref "PAD558") (pin "1") (pinfunction "P_1") (pintype "passive"))
    )
    (net (code "88") (name "Net-(PAD560-P)") (class "Default")
      (node (ref "PAD560") (pin "1") (pinfunction "P_1") (pintype "passive"))
      (node (ref "PAD566") (pin "1") (pinfunction "P_1") (pintype "passive"))
      (node (ref "PAD567") (pin "1") (pinfunction "P_1") (pintype "passive"))
      (node (ref "PAD573") (pin "1") (pinfunction "P_1") (pintype "passive"))
    )
    (net (code "89") (name "Net-(PAD561-P)") (class "Default")
      (node (ref "PAD561") (pin "1") (pinfunction "P_1") (pintype "passive"))
      (node (ref "PAD562") (pin "1") (pinfunction "P_1") (pintype "passive"))
      (node (ref "PAD563") (pin "1") (pinfunction "P_1") (pintype "passive"))
      (node (ref "PAD564") (pin "1") (pinfunction "P_1") (pintype "passive"))
      (node (ref "PAD565") (pin "1") (pinfunction "P_1") (pintype "passive"))
    )
    (net (code "90") (name "Net-(PAD568-P)") (class "Default")
      (node (ref "PAD568") (pin "1") (pinfunction "P_1") (pintype "passive"))
      (node (ref "PAD569") (pin "1") (pinfunction "P_1") (pintype "passive"))
      (node (ref "PAD570") (pin "1") (pinfunction "P_1") (pintype "passive"))
      (node (ref "PAD571") (pin "1") (pinfunction "P_1") (pintype "passive"))
      (node (ref "PAD572") (pin "1") (pinfunction "P_1") (pintype "passive"))
    )
    (net (code "91") (name "Net-(PAD575-P)") (class "Default")
      (node (ref "PAD575") (pin "1") (pinfunction "P_1") (pintype "passive"))
      (node (ref "PAD576") (pin "1") (pinfunction "P_1") (pintype "passive"))
      (node (ref "PAD577") (pin "1") (pinfunction "P_1") (pintype "passive"))
      (node (ref "PAD578") (pin "1") (pinfunction "P_1") (pintype "passive"))
      (node (ref "PAD579") (pin "1") (pinfunction "P_1") (pintype "passive"))
    )
    (net (code "92") (name "Net-(PAD582-P)") (class "Default")
      (node (ref "PAD582") (pin "1") (pinfunction "P_1") (pintype "passive"))
      (node (ref "PAD583") (pin "1") (pinfunction "P_1") (pintype "passive"))
      (node (ref "PAD584") (pin "1") (pinfunction "P_1") (pintype "passive"))
      (node (ref "PAD585") (pin "1") (pinfunction "P_1") (pintype "passive"))
      (node (ref "PAD586") (pin "1") (pinfunction "P_1") (pintype "passive"))
    )
    (net (code "93") (name "Net-(PAD589-P)") (class "Default")
      (node (ref "PAD589") (pin "1") (pinfunction "P_1") (pintype "passive"))
      (node (ref "PAD590") (pin "1") (pinfunction "P_1") (pintype "passive"))
      (node (ref "PAD591") (pin "1") (pinfunction "P_1") (pintype "passive"))
      (node (ref "PAD592") (pin "1") (pinfunction "P_1") (pintype "passive"))
      (node (ref "PAD593") (pin "1") (pinfunction "P_1") (pintype "passive"))
    )
    (net (code "94") (name "Net-(PAD596-P)") (class "Default")
      (node (ref "PAD596") (pin "1") (pinfunction "P_1") (pintype "passive"))
      (node (ref "PAD597") (pin "1") (pinfunction "P_1") (pintype "passive"))
      (node (ref "PAD598") (pin "1") (pinfunction "P_1") (pintype "passive"))
      (node (ref "PAD599") (pin "1") (pinfunction "P_1") (pintype "passive"))
      (node (ref "PAD600") (pin "1") (pinfunction "P_1") (pintype "passive"))
    )
    (net (code "95") (name "Net-(PAD603-P)") (class "Default")
      (node (ref "PAD603") (pin "1") (pinfunction "P_1") (pintype "passive"))
      (node (ref "PAD604") (pin "1") (pinfunction "P_1") (pintype "passive"))
      (node (ref "PAD605") (pin "1") (pinfunction "P_1") (pintype "passive"))
      (node (ref "PAD606") (pin "1") (pinfunction "P_1") (pintype "passive"))
      (node (ref "PAD607") (pin "1") (pinfunction "P_1") (pintype "passive"))
    )
    (net (code "96") (name "Net-(PAD610-P)") (class "Default")
      (node (ref "PAD610") (pin "1") (pinfunction "P_1") (pintype "passive"))
      (node (ref "PAD611") (pin "1") (pinfunction "P_1") (pintype "passive"))
      (node (ref "PAD612") (pin "1") (pinfunction "P_1") (pintype "passive"))
      (node (ref "PAD613") (pin "1") (pinfunction "P_1") (pintype "passive"))
      (node (ref "PAD614") (pin "1") (pinfunction "P_1") (pintype "passive"))
    )
    (net (code "97") (name "Net-(PAD623-P)") (class "Default")
      (node (ref "PAD623") (pin "1") (pinfunction "P_1") (pintype "passive"))
      (node (ref "PAD624") (pin "1") (pinfunction "P_1") (pintype "passive"))
      (node (ref "PAD625") (pin "1") (pinfunction "P_1") (pintype "passive"))
      (node (ref "PAD626") (pin "1") (pinfunction "P_1") (pintype "passive"))
    )
    (net (code "98") (name "Net-(PAD627-P)") (class "Default")
      (node (ref "PAD627") (pin "1") (pinfunction "P_1") (pintype "passive"))
      (node (ref "PAD628") (pin "1") (pinfunction "P_1") (pintype "passive"))
      (node (ref "PAD629") (pin "1") (pinfunction "P_1") (pintype "passive"))
      (node (ref "PAD630") (pin "1") (pinfunction "P_1") (pintype "passive"))
      (node (ref "X1") (pin "2") (pinfunction "ADC_2") (pintype "passive"))
    )
    (net (code "99") (name "Net-(PAD631-P)") (class "Default")
      (node (ref "PAD631") (pin "1") (pinfunction "P_1") (pintype "passive"))
      (node (ref "PAD632") (pin "1") (pinfunction "P_1") (pintype "passive"))
      (node (ref "PAD633") (pin "1") (pinfunction "P_1") (pintype "passive"))
      (node (ref "PAD634") (pin "1") (pinfunction "P_1") (pintype "passive"))
      (node (ref "X1") (pin "3") (pinfunction "CH_PD_3") (pintype "input"))
    )
    (net (code "100") (name "Net-(PAD635-P)") (class "Default")
      (node (ref "PAD635") (pin "1") (pinfunction "P_1") (pintype "passive"))
      (node (ref "PAD636") (pin "1") (pinfunction "P_1") (pintype "passive"))
      (node (ref "PAD637") (pin "1") (pinfunction "P_1") (pintype "passive"))
      (node (ref "PAD638") (pin "1") (pinfunction "P_1") (pintype "passive"))
      (node (ref "X1") (pin "4") (pinfunction "GPIO16_4") (pintype "bidirectional"))
    )
    (net (code "101") (name "Net-(PAD639-P)") (class "Default")
      (node (ref "PAD639") (pin "1") (pinfunction "P_1") (pintype "passive"))
      (node (ref "PAD640") (pin "1") (pinfunction "P_1") (pintype "passive"))
      (node (ref "PAD641") (pin "1") (pinfunction "P_1") (pintype "passive"))
      (node (ref "PAD642") (pin "1") (pinfunction "P_1") (pintype "passive"))
      (node (ref "X1") (pin "5") (pinfunction "GPIO14_5") (pintype "bidirectional"))
    )
    (net (code "102") (name "Net-(PAD644-P)") (class "Default")
      (node (ref "PAD644") (pin "1") (pinfunction "P_1") (pintype "passive"))
      (node (ref "PAD645") (pin "1") (pinfunction "P_1") (pintype "passive"))
      (node (ref "PAD646") (pin "1") (pinfunction "P_1") (pintype "passive"))
      (node (ref "PAD647") (pin "1") (pinfunction "P_1") (pintype "passive"))
      (node (ref "PAD648") (pin "1") (pinfunction "P_1") (pintype "passive"))
    )
    (net (code "103") (name "Net-(PAD651-P)") (class "Default")
      (node (ref "PAD651") (pin "1") (pinfunction "P_1") (pintype "passive"))
      (node (ref "PAD652") (pin "1") (pinfunction "P_1") (pintype "passive"))
      (node (ref "PAD653") (pin "1") (pinfunction "P_1") (pintype "passive"))
      (node (ref "PAD654") (pin "1") (pinfunction "P_1") (pintype "passive"))
      (node (ref "PAD655") (pin "1") (pinfunction "P_1") (pintype "passive"))
    )
    (net (code "104") (name "Net-(PAD656-P)") (class "Default")
      (node (ref "PAD656") (pin "1") (pinfunction "P_1") (pintype "passive"))
      (node (ref "PAD756") (pin "1") (pinfunction "P_1") (pintype "passive"))
    )
    (net (code "105") (name "Net-(PAD657-P)") (class "Default")
      (node (ref "PAD657") (pin "1") (pinfunction "P_1") (pintype "passive"))
      (node (ref "PAD755") (pin "1") (pinfunction "P_1") (pintype "passive"))
    )
    (net (code "106") (name "Net-(PAD658-P)") (class "Default")
      (node (ref "PAD658") (pin "1") (pinfunction "P_1") (pintype "passive"))
      (node (ref "PAD659") (pin "1") (pinfunction "P_1") (pintype "passive"))
      (node (ref "PAD660") (pin "1") (pinfunction "P_1") (pintype "passive"))
      (node (ref "PAD661") (pin "1") (pinfunction "P_1") (pintype "passive"))
      (node (ref "PAD662") (pin "1") (pinfunction "P_1") (pintype "passive"))
    )
    (net (code "107") (name "Net-(PAD663-P)") (class "Default")
      (node (ref "PAD663") (pin "1") (pinfunction "P_1") (pintype "passive"))
      (node (ref "PAD754") (pin "1") (pinfunction "P_1") (pintype "passive"))
    )
    (net (code "108") (name "Net-(PAD664-P)") (class "Default")
      (node (ref "PAD664") (pin "1") (pinfunction "P_1") (pintype "passive"))
      (node (ref "PAD753") (pin "1") (pinfunction "P_1") (pintype "passive"))
    )
    (net (code "109") (name "Net-(PAD665-P)") (class "Default")
      (node (ref "PAD665") (pin "1") (pinfunction "P_1") (pintype "passive"))
      (node (ref "PAD666") (pin "1") (pinfunction "P_1") (pintype "passive"))
      (node (ref "PAD667") (pin "1") (pinfunction "P_1") (pintype "passive"))
      (node (ref "PAD668") (pin "1") (pinfunction "P_1") (pintype "passive"))
      (node (ref "PAD669") (pin "1") (pinfunction "P_1") (pintype "passive"))
    )
    (net (code "110") (name "Net-(PAD670-P)") (class "Default")
      (node (ref "PAD670") (pin "1") (pinfunction "P_1") (pintype "passive"))
      (node (ref "PAD752") (pin "1") (pinfunction "P_1") (pintype "passive"))
    )
    (net (code "111") (name "Net-(PAD671-P)") (class "Default")
      (node (ref "PAD671") (pin "1") (pinfunction "P_1") (pintype "passive"))
      (node (ref "PAD751") (pin "1") (pinfunction "P_1") (pintype "passive"))
    )
    (net (code "112") (name "Net-(PAD672-P)") (class "Default")
      (node (ref "PAD672") (pin "1") (pinfunction "P_1") (pintype "passive"))
      (node (ref "PAD673") (pin "1") (pinfunction "P_1") (pintype "passive"))
      (node (ref "PAD674") (pin "1") (pinfunction "P_1") (pintype "passive"))
      (node (ref "PAD675") (pin "1") (pinfunction "P_1") (pintype "passive"))
      (node (ref "PAD676") (pin "1") (pinfunction "P_1") (pintype "passive"))
    )
    (net (code "113") (name "Net-(PAD679-P)") (class "Default")
      (node (ref "PAD679") (pin "1") (pinfunction "P_1") (pintype "passive"))
      (node (ref "PAD680") (pin "1") (pinfunction "P_1") (pintype "passive"))
      (node (ref "PAD681") (pin "1") (pinfunction "P_1") (pintype "passive"))
      (node (ref "PAD682") (pin "1") (pinfunction "P_1") (pintype "passive"))
      (node (ref "PAD683") (pin "1") (pinfunction "P_1") (pintype "passive"))
    )
    (net (code "114") (name "Net-(PAD686-P)") (class "Default")
      (node (ref "PAD686") (pin "1") (pinfunction "P_1") (pintype "passive"))
      (node (ref "PAD687") (pin "1") (pinfunction "P_1") (pintype "passive"))
      (node (ref "PAD688") (pin "1") (pinfunction "P_1") (pintype "passive"))
      (node (ref "PAD689") (pin "1") (pinfunction "P_1") (pintype "passive"))
      (node (ref "PAD690") (pin "1") (pinfunction "P_1") (pintype "passive"))
    )
    (net (code "115") (name "Net-(PAD693-P)") (class "Default")
      (node (ref "PAD693") (pin "1") (pinfunction "P_1") (pintype "passive"))
      (node (ref "PAD694") (pin "1") (pinfunction "P_1") (pintype "passive"))
      (node (ref "PAD695") (pin "1") (pinfunction "P_1") (pintype "passive"))
      (node (ref "PAD696") (pin "1") (pinfunction "P_1") (pintype "passive"))
      (node (ref "PAD697") (pin "1") (pinfunction "P_1") (pintype "passive"))
    )
    (net (code "116") (name "Net-(PAD700-P)") (class "Default")
      (node (ref "PAD700") (pin "1") (pinfunction "P_1") (pintype "passive"))
      (node (ref "PAD701") (pin "1") (pinfunction "P_1") (pintype "passive"))
      (node (ref "PAD702") (pin "1") (pinfunction "P_1") (pintype "passive"))
      (node (ref "PAD703") (pin "1") (pinfunction "P_1") (pintype "passive"))
      (node (ref "PAD704") (pin "1") (pinfunction "P_1") (pintype "passive"))
    )
    (net (code "117") (name "Net-(PAD707-P)") (class "Default")
      (node (ref "PAD707") (pin "1") (pinfunction "P_1") (pintype "passive"))
      (node (ref "PAD708") (pin "1") (pinfunction "P_1") (pintype "passive"))
      (node (ref "PAD709") (pin "1") (pinfunction "P_1") (pintype "passive"))
      (node (ref "PAD710") (pin "1") (pinfunction "P_1") (pintype "passive"))
      (node (ref "PAD711") (pin "1") (pinfunction "P_1") (pintype "passive"))
    )
    (net (code "118") (name "Net-(PAD714-P)") (class "Default")
      (node (ref "PAD714") (pin "1") (pinfunction "P_1") (pintype "passive"))
      (node (ref "PAD715") (pin "1") (pinfunction "P_1") (pintype "passive"))
      (node (ref "PAD716") (pin "1") (pinfunction "P_1") (pintype "passive"))
      (node (ref "PAD717") (pin "1") (pinfunction "P_1") (pintype "passive"))
      (node (ref "PAD718") (pin "1") (pinfunction "P_1") (pintype "passive"))
    )
    (net (code "119") (name "Net-(PAD721-P)") (class "Default")
      (node (ref "PAD721") (pin "1") (pinfunction "P_1") (pintype "passive"))
      (node (ref "PAD722") (pin "1") (pinfunction "P_1") (pintype "passive"))
      (node (ref "PAD723") (pin "1") (pinfunction "P_1") (pintype "passive"))
      (node (ref "PAD724") (pin "1") (pinfunction "P_1") (pintype "passive"))
      (node (ref "PAD725") (pin "1") (pinfunction "P_1") (pintype "passive"))
    )
    (net (code "120") (name "Net-(PAD728-P)") (class "Default")
      (node (ref "PAD728") (pin "1") (pinfunction "P_1") (pintype "passive"))
      (node (ref "PAD729") (pin "1") (pinfunction "P_1") (pintype "passive"))
      (node (ref "PAD730") (pin "1") (pinfunction "P_1") (pintype "passive"))
      (node (ref "PAD731") (pin "1") (pinfunction "P_1") (pintype "passive"))
      (node (ref "PAD732") (pin "1") (pinfunction "P_1") (pintype "passive"))
    )
    (net (code "121") (name "Net-(PAD742-P)") (class "Default")
      (node (ref "PAD742") (pin "1") (pinfunction "P_1") (pintype "passive"))
      (node (ref "PAD743") (pin "1") (pinfunction "P_1") (pintype "passive"))
      (node (ref "PAD744") (pin "1") (pinfunction "P_1") (pintype "passive"))
      (node (ref "PAD745") (pin "1") (pinfunction "P_1") (pintype "passive"))
      (node (ref "X1") (pin "6") (pinfunction "GPIO12_6") (pintype "bidirectional"))
    )
    (net (code "122") (name "Net-(PAD746-P)") (class "Default")
      (node (ref "PAD746") (pin "1") (pinfunction "P_1") (pintype "passive"))
      (node (ref "PAD747") (pin "1") (pinfunction "P_1") (pintype "passive"))
      (node (ref "PAD748") (pin "1") (pinfunction "P_1") (pintype "passive"))
      (node (ref "PAD749") (pin "1") (pinfunction "P_1") (pintype "passive"))
      (node (ref "X1") (pin "7") (pinfunction "GPIO13_7") (pintype "bidirectional"))
    )
    (net (code "123") (name "Net-(PAD758-P)") (class "Default")
      (node (ref "PAD758") (pin "1") (pinfunction "P_1") (pintype "passive"))
      (node (ref "PAD759") (pin "1") (pinfunction "P_1") (pintype "passive"))
      (node (ref "PAD760") (pin "1") (pinfunction "P_1") (pintype "passive"))
      (node (ref "PAD761") (pin "1") (pinfunction "P_1") (pintype "passive"))
    )
    (net (code "124") (name "Net-(PAD762-P)") (class "Default")
      (node (ref "PAD762") (pin "1") (pinfunction "P_1") (pintype "passive"))
      (node (ref "PAD763") (pin "1") (pinfunction "P_1") (pintype "passive"))
      (node (ref "PAD764") (pin "1") (pinfunction "P_1") (pintype "passive"))
      (node (ref "PAD765") (pin "1") (pinfunction "P_1") (pintype "passive"))
    )
    (net (code "125") (name "Net-(PAD766-P)") (class "Default")
      (node (ref "PAD766") (pin "1") (pinfunction "P_1") (pintype "passive"))
      (node (ref "PAD767") (pin "1") (pinfunction "P_1") (pintype "passive"))
      (node (ref "PAD768") (pin "1") (pinfunction "P_1") (pintype "passive"))
      (node (ref "PAD769") (pin "1") (pinfunction "P_1") (pintype "passive"))
    )
    (net (code "126") (name "Net-(PAD770-P)") (class "Default")
      (node (ref "PAD770") (pin "1") (pinfunction "P_1") (pintype "passive"))
      (node (ref "PAD771") (pin "1") (pinfunction "P_1") (pintype "passive"))
      (node (ref "PAD772") (pin "1") (pinfunction "P_1") (pintype "passive"))
      (node (ref "PAD773") (pin "1") (pinfunction "P_1") (pintype "passive"))
      (node (ref "X1") (pin "1") (pinfunction "RESET_1") (pintype "input"))
    )
    (net (code "127") (name "Net-(PAD774-P)") (class "Default")
      (node (ref "PAD774") (pin "1") (pinfunction "P_1") (pintype "passive"))
      (node (ref "PAD775") (pin "1") (pinfunction "P_1") (pintype "passive"))
      (node (ref "PAD776") (pin "1") (pinfunction "P_1") (pintype "passive"))
      (node (ref "PAD777") (pin "1") (pinfunction "P_1") (pintype "passive"))
    )
    (net (code "128") (name "Net-(PAD778-P)") (class "Default")
      (node (ref "PAD778") (pin "1") (pinfunction "P_1") (pintype "passive"))
      (node (ref "PAD779") (pin "1") (pinfunction "P_1") (pintype "passive"))
      (node (ref "PAD780") (pin "1") (pinfunction "P_1") (pintype "passive"))
      (node (ref "PAD781") (pin "1") (pinfunction "P_1") (pintype "passive"))
    )
    (net (code "129") (name "Net-(RJ-3-P)") (class "Default")
      (node (ref "RJ-3") (pin "1") (pinfunction "P_1") (pintype "passive"))
      (node (ref "X3") (pin "2") (pinfunction "2_2") (pintype "passive"))
    )
    (net (code "130") (name "RX") (class "Default")
      (node (ref "PAD267") (pin "1") (pinfunction "P_1") (pintype "passive"))
      (node (ref "PAD268") (pin "1") (pinfunction "P_1") (pintype "passive"))
      (node (ref "PAD396") (pin "1") (pinfunction "P_1") (pintype "passive"))
      (node (ref "PAD397") (pin "1") (pinfunction "P_1") (pintype "passive"))
      (node (ref "RX") (pin "1") (pinfunction "P_1") (pintype "passive"))
      (node (ref "X1") (pin "15") (pinfunction "RXD_15") (pintype "input"))
    )
    (net (code "131") (name "TX") (class "Default")
      (node (ref "PAD256") (pin "1") (pinfunction "P_1") (pintype "passive"))
      (node (ref "PAD257") (pin "1") (pinfunction "P_1") (pintype "passive"))
      (node (ref "PAD258") (pin "1") (pinfunction "P_1") (pintype "passive"))
      (node (ref "PAD259") (pin "1") (pinfunction "P_1") (pintype "passive"))
      (node (ref "TX") (pin "1") (pinfunction "P_1") (pintype "passive"))
      (node (ref "X1") (pin "16") (pinfunction "TXD_16") (pintype "output"))
    )
    (net (code "132") (name "VCC") (class "Default")
      (node (ref "5V") (pin "1") (pinfunction "P_1") (pintype "passive"))
      (node (ref "DC") (pin "1") (pinfunction "VIN_1") (pintype "passive"))
      (node (ref "J1") (pin "1") (pinfunction "1_1") (pintype "passive"))
      (node (ref "MIC5502") (pin "1") (pinfunction "IN_1") (pintype "input"))
      (node (ref "MIC5502") (pin "3") (pinfunction "EN_3") (pintype "input"))
      (node (ref "X2") (pin "VBUS") (pinfunction "VBUS_VBUS") (pintype "power_in"))
    )
    (net (code "133") (name "VDD") (class "Default")
      (node (ref "DC") (pin "3") (pinfunction "VOUT_3") (pintype "passive"))
      (node (ref "MIC5502") (pin "5") (pinfunction "OUT_5") (pintype "passive"))
      (node (ref "PAD10") (pin "1") (pinfunction "P_1") (pintype "passive"))
      (node (ref "PAD109") (pin "1") (pinfunction "P_1") (pintype "passive"))
      (node (ref "PAD11") (pin "1") (pinfunction "P_1") (pintype "passive"))
      (node (ref "PAD13") (pin "1") (pinfunction "P_1") (pintype "passive"))
      (node (ref "PAD14") (pin "1") (pinfunction "P_1") (pintype "passive"))
      (node (ref "PAD16") (pin "1") (pinfunction "P_1") (pintype "passive"))
      (node (ref "PAD18") (pin "1") (pinfunction "P_1") (pintype "passive"))
      (node (ref "PAD19") (pin "1") (pinfunction "P_1") (pintype "passive"))
      (node (ref "PAD20") (pin "1") (pinfunction "P_1") (pintype "passive"))
      (node (ref "PAD21") (pin "1") (pinfunction "P_1") (pintype "passive"))
      (node (ref "PAD294") (pin "1") (pinfunction "P_1") (pintype "passive"))
      (node (ref "PAD295") (pin "1") (pinfunction "P_1") (pintype "passive"))
      (node (ref "PAD303") (pin "1") (pinfunction "P_1") (pintype "passive"))
      (node (ref "PAD304") (pin "1") (pinfunction "P_1") (pintype "passive"))
      (node (ref "PAD312") (pin "1") (pinfunction "P_1") (pintype "passive"))
      (node (ref "PAD313") (pin "1") (pinfunction "P_1") (pintype "passive"))
      (node (ref "PAD321") (pin "1") (pinfunction "P_1") (pintype "passive"))
      (node (ref "PAD322") (pin "1") (pinfunction "P_1") (pintype "passive"))
      (node (ref "PAD323") (pin "1") (pinfunction "P_1") (pintype "passive"))
      (node (ref "PAD324") (pin "1") (pinfunction "P_1") (pintype "passive"))
      (node (ref "PAD325") (pin "1") (pinfunction "P_1") (pintype "passive"))
      (node (ref "PAD442") (pin "1") (pinfunction "P_1") (pintype "passive"))
      (node (ref "PAD443") (pin "1") (pinfunction "P_1") (pintype "passive"))
      (node (ref "PAD444") (pin "1") (pinfunction "P_1") (pintype "passive"))
      (node (ref "PAD445") (pin "1") (pinfunction "P_1") (pintype "passive"))
      (node (ref "PAD446") (pin "1") (pinfunction "P_1") (pintype "passive"))
      (node (ref "PAD448") (pin "1") (pinfunction "P_1") (pintype "passive"))
      (node (ref "PAD449") (pin "1") (pinfunction "P_1") (pintype "passive"))
      (node (ref "PAD450") (pin "1") (pinfunction "P_1") (pintype "passive"))
      (node (ref "PAD451") (pin "1") (pinfunction "P_1") (pintype "passive"))
      (node (ref "PAD452") (pin "1") (pinfunction "P_1") (pintype "passive"))
      (node (ref "PAD453") (pin "1") (pinfunction "P_1") (pintype "passive"))
      (node (ref "PAD454") (pin "1") (pinfunction "P_1") (pintype "passive"))
      (node (ref "PAD455") (pin "1") (pinfunction "P_1") (pintype "passive"))
      (node (ref "PAD456") (pin "1") (pinfunction "P_1") (pintype "passive"))
      (node (ref "PAD459") (pin "1") (pinfunction "P_1") (pintype "passive"))
      (node (ref "PAD460") (pin "1") (pinfunction "P_1") (pintype "passive"))
      (node (ref "PAD461") (pin "1") (pinfunction "P_1") (pintype "passive"))
      (node (ref "PAD462") (pin "1") (pinfunction "P_1") (pintype "passive"))
      (node (ref "PAD480") (pin "1") (pinfunction "P_1") (pintype "passive"))
      (node (ref "PAD481") (pin "1") (pinfunction "P_1") (pintype "passive"))
      (node (ref "PAD482") (pin "1") (pinfunction "P_1") (pintype "passive"))
      (node (ref "PAD483") (pin "1") (pinfunction "P_1") (pintype "passive"))
      (node (ref "PAD484") (pin "1") (pinfunction "P_1") (pintype "passive"))
      (node (ref "PAD485") (pin "1") (pinfunction "P_1") (pintype "passive"))
      (node (ref "PAD486") (pin "1") (pinfunction "P_1") (pintype "passive"))
      (node (ref "PAD487") (pin "1") (pinfunction "P_1") (pintype "passive"))
      (node (ref "PAD488") (pin "1") (pinfunction "P_1") (pintype "passive"))
      (node (ref "PAD489") (pin "1") (pinfunction "P_1") (pintype "passive"))
      (node (ref "PAD490") (pin "1") (pinfunction "P_1") (pintype "passive"))
      (node (ref "PAD496") (pin "1") (pinfunction "P_1") (pintype "passive"))
      (node (ref "PAD497") (pin "1") (pinfunction "P_1") (pintype "passive"))
      (node (ref "PAD5") (pin "1") (pinfunction "P_1") (pintype "passive"))
      (node (ref "PAD503") (pin "1") (pinfunction "P_1") (pintype "passive"))
      (node (ref "PAD504") (pin "1") (pinfunction "P_1") (pintype "passive"))
      (node (ref "PAD510") (pin "1") (pinfunction "P_1") (pintype "passive"))
      (node (ref "PAD511") (pin "1") (pinfunction "P_1") (pintype "passive"))
      (node (ref "PAD517") (pin "1") (pinfunction "P_1") (pintype "passive"))
      (node (ref "PAD539") (pin "1") (pinfunction "P_1") (pintype "passive"))
      (node (ref "PAD6") (pin "1") (pinfunction "P_1") (pintype "passive"))
      (node (ref "PAD617") (pin "1") (pinfunction "P_1") (pintype "passive"))
      (node (ref "PAD618") (pin "1") (pinfunction "P_1") (pintype "passive"))
      (node (ref "PAD649") (pin "1") (pinfunction "P_1") (pintype "passive"))
      (node (ref "PAD650") (pin "1") (pinfunction "P_1") (pintype "passive"))
      (node (ref "PAD7") (pin "1") (pinfunction "P_1") (pintype "passive"))
      (node (ref "PAD784") (pin "1") (pinfunction "P_1") (pintype "passive"))
      (node (ref "PAD785") (pin "1") (pinfunction "P_1") (pintype "passive"))
      (node (ref "PAD786") (pin "1") (pinfunction "P_1") (pintype "passive"))
      (node (ref "PAD787") (pin "1") (pinfunction "P_1") (pintype "passive"))
      (node (ref "PAD792") (pin "1") (pinfunction "P_1") (pintype "passive"))
      (node (ref "PAD793") (pin "1") (pinfunction "P_1") (pintype "passive"))
      (node (ref "PAD794") (pin "1") (pinfunction "P_1") (pintype "passive"))
      (node (ref "PAD8") (pin "1") (pinfunction "P_1") (pintype "passive"))
      (node (ref "PAD9") (pin "1") (pinfunction "P_1") (pintype "passive"))
      (node (ref "X1") (pin "8") (pinfunction "VCC_8") (pintype "power_in"))
    )
    (net (code "134") (name "unconnected-(MIC5502-BP-Pad4)") (class "Default")
      (node (ref "MIC5502") (pin "4") (pinfunction "BP_4") (pintype "input"))
    )
    (net (code "135") (name "unconnected-(X1-CLK-Pad20)") (class "Default")
      (node (ref "X1") (pin "20") (pinfunction "CLK_20") (pintype "bidirectional"))
    )
    (net (code "136") (name "unconnected-(X1-CS-Pad17)") (class "Default")
      (node (ref "X1") (pin "17") (pinfunction "CS_17") (pintype "bidirectional"))
    )
    (net (code "137") (name "unconnected-(X1-DI-Pad21)") (class "Default")
      (node (ref "X1") (pin "21") (pinfunction "DI_21") (pintype "bidirectional"))
    )
    (net (code "138") (name "unconnected-(X1-DO-Pad18)") (class "Default")
      (node (ref "X1") (pin "18") (pinfunction "DO_18") (pintype "bidirectional"))
    )
    (net (code "139") (name "unconnected-(X1-GPIO9-Pad22)") (class "Default")
      (node (ref "X1") (pin "22") (pinfunction "GPIO9_22") (pintype "bidirectional"))
    )
    (net (code "140") (name "unconnected-(X1-GPIO10-Pad19)") (class "Default")
      (node (ref "X1") (pin "19") (pinfunction "GPIO10_19") (pintype "bidirectional"))
    )
    (net (code "141") (name "unconnected-(X2-PadD+)") (class "Default")
      (node (ref "X2") (pin "D+") (pinfunction "D+_D+") (pintype "bidirectional"))
    )
    (net (code "142") (name "unconnected-(X2-PadD-)") (class "Default")
      (node (ref "X2") (pin "D-") (pinfunction "D-_D-") (pintype "bidirectional"))
    )
    (net (code "143") (name "unconnected-(X2-PadID)") (class "Default")
      (node (ref "X2") (pin "ID") (pinfunction "ID_ID") (pintype "bidirectional"))
    )
  )
)
